# LargePrototype-V3.net
KiCad netlist of a schematic drawn in EAGLE
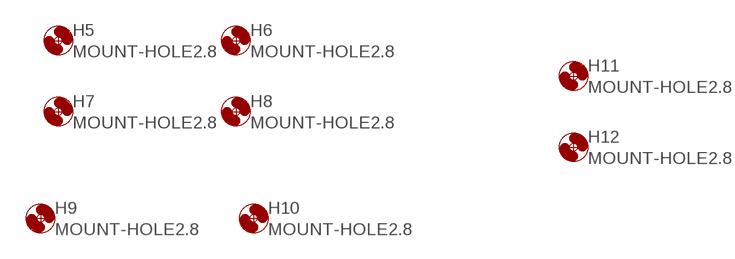
[diagram p0: schematic, sheet 1, part 1 of 3]
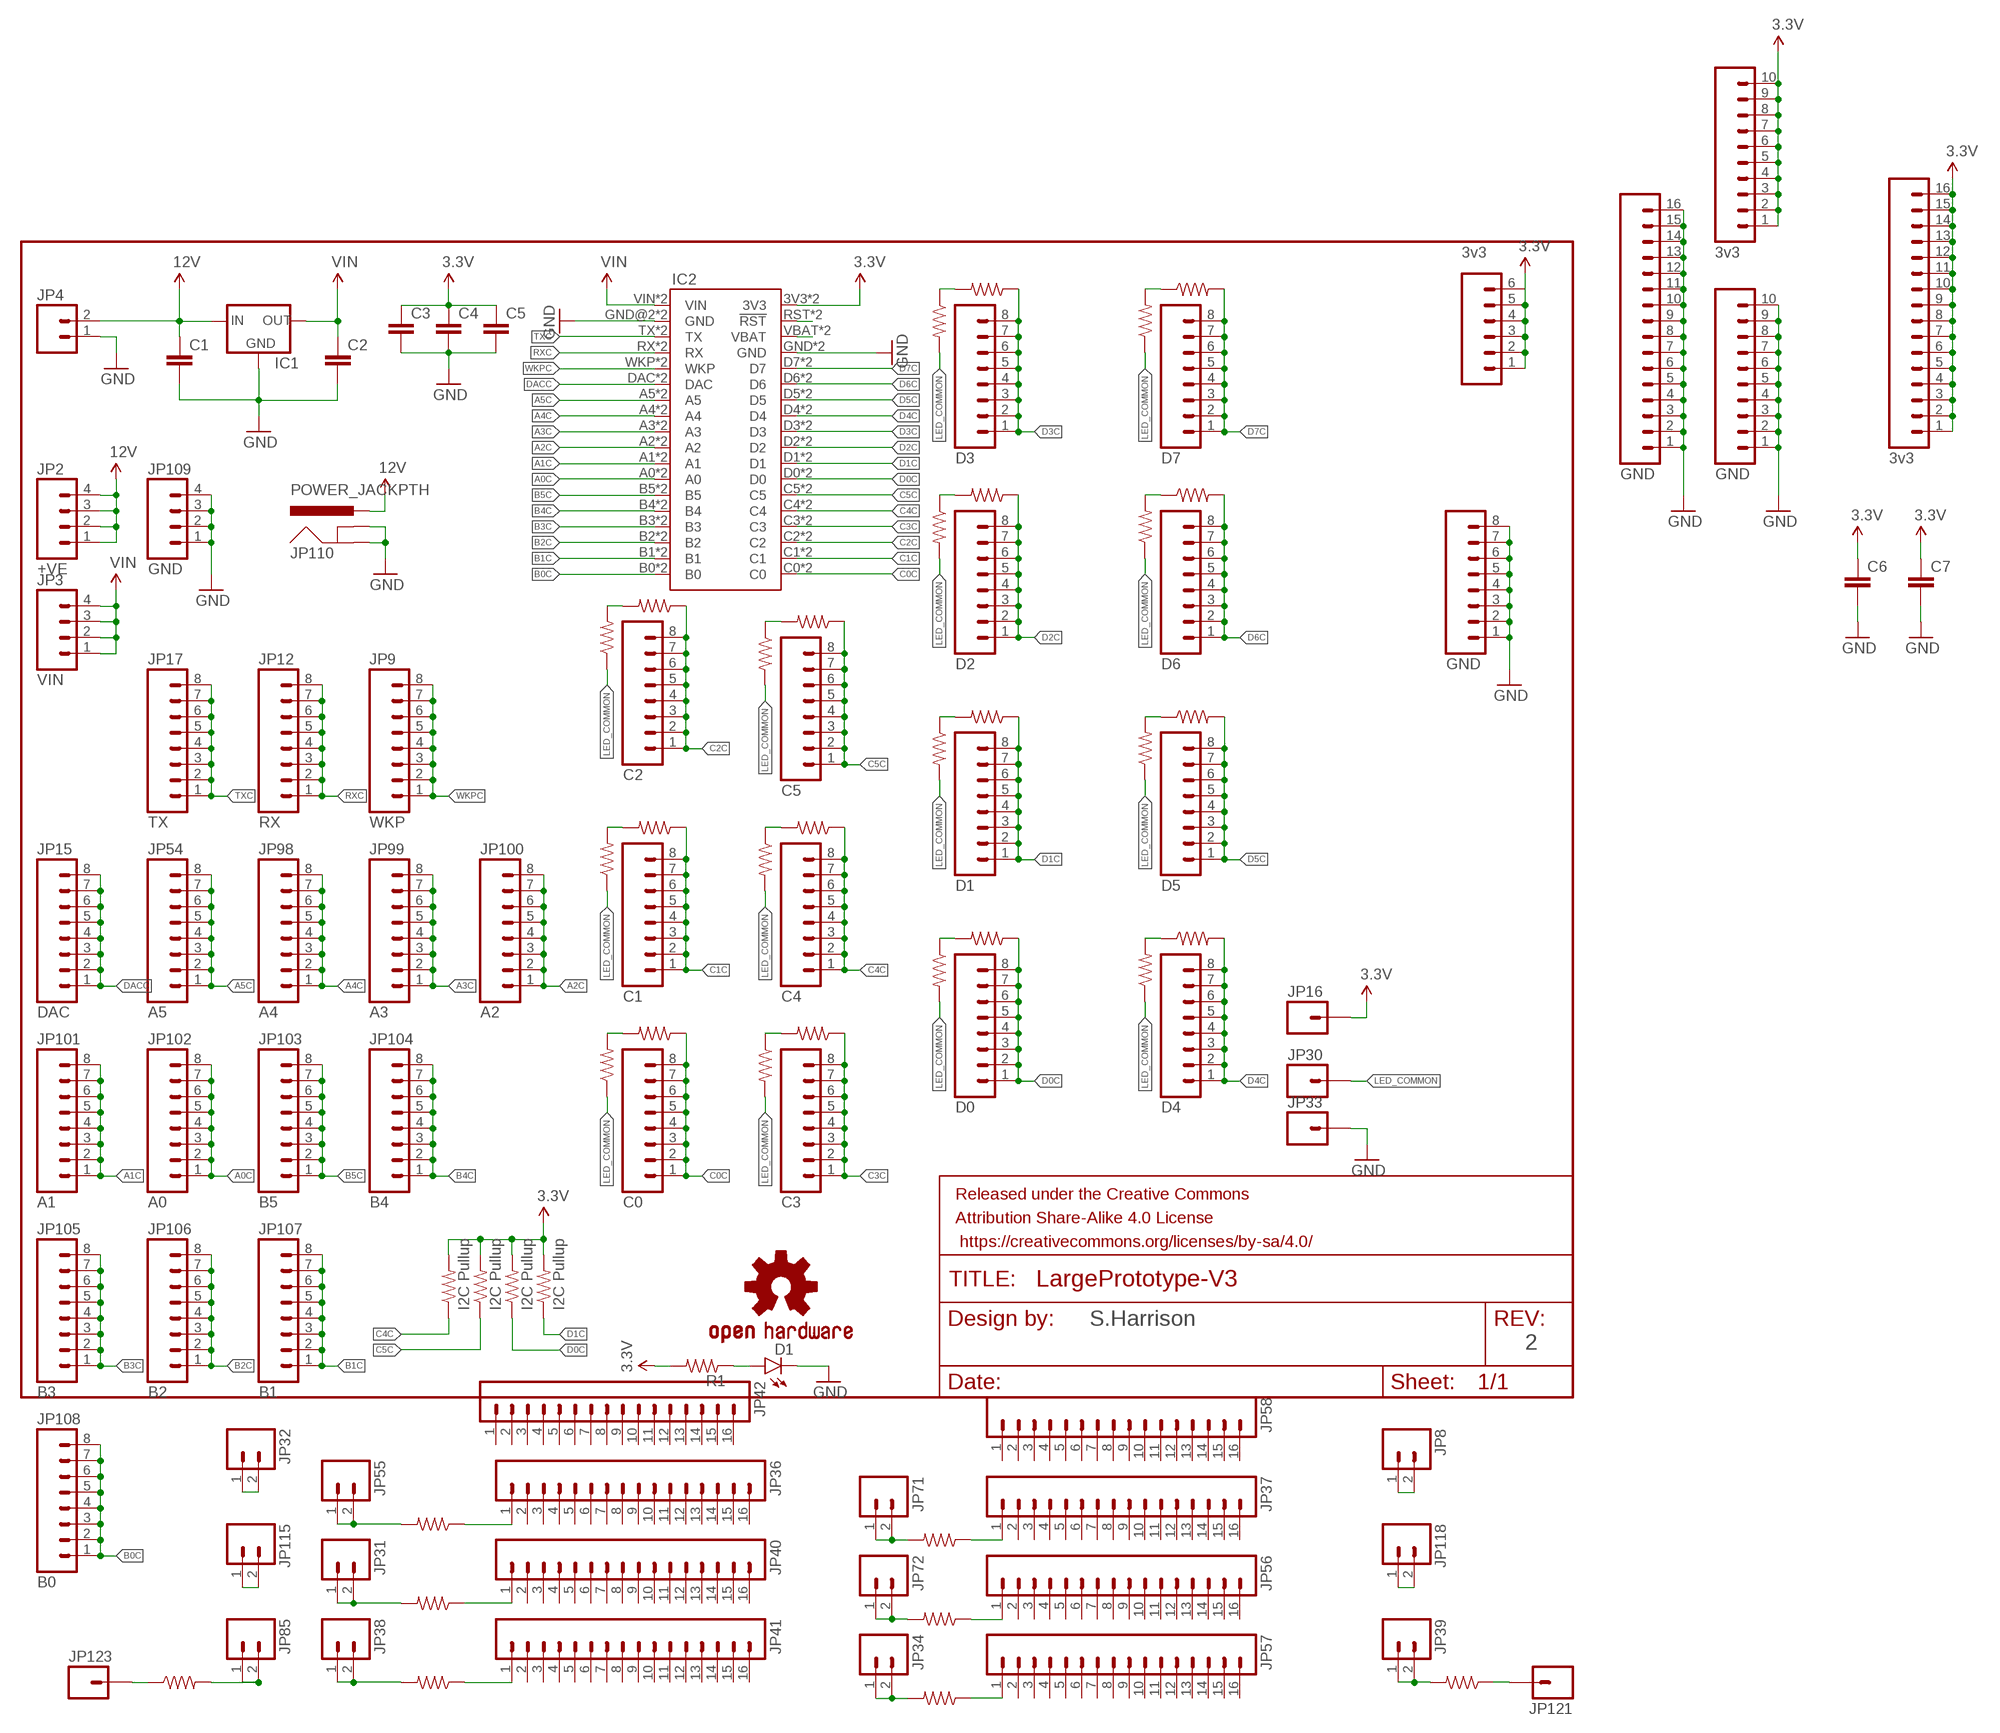
[diagram p1: schematic, sheet 1, part 2 of 3]
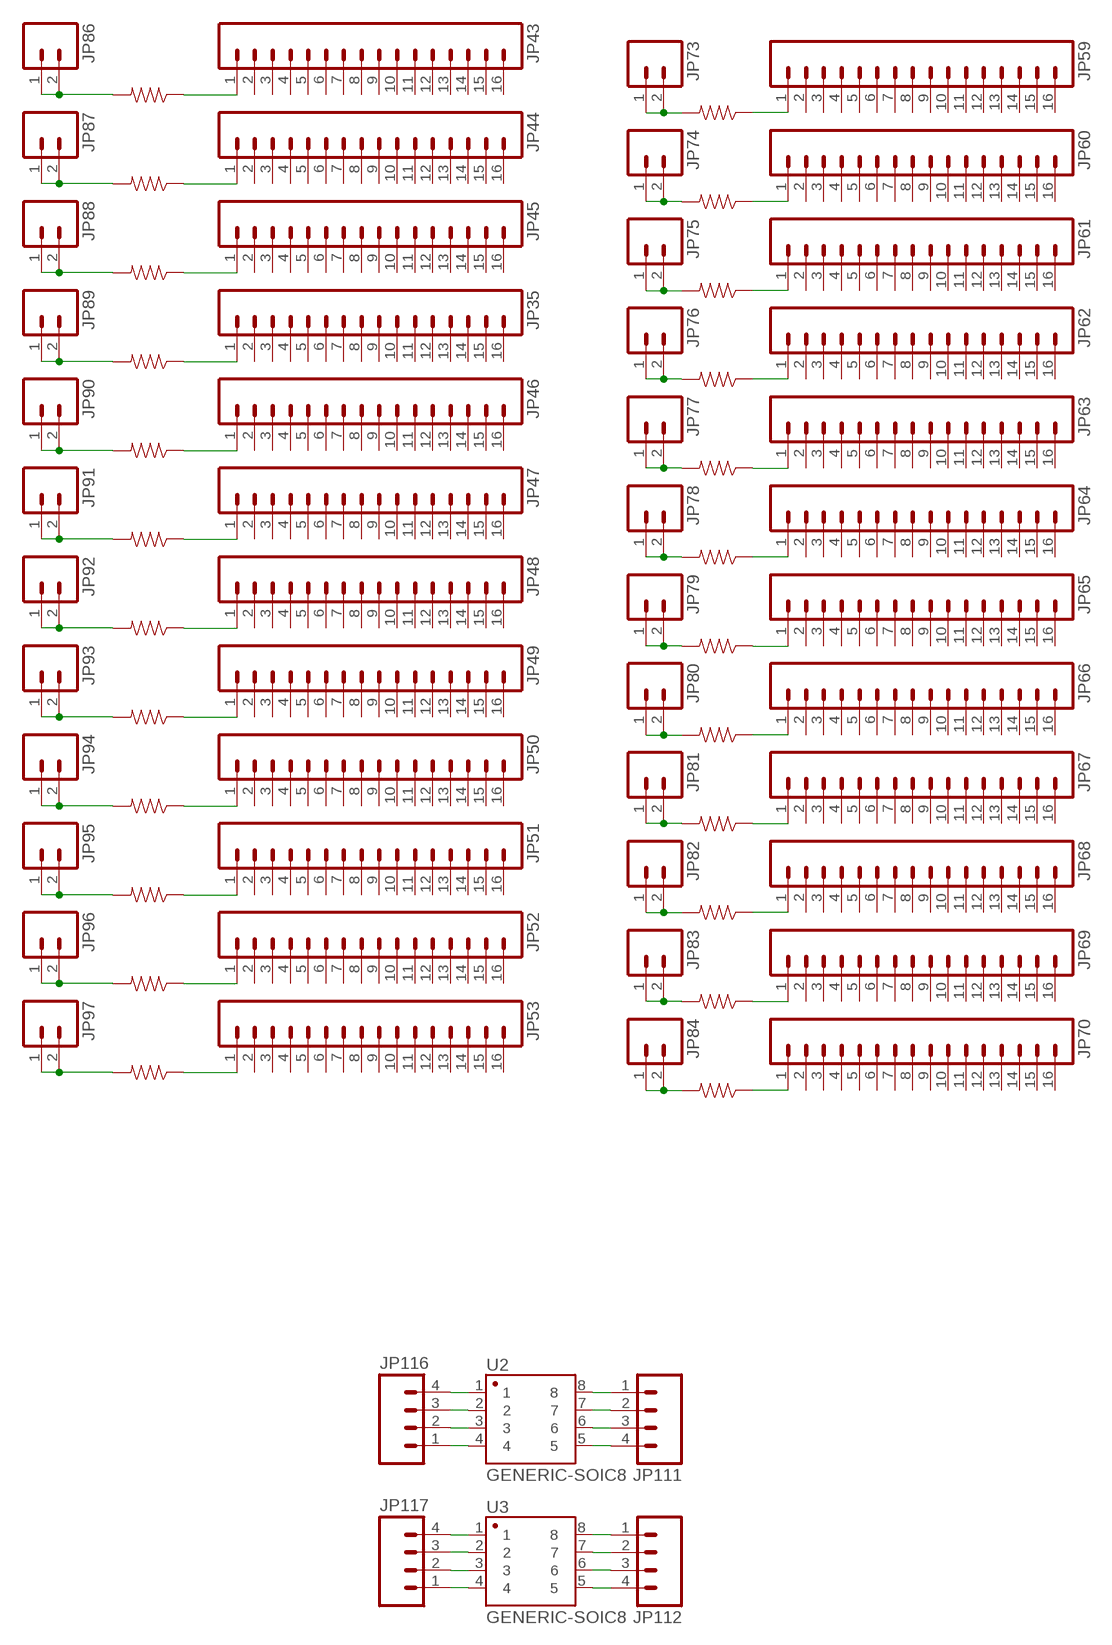
[diagram p2: schematic, sheet 1, part 3 of 3]

(export (version "E")
  (design (tool "Eeschema 10.0.6"))
  (components
    (comp (ref "C1")
      (value "1UF-25V-10%(0805)\"")
      (footprint "eagle-import:0805-CAP")
      (libsource (lib "eagle-import") (part "1UF-25V-10%(0805){dblquote}"))
    )
    (comp (ref "C2")
      (value "1UF-25V-10%(0805)\"")
      (footprint "eagle-import:0805-CAP")
      (libsource (lib "eagle-import") (part "1UF-25V-10%(0805){dblquote}"))
    )
    (comp (ref "C3")
      (value "1UF-25V-10%(0805)\"")
      (footprint "eagle-import:0805-CAP")
      (libsource (lib "eagle-import") (part "1UF-25V-10%(0805){dblquote}"))
    )
    (comp (ref "C4")
      (value "1UF-25V-10%(0805)\"")
      (footprint "eagle-import:0805-CAP")
      (libsource (lib "eagle-import") (part "1UF-25V-10%(0805){dblquote}"))
    )
    (comp (ref "C5")
      (value "1UF-25V-10%(0805)\"")
      (footprint "eagle-import:0805-CAP")
      (libsource (lib "eagle-import") (part "1UF-25V-10%(0805){dblquote}"))
    )
    (comp (ref "C6")
      (value "1UF-25V-10%(0805)\"")
      (footprint "eagle-import:0805-CAP")
      (libsource (lib "eagle-import") (part "1UF-25V-10%(0805){dblquote}"))
    )
    (comp (ref "C7")
      (value "1UF-25V-10%(0805)\"")
      (footprint "eagle-import:0805-CAP")
      (libsource (lib "eagle-import") (part "1UF-25V-10%(0805){dblquote}"))
    )
    (comp (ref "D1")
      (value "LED1206-BOTTOM")
      (footprint "eagle-import:LED-1206-BOTTOM")
      (libsource (lib "eagle-import") (part "LED1206-BOTTOM"))
    )
    (comp (ref "FRAME1")
      (value "FRAME-LETTER")
      (footprint "eagle-import:CREATIVE_COMMONS")
      (libsource (lib "eagle-import") (part "FRAME-LETTER"))
    )
    (comp (ref "H5")
      (value "MOUNT-HOLE2.8")
      (footprint "eagle-import:2,8")
      (libsource (lib "eagle-import") (part "MOUNT-HOLE2.8"))
    )
    (comp (ref "H6")
      (value "MOUNT-HOLE2.8")
      (footprint "eagle-import:2,8")
      (libsource (lib "eagle-import") (part "MOUNT-HOLE2.8"))
    )
    (comp (ref "H7")
      (value "MOUNT-HOLE2.8")
      (footprint "eagle-import:2,8")
      (libsource (lib "eagle-import") (part "MOUNT-HOLE2.8"))
    )
    (comp (ref "H8")
      (value "MOUNT-HOLE2.8")
      (footprint "eagle-import:2,8")
      (libsource (lib "eagle-import") (part "MOUNT-HOLE2.8"))
    )
    (comp (ref "H9")
      (value "MOUNT-HOLE2.8")
      (footprint "eagle-import:2,8")
      (libsource (lib "eagle-import") (part "MOUNT-HOLE2.8"))
    )
    (comp (ref "H10")
      (value "MOUNT-HOLE2.8")
      (footprint "eagle-import:2,8")
      (libsource (lib "eagle-import") (part "MOUNT-HOLE2.8"))
    )
    (comp (ref "H11")
      (value "MOUNT-HOLE2.8")
      (footprint "eagle-import:2,8")
      (libsource (lib "eagle-import") (part "MOUNT-HOLE2.8"))
    )
    (comp (ref "H12")
      (value "MOUNT-HOLE2.8")
      (footprint "eagle-import:2,8")
      (libsource (lib "eagle-import") (part "MOUNT-HOLE2.8"))
    )
    (comp (ref "IC1")
      (value "78XXS")
      (footprint "eagle-import:78XXS")
      (libsource (lib "eagle-import") (part "78XXS"))
    )
    (comp (ref "IC2")
      (value "ELECTRONDUALNAMED")
      (footprint "eagle-import:ELECTRON_SIMPLE_SILK_NAMES_DUAL")
      (libsource (lib "eagle-import") (part "ELECTRONDUALNAMED"))
    )
    (comp (ref "JP1")
      (value "D7")
      (footprint "eagle-import:1X08_ROUND")
      (libsource (lib "eagle-import") (part "M08"))
    )
    (comp (ref "JP2")
      (value "+VE")
      (footprint "eagle-import:1X04")
      (libsource (lib "eagle-import") (part "M04PTH"))
    )
    (comp (ref "JP3")
      (value "VIN")
      (footprint "eagle-import:1X04")
      (libsource (lib "eagle-import") (part "M04PTH"))
    )
    (comp (ref "JP4")
      (value "M025MM")
      (footprint "eagle-import:SCREWTERMINAL-5MM-2")
      (libsource (lib "eagle-import") (part "M025MM"))
    )
    (comp (ref "JP5")
      (value "3v3")
      (footprint "eagle-import:1X10")
      (libsource (lib "eagle-import") (part "M10SILK_FEMALE_PTH"))
    )
    (comp (ref "JP6")
      (value "3v3")
      (footprint "eagle-import:1X06")
      (libsource (lib "eagle-import") (part "M06SILK_FEMALE_PTH"))
    )
    (comp (ref "JP7")
      (value "D6")
      (footprint "eagle-import:1X08_ROUND")
      (libsource (lib "eagle-import") (part "M08"))
    )
    (comp (ref "JP8")
      (value "M02PTH")
      (footprint "eagle-import:1X02")
      (libsource (lib "eagle-import") (part "M02PTH"))
    )
    (comp (ref "JP9")
      (value "WKP")
      (footprint "eagle-import:1X08_ROUND")
      (libsource (lib "eagle-import") (part "M08"))
    )
    (comp (ref "JP10")
      (value "D5")
      (footprint "eagle-import:1X08_ROUND")
      (libsource (lib "eagle-import") (part "M08"))
    )
    (comp (ref "JP11")
      (value "GND")
      (footprint "eagle-import:1X10")
      (libsource (lib "eagle-import") (part "M10SILK_FEMALE_PTH"))
    )
    (comp (ref "JP12")
      (value "RX")
      (footprint "eagle-import:1X08_ROUND")
      (libsource (lib "eagle-import") (part "M08"))
    )
    (comp (ref "JP13")
      (value "3v3")
      (footprint "eagle-import:1X16")
      (libsource (lib "eagle-import") (part "M16PTH"))
    )
    (comp (ref "JP14")
      (value "GND")
      (footprint "eagle-import:1X16")
      (libsource (lib "eagle-import") (part "M16PTH"))
    )
    (comp (ref "JP15")
      (value "DAC")
      (footprint "eagle-import:1X08_ROUND")
      (libsource (lib "eagle-import") (part "M08"))
    )
    (comp (ref "JP16")
      (value "M01PTH")
      (footprint "eagle-import:1X01")
      (libsource (lib "eagle-import") (part "M01PTH"))
    )
    (comp (ref "JP17")
      (value "TX")
      (footprint "eagle-import:1X08_ROUND")
      (libsource (lib "eagle-import") (part "M08"))
    )
    (comp (ref "JP18")
      (value "D4")
      (footprint "eagle-import:1X08_ROUND")
      (libsource (lib "eagle-import") (part "M08"))
    )
    (comp (ref "JP19")
      (value "D3")
      (footprint "eagle-import:1X08_ROUND")
      (libsource (lib "eagle-import") (part "M08"))
    )
    (comp (ref "JP20")
      (value "D2")
      (footprint "eagle-import:1X08_ROUND")
      (libsource (lib "eagle-import") (part "M08"))
    )
    (comp (ref "JP21")
      (value "D1")
      (footprint "eagle-import:1X08_ROUND")
      (libsource (lib "eagle-import") (part "M08"))
    )
    (comp (ref "JP22")
      (value "D0")
      (footprint "eagle-import:1X08_ROUND")
      (libsource (lib "eagle-import") (part "M08"))
    )
    (comp (ref "JP23")
      (value "GND")
      (footprint "eagle-import:1X08_ROUND")
      (libsource (lib "eagle-import") (part "M08"))
    )
    (comp (ref "JP24")
      (value "C5")
      (footprint "eagle-import:1X08_ROUND")
      (libsource (lib "eagle-import") (part "M08"))
    )
    (comp (ref "JP25")
      (value "C4")
      (footprint "eagle-import:1X08_ROUND")
      (libsource (lib "eagle-import") (part "M08"))
    )
    (comp (ref "JP26")
      (value "C3")
      (footprint "eagle-import:1X08_ROUND")
      (libsource (lib "eagle-import") (part "M08"))
    )
    (comp (ref "JP27")
      (value "C2")
      (footprint "eagle-import:1X08_ROUND")
      (libsource (lib "eagle-import") (part "M08"))
    )
    (comp (ref "JP28")
      (value "C1")
      (footprint "eagle-import:1X08_ROUND")
      (libsource (lib "eagle-import") (part "M08"))
    )
    (comp (ref "JP29")
      (value "C0")
      (footprint "eagle-import:1X08_ROUND")
      (libsource (lib "eagle-import") (part "M08"))
    )
    (comp (ref "JP30")
      (value "M01PTH")
      (footprint "eagle-import:1X01")
      (libsource (lib "eagle-import") (part "M01PTH"))
    )
    (comp (ref "JP31")
      (value "M02PTH")
      (footprint "eagle-import:1X02")
      (libsource (lib "eagle-import") (part "M02PTH"))
    )
    (comp (ref "JP32")
      (value "M02PTH")
      (footprint "eagle-import:1X02")
      (libsource (lib "eagle-import") (part "M02PTH"))
    )
    (comp (ref "JP33")
      (value "M01PTH")
      (footprint "eagle-import:1X01")
      (libsource (lib "eagle-import") (part "M01PTH"))
    )
    (comp (ref "JP34")
      (value "M02PTH")
      (footprint "eagle-import:1X02")
      (libsource (lib "eagle-import") (part "M02PTH"))
    )
    (comp (ref "JP35")
      (value "M161X16_NO_SILK")
      (footprint "eagle-import:1X16_NO_SILK")
      (libsource (lib "eagle-import") (part "M161X16_NO_SILK"))
    )
    (comp (ref "JP36")
      (value "M161X16_NO_SILK")
      (footprint "eagle-import:1X16_NO_SILK")
      (libsource (lib "eagle-import") (part "M161X16_NO_SILK"))
    )
    (comp (ref "JP37")
      (value "M161X16_NO_SILK")
      (footprint "eagle-import:1X16_NO_SILK")
      (libsource (lib "eagle-import") (part "M161X16_NO_SILK"))
    )
    (comp (ref "JP38")
      (value "M02PTH")
      (footprint "eagle-import:1X02")
      (libsource (lib "eagle-import") (part "M02PTH"))
    )
    (comp (ref "JP39")
      (value "M02PTH")
      (footprint "eagle-import:1X02")
      (libsource (lib "eagle-import") (part "M02PTH"))
    )
    (comp (ref "JP40")
      (value "M161X16_NO_SILK")
      (footprint "eagle-import:1X16_NO_SILK")
      (libsource (lib "eagle-import") (part "M161X16_NO_SILK"))
    )
    (comp (ref "JP41")
      (value "M161X16_NO_SILK")
      (footprint "eagle-import:1X16_NO_SILK")
      (libsource (lib "eagle-import") (part "M161X16_NO_SILK"))
    )
    (comp (ref "JP42")
      (value "M161X16_NO_SILK")
      (footprint "eagle-import:1X16_NO_SILK")
      (libsource (lib "eagle-import") (part "M161X16_NO_SILK"))
    )
    (comp (ref "JP43")
      (value "M161X16_NO_SILK")
      (footprint "eagle-import:1X16_NO_SILK")
      (libsource (lib "eagle-import") (part "M161X16_NO_SILK"))
    )
    (comp (ref "JP44")
      (value "M161X16_NO_SILK")
      (footprint "eagle-import:1X16_NO_SILK")
      (libsource (lib "eagle-import") (part "M161X16_NO_SILK"))
    )
    (comp (ref "JP45")
      (value "M161X16_NO_SILK")
      (footprint "eagle-import:1X16_NO_SILK")
      (libsource (lib "eagle-import") (part "M161X16_NO_SILK"))
    )
    (comp (ref "JP46")
      (value "M161X16_NO_SILK")
      (footprint "eagle-import:1X16_NO_SILK")
      (libsource (lib "eagle-import") (part "M161X16_NO_SILK"))
    )
    (comp (ref "JP47")
      (value "M161X16_NO_SILK")
      (footprint "eagle-import:1X16_NO_SILK")
      (libsource (lib "eagle-import") (part "M161X16_NO_SILK"))
    )
    (comp (ref "JP48")
      (value "M161X16_NO_SILK")
      (footprint "eagle-import:1X16_NO_SILK")
      (libsource (lib "eagle-import") (part "M161X16_NO_SILK"))
    )
    (comp (ref "JP49")
      (value "M161X16_NO_SILK")
      (footprint "eagle-import:1X16_NO_SILK")
      (libsource (lib "eagle-import") (part "M161X16_NO_SILK"))
    )
    (comp (ref "JP50")
      (value "M161X16_NO_SILK")
      (footprint "eagle-import:1X16_NO_SILK")
      (libsource (lib "eagle-import") (part "M161X16_NO_SILK"))
    )
    (comp (ref "JP51")
      (value "M161X16_NO_SILK")
      (footprint "eagle-import:1X16_NO_SILK")
      (libsource (lib "eagle-import") (part "M161X16_NO_SILK"))
    )
    (comp (ref "JP52")
      (value "M161X16_NO_SILK")
      (footprint "eagle-import:1X16_NO_SILK")
      (libsource (lib "eagle-import") (part "M161X16_NO_SILK"))
    )
    (comp (ref "JP53")
      (value "M161X16_NO_SILK")
      (footprint "eagle-import:1X16_NO_SILK")
      (libsource (lib "eagle-import") (part "M161X16_NO_SILK"))
    )
    (comp (ref "JP54")
      (value "A5")
      (footprint "eagle-import:1X08_ROUND")
      (libsource (lib "eagle-import") (part "M08"))
    )
    (comp (ref "JP55")
      (value "M02PTH")
      (footprint "eagle-import:1X02")
      (libsource (lib "eagle-import") (part "M02PTH"))
    )
    (comp (ref "JP56")
      (value "M161X16_NO_SILK")
      (footprint "eagle-import:1X16_NO_SILK")
      (libsource (lib "eagle-import") (part "M161X16_NO_SILK"))
    )
    (comp (ref "JP57")
      (value "M161X16_NO_SILK")
      (footprint "eagle-import:1X16_NO_SILK")
      (libsource (lib "eagle-import") (part "M161X16_NO_SILK"))
    )
    (comp (ref "JP58")
      (value "M161X16_NO_SILK")
      (footprint "eagle-import:1X16_NO_SILK")
      (libsource (lib "eagle-import") (part "M161X16_NO_SILK"))
    )
    (comp (ref "JP59")
      (value "M161X16_NO_SILK")
      (footprint "eagle-import:1X16_NO_SILK")
      (libsource (lib "eagle-import") (part "M161X16_NO_SILK"))
    )
    (comp (ref "JP60")
      (value "M161X16_NO_SILK")
      (footprint "eagle-import:1X16_NO_SILK")
      (libsource (lib "eagle-import") (part "M161X16_NO_SILK"))
    )
    (comp (ref "JP61")
      (value "M161X16_NO_SILK")
      (footprint "eagle-import:1X16_NO_SILK")
      (libsource (lib "eagle-import") (part "M161X16_NO_SILK"))
    )
    (comp (ref "JP62")
      (value "M161X16_NO_SILK")
      (footprint "eagle-import:1X16_NO_SILK")
      (libsource (lib "eagle-import") (part "M161X16_NO_SILK"))
    )
    (comp (ref "JP63")
      (value "M161X16_NO_SILK")
      (footprint "eagle-import:1X16_NO_SILK")
      (libsource (lib "eagle-import") (part "M161X16_NO_SILK"))
    )
    (comp (ref "JP64")
      (value "M161X16_NO_SILK")
      (footprint "eagle-import:1X16_NO_SILK")
      (libsource (lib "eagle-import") (part "M161X16_NO_SILK"))
    )
    (comp (ref "JP65")
      (value "M161X16_NO_SILK")
      (footprint "eagle-import:1X16_NO_SILK")
      (libsource (lib "eagle-import") (part "M161X16_NO_SILK"))
    )
    (comp (ref "JP66")
      (value "M161X16_NO_SILK")
      (footprint "eagle-import:1X16_NO_SILK")
      (libsource (lib "eagle-import") (part "M161X16_NO_SILK"))
    )
    (comp (ref "JP67")
      (value "M161X16_NO_SILK")
      (footprint "eagle-import:1X16_NO_SILK")
      (libsource (lib "eagle-import") (part "M161X16_NO_SILK"))
    )
    (comp (ref "JP68")
      (value "M161X16_NO_SILK")
      (footprint "eagle-import:1X16_NO_SILK")
      (libsource (lib "eagle-import") (part "M161X16_NO_SILK"))
    )
    (comp (ref "JP69")
      (value "M161X16_NO_SILK")
      (footprint "eagle-import:1X16_NO_SILK")
      (libsource (lib "eagle-import") (part "M161X16_NO_SILK"))
    )
    (comp (ref "JP70")
      (value "M161X16_NO_SILK")
      (footprint "eagle-import:1X16_NO_SILK")
      (libsource (lib "eagle-import") (part "M161X16_NO_SILK"))
    )
    (comp (ref "JP71")
      (value "M02PTH")
      (footprint "eagle-import:1X02")
      (libsource (lib "eagle-import") (part "M02PTH"))
    )
    (comp (ref "JP72")
      (value "M02PTH")
      (footprint "eagle-import:1X02")
      (libsource (lib "eagle-import") (part "M02PTH"))
    )
    (comp (ref "JP73")
      (value "M02PTH")
      (footprint "eagle-import:1X02")
      (libsource (lib "eagle-import") (part "M02PTH"))
    )
    (comp (ref "JP74")
      (value "M02PTH")
      (footprint "eagle-import:1X02")
      (libsource (lib "eagle-import") (part "M02PTH"))
    )
    (comp (ref "JP75")
      (value "M02PTH")
      (footprint "eagle-import:1X02")
      (libsource (lib "eagle-import") (part "M02PTH"))
    )
    (comp (ref "JP76")
      (value "M02PTH")
      (footprint "eagle-import:1X02")
      (libsource (lib "eagle-import") (part "M02PTH"))
    )
    (comp (ref "JP77")
      (value "M02PTH")
      (footprint "eagle-import:1X02")
      (libsource (lib "eagle-import") (part "M02PTH"))
    )
    (comp (ref "JP78")
      (value "M02PTH")
      (footprint "eagle-import:1X02")
      (libsource (lib "eagle-import") (part "M02PTH"))
    )
    (comp (ref "JP79")
      (value "M02PTH")
      (footprint "eagle-import:1X02")
      (libsource (lib "eagle-import") (part "M02PTH"))
    )
    (comp (ref "JP80")
      (value "M02PTH")
      (footprint "eagle-import:1X02")
      (libsource (lib "eagle-import") (part "M02PTH"))
    )
    (comp (ref "JP81")
      (value "M02PTH")
      (footprint "eagle-import:1X02")
      (libsource (lib "eagle-import") (part "M02PTH"))
    )
    (comp (ref "JP82")
      (value "M02PTH")
      (footprint "eagle-import:1X02")
      (libsource (lib "eagle-import") (part "M02PTH"))
    )
    (comp (ref "JP83")
      (value "M02PTH")
      (footprint "eagle-import:1X02")
      (libsource (lib "eagle-import") (part "M02PTH"))
    )
    (comp (ref "JP84")
      (value "M02PTH")
      (footprint "eagle-import:1X02")
      (libsource (lib "eagle-import") (part "M02PTH"))
    )
    (comp (ref "JP85")
      (value "M02PTH")
      (footprint "eagle-import:1X02")
      (libsource (lib "eagle-import") (part "M02PTH"))
    )
    (comp (ref "JP86")
      (value "M02PTH")
      (footprint "eagle-import:1X02")
      (libsource (lib "eagle-import") (part "M02PTH"))
    )
    (comp (ref "JP87")
      (value "M02PTH")
      (footprint "eagle-import:1X02")
      (libsource (lib "eagle-import") (part "M02PTH"))
    )
    (comp (ref "JP88")
      (value "M02PTH")
      (footprint "eagle-import:1X02")
      (libsource (lib "eagle-import") (part "M02PTH"))
    )
    (comp (ref "JP89")
      (value "M02PTH")
      (footprint "eagle-import:1X02")
      (libsource (lib "eagle-import") (part "M02PTH"))
    )
    (comp (ref "JP90")
      (value "M02PTH")
      (footprint "eagle-import:1X02")
      (libsource (lib "eagle-import") (part "M02PTH"))
    )
    (comp (ref "JP91")
      (value "M02PTH")
      (footprint "eagle-import:1X02")
      (libsource (lib "eagle-import") (part "M02PTH"))
    )
    (comp (ref "JP92")
      (value "M02PTH")
      (footprint "eagle-import:1X02")
      (libsource (lib "eagle-import") (part "M02PTH"))
    )
    (comp (ref "JP93")
      (value "M02PTH")
      (footprint "eagle-import:1X02")
      (libsource (lib "eagle-import") (part "M02PTH"))
    )
    (comp (ref "JP94")
      (value "M02PTH")
      (footprint "eagle-import:1X02")
      (libsource (lib "eagle-import") (part "M02PTH"))
    )
    (comp (ref "JP95")
      (value "M02PTH")
      (footprint "eagle-import:1X02")
      (libsource (lib "eagle-import") (part "M02PTH"))
    )
    (comp (ref "JP96")
      (value "M02PTH")
      (footprint "eagle-import:1X02")
      (libsource (lib "eagle-import") (part "M02PTH"))
    )
    (comp (ref "JP97")
      (value "M02PTH")
      (footprint "eagle-import:1X02")
      (libsource (lib "eagle-import") (part "M02PTH"))
    )
    (comp (ref "JP98")
      (value "A4")
      (footprint "eagle-import:1X08_ROUND")
      (libsource (lib "eagle-import") (part "M08"))
    )
    (comp (ref "JP99")
      (value "A3")
      (footprint "eagle-import:1X08_ROUND")
      (libsource (lib "eagle-import") (part "M08"))
    )
    (comp (ref "JP100")
      (value "A2")
      (footprint "eagle-import:1X08_ROUND")
      (libsource (lib "eagle-import") (part "M08"))
    )
    (comp (ref "JP101")
      (value "A1")
      (footprint "eagle-import:1X08_ROUND")
      (libsource (lib "eagle-import") (part "M08"))
    )
    (comp (ref "JP102")
      (value "A0")
      (footprint "eagle-import:1X08_ROUND")
      (libsource (lib "eagle-import") (part "M08"))
    )
    (comp (ref "JP103")
      (value "B5")
      (footprint "eagle-import:1X08_ROUND")
      (libsource (lib "eagle-import") (part "M08"))
    )
    (comp (ref "JP104")
      (value "B4")
      (footprint "eagle-import:1X08_ROUND")
      (libsource (lib "eagle-import") (part "M08"))
    )
    (comp (ref "JP105")
      (value "B3")
      (footprint "eagle-import:1X08_ROUND")
      (libsource (lib "eagle-import") (part "M08"))
    )
    (comp (ref "JP106")
      (value "B2")
      (footprint "eagle-import:1X08_ROUND")
      (libsource (lib "eagle-import") (part "M08"))
    )
    (comp (ref "JP107")
      (value "B1")
      (footprint "eagle-import:1X08_ROUND")
      (libsource (lib "eagle-import") (part "M08"))
    )
    (comp (ref "JP108")
      (value "B0")
      (footprint "eagle-import:1X08_ROUND")
      (libsource (lib "eagle-import") (part "M08"))
    )
    (comp (ref "JP109")
      (value "GND")
      (footprint "eagle-import:1X04")
      (libsource (lib "eagle-import") (part "M04PTH"))
    )
    (comp (ref "JP110")
      (value "POWER_JACKPTH")
      (footprint "eagle-import:POWER_JACK_PTH")
      (libsource (lib "eagle-import") (part "POWER_JACKPTH"))
    )
    (comp (ref "JP111")
      (value "M04NO_SILK_ALL_ROUND")
      (footprint "eagle-import:1X04_NO_SILK_ALL_ROUND")
      (libsource (lib "eagle-import") (part "M04NO_SILK_ALL_ROUND"))
    )
    (comp (ref "JP112")
      (value "M04NO_SILK_ALL_ROUND")
      (footprint "eagle-import:1X04_NO_SILK_ALL_ROUND")
      (libsource (lib "eagle-import") (part "M04NO_SILK_ALL_ROUND"))
    )
    (comp (ref "JP115")
      (value "M02PTH")
      (footprint "eagle-import:1X02")
      (libsource (lib "eagle-import") (part "M02PTH"))
    )
    (comp (ref "JP116")
      (value "M04NO_SILK_ALL_ROUND")
      (footprint "eagle-import:1X04_NO_SILK_ALL_ROUND")
      (libsource (lib "eagle-import") (part "M04NO_SILK_ALL_ROUND"))
    )
    (comp (ref "JP117")
      (value "M04NO_SILK_ALL_ROUND")
      (footprint "eagle-import:1X04_NO_SILK_ALL_ROUND")
      (libsource (lib "eagle-import") (part "M04NO_SILK_ALL_ROUND"))
    )
    (comp (ref "JP118")
      (value "M02PTH")
      (footprint "eagle-import:1X02")
      (libsource (lib "eagle-import") (part "M02PTH"))
    )
    (comp (ref "JP121")
      (value "M01NOSILK-KIT")
      (footprint "eagle-import:1X01NS-KIT")
      (libsource (lib "eagle-import") (part "M01NOSILK-KIT"))
    )
    (comp (ref "JP123")
      (value "M01NOSILK-KIT")
      (footprint "eagle-import:1X01NS-KIT")
      (libsource (lib "eagle-import") (part "M01NOSILK-KIT"))
    )
    (comp (ref "LOGO3")
      (value "OSHW-LOGOM")
      (footprint "eagle-import:OSHW-LOGO-M")
      (libsource (lib "eagle-import") (part "OSHW-LOGOM"))
    )
    (comp (ref "R1")
      (value "RESISTOR1206")
      (footprint "eagle-import:1206")
      (libsource (lib "eagle-import") (part "RESISTOR1206"))
    )
    (comp (ref "R2")
      (value "RESISTOR1206")
      (footprint "eagle-import:1206")
      (libsource (lib "eagle-import") (part "RESISTOR1206"))
    )
    (comp (ref "R3")
      (value "RESISTOR1206")
      (footprint "eagle-import:1206")
      (libsource (lib "eagle-import") (part "RESISTOR1206"))
    )
    (comp (ref "R4")
      (value "RESISTOR1206")
      (footprint "eagle-import:1206")
      (libsource (lib "eagle-import") (part "RESISTOR1206"))
    )
    (comp (ref "R5")
      (value "RESISTOR1206")
      (footprint "eagle-import:1206")
      (libsource (lib "eagle-import") (part "RESISTOR1206"))
    )
    (comp (ref "R6")
      (value "RESISTOR1206")
      (footprint "eagle-import:1206")
      (libsource (lib "eagle-import") (part "RESISTOR1206"))
    )
    (comp (ref "R7")
      (value "RESISTOR1206")
      (footprint "eagle-import:1206")
      (libsource (lib "eagle-import") (part "RESISTOR1206"))
    )
    (comp (ref "R8")
      (value "RESISTOR1206")
      (footprint "eagle-import:1206")
      (libsource (lib "eagle-import") (part "RESISTOR1206"))
    )
    (comp (ref "R9")
      (value "RESISTOR1206")
      (footprint "eagle-import:1206")
      (libsource (lib "eagle-import") (part "RESISTOR1206"))
    )
    (comp (ref "R10")
      (value "RESISTOR1206")
      (footprint "eagle-import:1206")
      (libsource (lib "eagle-import") (part "RESISTOR1206"))
    )
    (comp (ref "R11")
      (value "RESISTOR1206")
      (footprint "eagle-import:1206")
      (libsource (lib "eagle-import") (part "RESISTOR1206"))
    )
    (comp (ref "R12")
      (value "RESISTOR1206")
      (footprint "eagle-import:1206")
      (libsource (lib "eagle-import") (part "RESISTOR1206"))
    )
    (comp (ref "R13")
      (value "RESISTOR1206")
      (footprint "eagle-import:1206")
      (libsource (lib "eagle-import") (part "RESISTOR1206"))
    )
    (comp (ref "R14")
      (value "RESISTOR1206")
      (footprint "eagle-import:1206")
      (libsource (lib "eagle-import") (part "RESISTOR1206"))
    )
    (comp (ref "R15")
      (value "RESISTOR1206")
      (footprint "eagle-import:1206")
      (libsource (lib "eagle-import") (part "RESISTOR1206"))
    )
    (comp (ref "R16")
      (value "RESISTOR1206")
      (footprint "eagle-import:1206")
      (libsource (lib "eagle-import") (part "RESISTOR1206"))
    )
    (comp (ref "R17")
      (value "RESISTOR1206")
      (footprint "eagle-import:1206")
      (libsource (lib "eagle-import") (part "RESISTOR1206"))
    )
    (comp (ref "R18")
      (value "RESISTOR1206")
      (footprint "eagle-import:1206")
      (libsource (lib "eagle-import") (part "RESISTOR1206"))
    )
    (comp (ref "R19")
      (value "RESISTOR1206")
      (footprint "eagle-import:1206")
      (libsource (lib "eagle-import") (part "RESISTOR1206"))
    )
    (comp (ref "R20")
      (value "RESISTOR1206")
      (footprint "eagle-import:1206")
      (libsource (lib "eagle-import") (part "RESISTOR1206"))
    )
    (comp (ref "R21")
      (value "RESISTOR1206")
      (footprint "eagle-import:1206")
      (libsource (lib "eagle-import") (part "RESISTOR1206"))
    )
    (comp (ref "R22")
      (value "RESISTOR1206")
      (footprint "eagle-import:1206")
      (libsource (lib "eagle-import") (part "RESISTOR1206"))
    )
    (comp (ref "R23")
      (value "RESISTOR1206")
      (footprint "eagle-import:1206")
      (libsource (lib "eagle-import") (part "RESISTOR1206"))
    )
    (comp (ref "R24")
      (value "RESISTOR1206")
      (footprint "eagle-import:1206")
      (libsource (lib "eagle-import") (part "RESISTOR1206"))
    )
    (comp (ref "R25")
      (value "RESISTOR1206")
      (footprint "eagle-import:1206")
      (libsource (lib "eagle-import") (part "RESISTOR1206"))
    )
    (comp (ref "R26")
      (value "RESISTOR1206")
      (footprint "eagle-import:1206")
      (libsource (lib "eagle-import") (part "RESISTOR1206"))
    )
    (comp (ref "R27")
      (value "RESISTOR1206")
      (footprint "eagle-import:1206")
      (libsource (lib "eagle-import") (part "RESISTOR1206"))
    )
    (comp (ref "R28")
      (value "RESISTOR1206")
      (footprint "eagle-import:1206")
      (libsource (lib "eagle-import") (part "RESISTOR1206"))
    )
    (comp (ref "R29")
      (value "RESISTOR1206")
      (footprint "eagle-import:1206")
      (libsource (lib "eagle-import") (part "RESISTOR1206"))
    )
    (comp (ref "R30")
      (value "RESISTOR1206")
      (footprint "eagle-import:1206")
      (libsource (lib "eagle-import") (part "RESISTOR1206"))
    )
    (comp (ref "R31")
      (value "RESISTOR1206")
      (footprint "eagle-import:1206")
      (libsource (lib "eagle-import") (part "RESISTOR1206"))
    )
    (comp (ref "R32")
      (value "RESISTOR1206")
      (footprint "eagle-import:1206")
      (libsource (lib "eagle-import") (part "RESISTOR1206"))
    )
    (comp (ref "R33")
      (value "RESISTOR1206")
      (footprint "eagle-import:1206")
      (libsource (lib "eagle-import") (part "RESISTOR1206"))
    )
    (comp (ref "R34")
      (value "RESISTOR1206")
      (footprint "eagle-import:1206")
      (libsource (lib "eagle-import") (part "RESISTOR1206"))
    )
    (comp (ref "R35")
      (value "RESISTOR1206")
      (footprint "eagle-import:1206")
      (libsource (lib "eagle-import") (part "RESISTOR1206"))
    )
    (comp (ref "R36")
      (value "RESISTOR1206")
      (footprint "eagle-import:1206")
      (libsource (lib "eagle-import") (part "RESISTOR1206"))
    )
    (comp (ref "R37")
      (value "RESISTOR1206")
      (footprint "eagle-import:1206")
      (libsource (lib "eagle-import") (part "RESISTOR1206"))
    )
    (comp (ref "R38")
      (value "RESISTOR1206")
      (footprint "eagle-import:1206")
      (libsource (lib "eagle-import") (part "RESISTOR1206"))
    )
    (comp (ref "R39")
      (value "RESISTOR1206")
      (footprint "eagle-import:1206")
      (libsource (lib "eagle-import") (part "RESISTOR1206"))
    )
    (comp (ref "R40")
      (value "RESISTOR1206")
      (footprint "eagle-import:1206")
      (libsource (lib "eagle-import") (part "RESISTOR1206"))
    )
    (comp (ref "R41")
      (value "RESISTOR1206")
      (footprint "eagle-import:1206")
      (libsource (lib "eagle-import") (part "RESISTOR1206"))
    )
    (comp (ref "R42")
      (value "RESISTOR1206")
      (footprint "eagle-import:1206")
      (libsource (lib "eagle-import") (part "RESISTOR1206"))
    )
    (comp (ref "R43")
      (value "RESISTOR1206")
      (footprint "eagle-import:1206")
      (libsource (lib "eagle-import") (part "RESISTOR1206"))
    )
    (comp (ref "R44")
      (value "RESISTOR1206")
      (footprint "eagle-import:1206")
      (libsource (lib "eagle-import") (part "RESISTOR1206"))
    )
    (comp (ref "R45")
      (value "RESISTOR1206")
      (footprint "eagle-import:1206")
      (libsource (lib "eagle-import") (part "RESISTOR1206"))
    )
    (comp (ref "R46")
      (value "RESISTOR1206")
      (footprint "eagle-import:1206")
      (libsource (lib "eagle-import") (part "RESISTOR1206"))
    )
    (comp (ref "R47")
      (value "RESISTOR1206")
      (footprint "eagle-import:1206")
      (libsource (lib "eagle-import") (part "RESISTOR1206"))
    )
    (comp (ref "R48")
      (value "RESISTOR1206")
      (footprint "eagle-import:1206")
      (libsource (lib "eagle-import") (part "RESISTOR1206"))
    )
    (comp (ref "R49")
      (value "RESISTOR1206")
      (footprint "eagle-import:1206")
      (libsource (lib "eagle-import") (part "RESISTOR1206"))
    )
    (comp (ref "R50")
      (value "RESISTOR1206")
      (footprint "eagle-import:1206")
      (libsource (lib "eagle-import") (part "RESISTOR1206"))
    )
    (comp (ref "R51")
      (value "RESISTOR1206")
      (footprint "eagle-import:1206")
      (libsource (lib "eagle-import") (part "RESISTOR1206"))
    )
    (comp (ref "R52")
      (value "RESISTOR1206")
      (footprint "eagle-import:1206")
      (libsource (lib "eagle-import") (part "RESISTOR1206"))
    )
    (comp (ref "R53")
      (value "RESISTOR1206")
      (footprint "eagle-import:1206")
      (libsource (lib "eagle-import") (part "RESISTOR1206"))
    )
    (comp (ref "R54")
      (value "RESISTOR1206")
      (footprint "eagle-import:1206")
      (libsource (lib "eagle-import") (part "RESISTOR1206"))
    )
    (comp (ref "R55")
      (value "RESISTOR1206")
      (footprint "eagle-import:1206")
      (libsource (lib "eagle-import") (part "RESISTOR1206"))
    )
    (comp (ref "R56")
      (value "RESISTOR1206")
      (footprint "eagle-import:1206")
      (libsource (lib "eagle-import") (part "RESISTOR1206"))
    )
    (comp (ref "R57")
      (value "RESISTOR1206")
      (footprint "eagle-import:1206")
      (libsource (lib "eagle-import") (part "RESISTOR1206"))
    )
    (comp (ref "R58")
      (value "RESISTOR1206")
      (footprint "eagle-import:1206")
      (libsource (lib "eagle-import") (part "RESISTOR1206"))
    )
    (comp (ref "R59")
      (value "RESISTOR1206")
      (footprint "eagle-import:1206")
      (libsource (lib "eagle-import") (part "RESISTOR1206"))
    )
    (comp (ref "R60")
      (value "RESISTOR1206")
      (footprint "eagle-import:1206")
      (libsource (lib "eagle-import") (part "RESISTOR1206"))
    )
    (comp (ref "R61")
      (value "RESISTOR1206")
      (footprint "eagle-import:1206")
      (libsource (lib "eagle-import") (part "RESISTOR1206"))
    )
    (comp (ref "R62")
      (value "I2C Pullup")
      (footprint "eagle-import:1206")
      (libsource (lib "eagle-import") (part "RESISTOR1206"))
    )
    (comp (ref "R63")
      (value "I2C Pullup")
      (footprint "eagle-import:1206")
      (libsource (lib "eagle-import") (part "RESISTOR1206"))
    )
    (comp (ref "R64")
      (value "I2C Pullup")
      (footprint "eagle-import:1206")
      (libsource (lib "eagle-import") (part "RESISTOR1206"))
    )
    (comp (ref "R65")
      (value "I2C Pullup")
      (footprint "eagle-import:1206")
      (libsource (lib "eagle-import") (part "RESISTOR1206"))
    )
    (comp (ref "U2")
      (value "GENERIC-SOIC8")
      (footprint "eagle-import:SO08-UNIVERSAL")
      (libsource (lib "eagle-import") (part "GENERIC-SOIC8"))
    )
    (comp (ref "U3")
      (value "GENERIC-SOIC8")
      (footprint "eagle-import:SO08-UNIVERSAL")
      (libsource (lib "eagle-import") (part "GENERIC-SOIC8"))
    )
  )
  (nets
    (net (code "1") (name "3.3V") (class "Default")
      (node (ref "C3") (pin "1") (pinfunction "1_1") (pintype "passive"))
      (node (ref "C4") (pin "1") (pinfunction "1_1") (pintype "passive"))
      (node (ref "C5") (pin "1") (pinfunction "1_1") (pintype "passive"))
      (node (ref "C6") (pin "1") (pinfunction "1_1") (pintype "passive"))
      (node (ref "C7") (pin "1") (pinfunction "1_1") (pintype "passive"))
      (node (ref "IC2") (pin "3V3") (pinfunction "3V3_3V3") (pintype "power_in"))
      (node (ref "IC2") (pin "3V3_1") (pinfunction "3V3_3V3_1") (pintype "power_in"))
      (node (ref "JP13") (pin "1") (pinfunction "1_1") (pintype "passive"))
      (node (ref "JP13") (pin "10") (pinfunction "10_10") (pintype "passive"))
      (node (ref "JP13") (pin "11") (pinfunction "11_11") (pintype "passive"))
      (node (ref "JP13") (pin "12") (pinfunction "12_12") (pintype "passive"))
      (node (ref "JP13") (pin "13") (pinfunction "13_13") (pintype "passive"))
      (node (ref "JP13") (pin "14") (pinfunction "14_14") (pintype "passive"))
      (node (ref "JP13") (pin "15") (pinfunction "15_15") (pintype "passive"))
      (node (ref "JP13") (pin "16") (pinfunction "16_16") (pintype "passive"))
      (node (ref "JP13") (pin "2") (pinfunction "2_2") (pintype "passive"))
      (node (ref "JP13") (pin "3") (pinfunction "3_3") (pintype "passive"))
      (node (ref "JP13") (pin "4") (pinfunction "4_4") (pintype "passive"))
      (node (ref "JP13") (pin "5") (pinfunction "5_5") (pintype "passive"))
      (node (ref "JP13") (pin "6") (pinfunction "6_6") (pintype "passive"))
      (node (ref "JP13") (pin "7") (pinfunction "7_7") (pintype "passive"))
      (node (ref "JP13") (pin "8") (pinfunction "8_8") (pintype "passive"))
      (node (ref "JP13") (pin "9") (pinfunction "9_9") (pintype "passive"))
      (node (ref "JP16") (pin "1") (pinfunction "1_1") (pintype "passive"))
      (node (ref "JP5") (pin "1") (pinfunction "1_1") (pintype "passive"))
      (node (ref "JP5") (pin "10") (pinfunction "10_10") (pintype "passive"))
      (node (ref "JP5") (pin "2") (pinfunction "2_2") (pintype "passive"))
      (node (ref "JP5") (pin "3") (pinfunction "3_3") (pintype "passive"))
      (node (ref "JP5") (pin "4") (pinfunction "4_4") (pintype "passive"))
      (node (ref "JP5") (pin "5") (pinfunction "5_5") (pintype "passive"))
      (node (ref "JP5") (pin "6") (pinfunction "6_6") (pintype "passive"))
      (node (ref "JP5") (pin "7") (pinfunction "7_7") (pintype "passive"))
      (node (ref "JP5") (pin "8") (pinfunction "8_8") (pintype "passive"))
      (node (ref "JP5") (pin "9") (pinfunction "9_9") (pintype "passive"))
      (node (ref "JP6") (pin "1") (pinfunction "1_1") (pintype "passive"))
      (node (ref "JP6") (pin "2") (pinfunction "2_2") (pintype "passive"))
      (node (ref "JP6") (pin "3") (pinfunction "3_3") (pintype "passive"))
      (node (ref "JP6") (pin "4") (pinfunction "4_4") (pintype "passive"))
      (node (ref "JP6") (pin "5") (pinfunction "5_5") (pintype "passive"))
      (node (ref "JP6") (pin "6") (pinfunction "6_6") (pintype "passive"))
      (node (ref "R1") (pin "2") (pinfunction "2_2") (pintype "passive"))
      (node (ref "R62") (pin "2") (pinfunction "2_2") (pintype "passive"))
      (node (ref "R63") (pin "2") (pinfunction "2_2") (pintype "passive"))
      (node (ref "R64") (pin "2") (pinfunction "2_2") (pintype "passive"))
      (node (ref "R65") (pin "2") (pinfunction "2_2") (pintype "passive"))
    )
    (net (code "2") (name "12V") (class "Default")
      (node (ref "C1") (pin "1") (pinfunction "1_1") (pintype "passive"))
      (node (ref "IC1") (pin "IN") (pinfunction "IN_IN") (pintype "input"))
      (node (ref "JP110") (pin "PWR") (pinfunction "PWR_PWR") (pintype "bidirectional"))
      (node (ref "JP2") (pin "1") (pinfunction "1_1") (pintype "passive"))
      (node (ref "JP2") (pin "2") (pinfunction "2_2") (pintype "passive"))
      (node (ref "JP2") (pin "3") (pinfunction "3_3") (pintype "passive"))
      (node (ref "JP2") (pin "4") (pinfunction "4_4") (pintype "passive"))
      (node (ref "JP4") (pin "2") (pinfunction "2_2") (pintype "passive"))
    )
    (net (code "3") (name "A0C") (class "Default")
      (node (ref "IC2") (pin "A0") (pinfunction "A0_A0") (pintype "bidirectional"))
      (node (ref "IC2") (pin "A0_1") (pinfunction "A0_A0_1") (pintype "bidirectional"))
      (node (ref "JP102") (pin "1") (pinfunction "1_1") (pintype "passive"))
      (node (ref "JP102") (pin "2") (pinfunction "2_2") (pintype "passive"))
      (node (ref "JP102") (pin "3") (pinfunction "3_3") (pintype "passive"))
      (node (ref "JP102") (pin "4") (pinfunction "4_4") (pintype "passive"))
      (node (ref "JP102") (pin "5") (pinfunction "5_5") (pintype "passive"))
      (node (ref "JP102") (pin "6") (pinfunction "6_6") (pintype "passive"))
      (node (ref "JP102") (pin "7") (pinfunction "7_7") (pintype "passive"))
      (node (ref "JP102") (pin "8") (pinfunction "8_8") (pintype "passive"))
    )
    (net (code "4") (name "A1C") (class "Default")
      (node (ref "IC2") (pin "A1") (pinfunction "A1_A1") (pintype "bidirectional"))
      (node (ref "IC2") (pin "A1_1") (pinfunction "A1_A1_1") (pintype "bidirectional"))
      (node (ref "JP101") (pin "1") (pinfunction "1_1") (pintype "passive"))
      (node (ref "JP101") (pin "2") (pinfunction "2_2") (pintype "passive"))
      (node (ref "JP101") (pin "3") (pinfunction "3_3") (pintype "passive"))
      (node (ref "JP101") (pin "4") (pinfunction "4_4") (pintype "passive"))
      (node (ref "JP101") (pin "5") (pinfunction "5_5") (pintype "passive"))
      (node (ref "JP101") (pin "6") (pinfunction "6_6") (pintype "passive"))
      (node (ref "JP101") (pin "7") (pinfunction "7_7") (pintype "passive"))
      (node (ref "JP101") (pin "8") (pinfunction "8_8") (pintype "passive"))
    )
    (net (code "5") (name "A2C") (class "Default")
      (node (ref "IC2") (pin "A2") (pinfunction "A2_A2") (pintype "bidirectional"))
      (node (ref "IC2") (pin "A2_1") (pinfunction "A2_A2_1") (pintype "bidirectional"))
      (node (ref "JP100") (pin "1") (pinfunction "1_1") (pintype "passive"))
      (node (ref "JP100") (pin "2") (pinfunction "2_2") (pintype "passive"))
      (node (ref "JP100") (pin "3") (pinfunction "3_3") (pintype "passive"))
      (node (ref "JP100") (pin "4") (pinfunction "4_4") (pintype "passive"))
      (node (ref "JP100") (pin "5") (pinfunction "5_5") (pintype "passive"))
      (node (ref "JP100") (pin "6") (pinfunction "6_6") (pintype "passive"))
      (node (ref "JP100") (pin "7") (pinfunction "7_7") (pintype "passive"))
      (node (ref "JP100") (pin "8") (pinfunction "8_8") (pintype "passive"))
    )
    (net (code "6") (name "A3C") (class "Default")
      (node (ref "IC2") (pin "A3") (pinfunction "A3_A3") (pintype "bidirectional"))
      (node (ref "IC2") (pin "A3_1") (pinfunction "A3_A3_1") (pintype "bidirectional"))
      (node (ref "JP99") (pin "1") (pinfunction "1_1") (pintype "passive"))
      (node (ref "JP99") (pin "2") (pinfunction "2_2") (pintype "passive"))
      (node (ref "JP99") (pin "3") (pinfunction "3_3") (pintype "passive"))
      (node (ref "JP99") (pin "4") (pinfunction "4_4") (pintype "passive"))
      (node (ref "JP99") (pin "5") (pinfunction "5_5") (pintype "passive"))
      (node (ref "JP99") (pin "6") (pinfunction "6_6") (pintype "passive"))
      (node (ref "JP99") (pin "7") (pinfunction "7_7") (pintype "passive"))
      (node (ref "JP99") (pin "8") (pinfunction "8_8") (pintype "passive"))
    )
    (net (code "7") (name "A4C") (class "Default")
      (node (ref "IC2") (pin "A4") (pinfunction "A4_A4") (pintype "bidirectional"))
      (node (ref "IC2") (pin "A4_1") (pinfunction "A4_A4_1") (pintype "bidirectional"))
      (node (ref "JP98") (pin "1") (pinfunction "1_1") (pintype "passive"))
      (node (ref "JP98") (pin "2") (pinfunction "2_2") (pintype "passive"))
      (node (ref "JP98") (pin "3") (pinfunction "3_3") (pintype "passive"))
      (node (ref "JP98") (pin "4") (pinfunction "4_4") (pintype "passive"))
      (node (ref "JP98") (pin "5") (pinfunction "5_5") (pintype "passive"))
      (node (ref "JP98") (pin "6") (pinfunction "6_6") (pintype "passive"))
      (node (ref "JP98") (pin "7") (pinfunction "7_7") (pintype "passive"))
      (node (ref "JP98") (pin "8") (pinfunction "8_8") (pintype "passive"))
    )
    (net (code "8") (name "A5C") (class "Default")
      (node (ref "IC2") (pin "A5") (pinfunction "A5_A5") (pintype "bidirectional"))
      (node (ref "IC2") (pin "A5_1") (pinfunction "A5_A5_1") (pintype "bidirectional"))
      (node (ref "JP54") (pin "1") (pinfunction "1_1") (pintype "passive"))
      (node (ref "JP54") (pin "2") (pinfunction "2_2") (pintype "passive"))
      (node (ref "JP54") (pin "3") (pinfunction "3_3") (pintype "passive"))
      (node (ref "JP54") (pin "4") (pinfunction "4_4") (pintype "passive"))
      (node (ref "JP54") (pin "5") (pinfunction "5_5") (pintype "passive"))
      (node (ref "JP54") (pin "6") (pinfunction "6_6") (pintype "passive"))
      (node (ref "JP54") (pin "7") (pinfunction "7_7") (pintype "passive"))
      (node (ref "JP54") (pin "8") (pinfunction "8_8") (pintype "passive"))
    )
    (net (code "9") (name "B0C") (class "Default")
      (node (ref "IC2") (pin "B0") (pinfunction "B0_B0") (pintype "bidirectional"))
      (node (ref "IC2") (pin "B0_1") (pinfunction "B0_B0_1") (pintype "bidirectional"))
      (node (ref "JP108") (pin "1") (pinfunction "1_1") (pintype "passive"))
      (node (ref "JP108") (pin "2") (pinfunction "2_2") (pintype "passive"))
      (node (ref "JP108") (pin "3") (pinfunction "3_3") (pintype "passive"))
      (node (ref "JP108") (pin "4") (pinfunction "4_4") (pintype "passive"))
      (node (ref "JP108") (pin "5") (pinfunction "5_5") (pintype "passive"))
      (node (ref "JP108") (pin "6") (pinfunction "6_6") (pintype "passive"))
      (node (ref "JP108") (pin "7") (pinfunction "7_7") (pintype "passive"))
      (node (ref "JP108") (pin "8") (pinfunction "8_8") (pintype "passive"))
    )
    (net (code "10") (name "B1C") (class "Default")
      (node (ref "IC2") (pin "B1") (pinfunction "B1_B1") (pintype "bidirectional"))
      (node (ref "IC2") (pin "B1_1") (pinfunction "B1_B1_1") (pintype "bidirectional"))
      (node (ref "JP107") (pin "1") (pinfunction "1_1") (pintype "passive"))
      (node (ref "JP107") (pin "2") (pinfunction "2_2") (pintype "passive"))
      (node (ref "JP107") (pin "3") (pinfunction "3_3") (pintype "passive"))
      (node (ref "JP107") (pin "4") (pinfunction "4_4") (pintype "passive"))
      (node (ref "JP107") (pin "5") (pinfunction "5_5") (pintype "passive"))
      (node (ref "JP107") (pin "6") (pinfunction "6_6") (pintype "passive"))
      (node (ref "JP107") (pin "7") (pinfunction "7_7") (pintype "passive"))
      (node (ref "JP107") (pin "8") (pinfunction "8_8") (pintype "passive"))
    )
    (net (code "11") (name "B2C") (class "Default")
      (node (ref "IC2") (pin "B2") (pinfunction "B2_B2") (pintype "bidirectional"))
      (node (ref "IC2") (pin "B2_1") (pinfunction "B2_B2_1") (pintype "bidirectional"))
      (node (ref "JP106") (pin "1") (pinfunction "1_1") (pintype "passive"))
      (node (ref "JP106") (pin "2") (pinfunction "2_2") (pintype "passive"))
      (node (ref "JP106") (pin "3") (pinfunction "3_3") (pintype "passive"))
      (node (ref "JP106") (pin "4") (pinfunction "4_4") (pintype "passive"))
      (node (ref "JP106") (pin "5") (pinfunction "5_5") (pintype "passive"))
      (node (ref "JP106") (pin "6") (pinfunction "6_6") (pintype "passive"))
      (node (ref "JP106") (pin "7") (pinfunction "7_7") (pintype "passive"))
      (node (ref "JP106") (pin "8") (pinfunction "8_8") (pintype "passive"))
    )
    (net (code "12") (name "B3C") (class "Default")
      (node (ref "IC2") (pin "B3") (pinfunction "B3_B3") (pintype "bidirectional"))
      (node (ref "IC2") (pin "B3_1") (pinfunction "B3_B3_1") (pintype "bidirectional"))
      (node (ref "JP105") (pin "1") (pinfunction "1_1") (pintype "passive"))
      (node (ref "JP105") (pin "2") (pinfunction "2_2") (pintype "passive"))
      (node (ref "JP105") (pin "3") (pinfunction "3_3") (pintype "passive"))
      (node (ref "JP105") (pin "4") (pinfunction "4_4") (pintype "passive"))
      (node (ref "JP105") (pin "5") (pinfunction "5_5") (pintype "passive"))
      (node (ref "JP105") (pin "6") (pinfunction "6_6") (pintype "passive"))
      (node (ref "JP105") (pin "7") (pinfunction "7_7") (pintype "passive"))
      (node (ref "JP105") (pin "8") (pinfunction "8_8") (pintype "passive"))
    )
    (net (code "13") (name "B4C") (class "Default")
      (node (ref "IC2") (pin "B4") (pinfunction "B4_B4") (pintype "bidirectional"))
      (node (ref "IC2") (pin "B4_1") (pinfunction "B4_B4_1") (pintype "bidirectional"))
      (node (ref "JP104") (pin "1") (pinfunction "1_1") (pintype "passive"))
      (node (ref "JP104") (pin "2") (pinfunction "2_2") (pintype "passive"))
      (node (ref "JP104") (pin "3") (pinfunction "3_3") (pintype "passive"))
      (node (ref "JP104") (pin "4") (pinfunction "4_4") (pintype "passive"))
      (node (ref "JP104") (pin "5") (pinfunction "5_5") (pintype "passive"))
      (node (ref "JP104") (pin "6") (pinfunction "6_6") (pintype "passive"))
      (node (ref "JP104") (pin "7") (pinfunction "7_7") (pintype "passive"))
      (node (ref "JP104") (pin "8") (pinfunction "8_8") (pintype "passive"))
    )
    (net (code "14") (name "B5C") (class "Default")
      (node (ref "IC2") (pin "B5") (pinfunction "B5_B5") (pintype "bidirectional"))
      (node (ref "IC2") (pin "B5_1") (pinfunction "B5_B5_1") (pintype "bidirectional"))
      (node (ref "JP103") (pin "1") (pinfunction "1_1") (pintype "passive"))
      (node (ref "JP103") (pin "2") (pinfunction "2_2") (pintype "passive"))
      (node (ref "JP103") (pin "3") (pinfunction "3_3") (pintype "passive"))
      (node (ref "JP103") (pin "4") (pinfunction "4_4") (pintype "passive"))
      (node (ref "JP103") (pin "5") (pinfunction "5_5") (pintype "passive"))
      (node (ref "JP103") (pin "6") (pinfunction "6_6") (pintype "passive"))
      (node (ref "JP103") (pin "7") (pinfunction "7_7") (pintype "passive"))
      (node (ref "JP103") (pin "8") (pinfunction "8_8") (pintype "passive"))
    )
    (net (code "15") (name "C0C") (class "Default")
      (node (ref "IC2") (pin "C0") (pinfunction "C0_C0") (pintype "bidirectional"))
      (node (ref "IC2") (pin "C0_1") (pinfunction "C0_C0_1") (pintype "bidirectional"))
      (node (ref "JP29") (pin "1") (pinfunction "1_1") (pintype "passive"))
      (node (ref "JP29") (pin "2") (pinfunction "2_2") (pintype "passive"))
      (node (ref "JP29") (pin "3") (pinfunction "3_3") (pintype "passive"))
      (node (ref "JP29") (pin "4") (pinfunction "4_4") (pintype "passive"))
      (node (ref "JP29") (pin "5") (pinfunction "5_5") (pintype "passive"))
      (node (ref "JP29") (pin "6") (pinfunction "6_6") (pintype "passive"))
      (node (ref "JP29") (pin "7") (pinfunction "7_7") (pintype "passive"))
      (node (ref "JP29") (pin "8") (pinfunction "8_8") (pintype "passive"))
      (node (ref "R28") (pin "1") (pinfunction "1_1") (pintype "passive"))
    )
    (net (code "16") (name "C1C") (class "Default")
      (node (ref "IC2") (pin "C1") (pinfunction "C1_C1") (pintype "bidirectional"))
      (node (ref "IC2") (pin "C1_1") (pinfunction "C1_C1_1") (pintype "bidirectional"))
      (node (ref "JP28") (pin "1") (pinfunction "1_1") (pintype "passive"))
      (node (ref "JP28") (pin "2") (pinfunction "2_2") (pintype "passive"))
      (node (ref "JP28") (pin "3") (pinfunction "3_3") (pintype "passive"))
      (node (ref "JP28") (pin "4") (pinfunction "4_4") (pintype "passive"))
      (node (ref "JP28") (pin "5") (pinfunction "5_5") (pintype "passive"))
      (node (ref "JP28") (pin "6") (pinfunction "6_6") (pintype "passive"))
      (node (ref "JP28") (pin "7") (pinfunction "7_7") (pintype "passive"))
      (node (ref "JP28") (pin "8") (pinfunction "8_8") (pintype "passive"))
      (node (ref "R26") (pin "1") (pinfunction "1_1") (pintype "passive"))
    )
    (net (code "17") (name "C2C") (class "Default")
      (node (ref "IC2") (pin "C2") (pinfunction "C2_C2") (pintype "bidirectional"))
      (node (ref "IC2") (pin "C2_1") (pinfunction "C2_C2_1") (pintype "bidirectional"))
      (node (ref "JP27") (pin "1") (pinfunction "1_1") (pintype "passive"))
      (node (ref "JP27") (pin "2") (pinfunction "2_2") (pintype "passive"))
      (node (ref "JP27") (pin "3") (pinfunction "3_3") (pintype "passive"))
      (node (ref "JP27") (pin "4") (pinfunction "4_4") (pintype "passive"))
      (node (ref "JP27") (pin "5") (pinfunction "5_5") (pintype "passive"))
      (node (ref "JP27") (pin "6") (pinfunction "6_6") (pintype "passive"))
      (node (ref "JP27") (pin "7") (pinfunction "7_7") (pintype "passive"))
      (node (ref "JP27") (pin "8") (pinfunction "8_8") (pintype "passive"))
      (node (ref "R24") (pin "1") (pinfunction "1_1") (pintype "passive"))
    )
    (net (code "18") (name "C3C") (class "Default")
      (node (ref "IC2") (pin "C3") (pinfunction "C3_C3") (pintype "bidirectional"))
      (node (ref "IC2") (pin "C3_1") (pinfunction "C3_C3_1") (pintype "bidirectional"))
      (node (ref "JP26") (pin "1") (pinfunction "1_1") (pintype "passive"))
      (node (ref "JP26") (pin "2") (pinfunction "2_2") (pintype "passive"))
      (node (ref "JP26") (pin "3") (pinfunction "3_3") (pintype "passive"))
      (node (ref "JP26") (pin "4") (pinfunction "4_4") (pintype "passive"))
      (node (ref "JP26") (pin "5") (pinfunction "5_5") (pintype "passive"))
      (node (ref "JP26") (pin "6") (pinfunction "6_6") (pintype "passive"))
      (node (ref "JP26") (pin "7") (pinfunction "7_7") (pintype "passive"))
      (node (ref "JP26") (pin "8") (pinfunction "8_8") (pintype "passive"))
      (node (ref "R22") (pin "1") (pinfunction "1_1") (pintype "passive"))
    )
    (net (code "19") (name "C4C") (class "Default")
      (node (ref "IC2") (pin "C4") (pinfunction "C4_C4") (pintype "bidirectional"))
      (node (ref "IC2") (pin "C4_1") (pinfunction "C4_C4_1") (pintype "bidirectional"))
      (node (ref "JP25") (pin "1") (pinfunction "1_1") (pintype "passive"))
      (node (ref "JP25") (pin "2") (pinfunction "2_2") (pintype "passive"))
      (node (ref "JP25") (pin "3") (pinfunction "3_3") (pintype "passive"))
      (node (ref "JP25") (pin "4") (pinfunction "4_4") (pintype "passive"))
      (node (ref "JP25") (pin "5") (pinfunction "5_5") (pintype "passive"))
      (node (ref "JP25") (pin "6") (pinfunction "6_6") (pintype "passive"))
      (node (ref "JP25") (pin "7") (pinfunction "7_7") (pintype "passive"))
      (node (ref "JP25") (pin "8") (pinfunction "8_8") (pintype "passive"))
      (node (ref "R20") (pin "1") (pinfunction "1_1") (pintype "passive"))
      (node (ref "R65") (pin "1") (pinfunction "1_1") (pintype "passive"))
    )
    (net (code "20") (name "C5C") (class "Default")
      (node (ref "IC2") (pin "C5") (pinfunction "C5_C5") (pintype "bidirectional"))
      (node (ref "IC2") (pin "C5_1") (pinfunction "C5_C5_1") (pintype "bidirectional"))
      (node (ref "JP24") (pin "1") (pinfunction "1_1") (pintype "passive"))
      (node (ref "JP24") (pin "2") (pinfunction "2_2") (pintype "passive"))
      (node (ref "JP24") (pin "3") (pinfunction "3_3") (pintype "passive"))
      (node (ref "JP24") (pin "4") (pinfunction "4_4") (pintype "passive"))
      (node (ref "JP24") (pin "5") (pinfunction "5_5") (pintype "passive"))
      (node (ref "JP24") (pin "6") (pinfunction "6_6") (pintype "passive"))
      (node (ref "JP24") (pin "7") (pinfunction "7_7") (pintype "passive"))
      (node (ref "JP24") (pin "8") (pinfunction "8_8") (pintype "passive"))
      (node (ref "R18") (pin "1") (pinfunction "1_1") (pintype "passive"))
      (node (ref "R64") (pin "1") (pinfunction "1_1") (pintype "passive"))
    )
    (net (code "21") (name "D0C") (class "Default")
      (node (ref "IC2") (pin "D0") (pinfunction "D0_D0") (pintype "bidirectional"))
      (node (ref "IC2") (pin "D0_1") (pinfunction "D0_D0_1") (pintype "bidirectional"))
      (node (ref "JP22") (pin "1") (pinfunction "1_1") (pintype "passive"))
      (node (ref "JP22") (pin "2") (pinfunction "2_2") (pintype "passive"))
      (node (ref "JP22") (pin "3") (pinfunction "3_3") (pintype "passive"))
      (node (ref "JP22") (pin "4") (pinfunction "4_4") (pintype "passive"))
      (node (ref "JP22") (pin "5") (pinfunction "5_5") (pintype "passive"))
      (node (ref "JP22") (pin "6") (pinfunction "6_6") (pintype "passive"))
      (node (ref "JP22") (pin "7") (pinfunction "7_7") (pintype "passive"))
      (node (ref "JP22") (pin "8") (pinfunction "8_8") (pintype "passive"))
      (node (ref "R16") (pin "1") (pinfunction "1_1") (pintype "passive"))
      (node (ref "R62") (pin "1") (pinfunction "1_1") (pintype "passive"))
    )
    (net (code "22") (name "D1C") (class "Default")
      (node (ref "IC2") (pin "D1") (pinfunction "D1_D1") (pintype "bidirectional"))
      (node (ref "IC2") (pin "D1_1") (pinfunction "D1_D1_1") (pintype "bidirectional"))
      (node (ref "JP21") (pin "1") (pinfunction "1_1") (pintype "passive"))
      (node (ref "JP21") (pin "2") (pinfunction "2_2") (pintype "passive"))
      (node (ref "JP21") (pin "3") (pinfunction "3_3") (pintype "passive"))
      (node (ref "JP21") (pin "4") (pinfunction "4_4") (pintype "passive"))
      (node (ref "JP21") (pin "5") (pinfunction "5_5") (pintype "passive"))
      (node (ref "JP21") (pin "6") (pinfunction "6_6") (pintype "passive"))
      (node (ref "JP21") (pin "7") (pinfunction "7_7") (pintype "passive"))
      (node (ref "JP21") (pin "8") (pinfunction "8_8") (pintype "passive"))
      (node (ref "R14") (pin "1") (pinfunction "1_1") (pintype "passive"))
      (node (ref "R63") (pin "1") (pinfunction "1_1") (pintype "passive"))
    )
    (net (code "23") (name "D2C") (class "Default")
      (node (ref "IC2") (pin "D2") (pinfunction "D2_D2") (pintype "bidirectional"))
      (node (ref "IC2") (pin "D2_1") (pinfunction "D2_D2_1") (pintype "bidirectional"))
      (node (ref "JP20") (pin "1") (pinfunction "1_1") (pintype "passive"))
      (node (ref "JP20") (pin "2") (pinfunction "2_2") (pintype "passive"))
      (node (ref "JP20") (pin "3") (pinfunction "3_3") (pintype "passive"))
      (node (ref "JP20") (pin "4") (pinfunction "4_4") (pintype "passive"))
      (node (ref "JP20") (pin "5") (pinfunction "5_5") (pintype "passive"))
      (node (ref "JP20") (pin "6") (pinfunction "6_6") (pintype "passive"))
      (node (ref "JP20") (pin "7") (pinfunction "7_7") (pintype "passive"))
      (node (ref "JP20") (pin "8") (pinfunction "8_8") (pintype "passive"))
      (node (ref "R12") (pin "1") (pinfunction "1_1") (pintype "passive"))
    )
    (net (code "24") (name "D3C") (class "Default")
      (node (ref "IC2") (pin "D3") (pinfunction "D3_D3") (pintype "bidirectional"))
      (node (ref "IC2") (pin "D3_1") (pinfunction "D3_D3_1") (pintype "bidirectional"))
      (node (ref "JP19") (pin "1") (pinfunction "1_1") (pintype "passive"))
      (node (ref "JP19") (pin "2") (pinfunction "2_2") (pintype "passive"))
      (node (ref "JP19") (pin "3") (pinfunction "3_3") (pintype "passive"))
      (node (ref "JP19") (pin "4") (pinfunction "4_4") (pintype "passive"))
      (node (ref "JP19") (pin "5") (pinfunction "5_5") (pintype "passive"))
      (node (ref "JP19") (pin "6") (pinfunction "6_6") (pintype "passive"))
      (node (ref "JP19") (pin "7") (pinfunction "7_7") (pintype "passive"))
      (node (ref "JP19") (pin "8") (pinfunction "8_8") (pintype "passive"))
      (node (ref "R10") (pin "1") (pinfunction "1_1") (pintype "passive"))
    )
    (net (code "25") (name "D4C") (class "Default")
      (node (ref "IC2") (pin "D4") (pinfunction "D4_D4") (pintype "bidirectional"))
      (node (ref "IC2") (pin "D4_1") (pinfunction "D4_D4_1") (pintype "bidirectional"))
      (node (ref "JP18") (pin "1") (pinfunction "1_1") (pintype "passive"))
      (node (ref "JP18") (pin "2") (pinfunction "2_2") (pintype "passive"))
      (node (ref "JP18") (pin "3") (pinfunction "3_3") (pintype "passive"))
      (node (ref "JP18") (pin "4") (pinfunction "4_4") (pintype "passive"))
      (node (ref "JP18") (pin "5") (pinfunction "5_5") (pintype "passive"))
      (node (ref "JP18") (pin "6") (pinfunction "6_6") (pintype "passive"))
      (node (ref "JP18") (pin "7") (pinfunction "7_7") (pintype "passive"))
      (node (ref "JP18") (pin "8") (pinfunction "8_8") (pintype "passive"))
      (node (ref "R8") (pin "2") (pinfunction "2_2") (pintype "passive"))
    )
    (net (code "26") (name "D5C") (class "Default")
      (node (ref "IC2") (pin "D5") (pinfunction "D5_D5") (pintype "bidirectional"))
      (node (ref "IC2") (pin "D5_1") (pinfunction "D5_D5_1") (pintype "bidirectional"))
      (node (ref "JP10") (pin "1") (pinfunction "1_1") (pintype "passive"))
      (node (ref "JP10") (pin "2") (pinfunction "2_2") (pintype "passive"))
      (node (ref "JP10") (pin "3") (pinfunction "3_3") (pintype "passive"))
      (node (ref "JP10") (pin "4") (pinfunction "4_4") (pintype "passive"))
      (node (ref "JP10") (pin "5") (pinfunction "5_5") (pintype "passive"))
      (node (ref "JP10") (pin "6") (pinfunction "6_6") (pintype "passive"))
      (node (ref "JP10") (pin "7") (pinfunction "7_7") (pintype "passive"))
      (node (ref "JP10") (pin "8") (pinfunction "8_8") (pintype "passive"))
      (node (ref "R6") (pin "2") (pinfunction "2_2") (pintype "passive"))
    )
    (net (code "27") (name "D6C") (class "Default")
      (node (ref "IC2") (pin "D6") (pinfunction "D6_D6") (pintype "bidirectional"))
      (node (ref "IC2") (pin "D6_1") (pinfunction "D6_D6_1") (pintype "bidirectional"))
      (node (ref "JP7") (pin "1") (pinfunction "1_1") (pintype "passive"))
      (node (ref "JP7") (pin "2") (pinfunction "2_2") (pintype "passive"))
      (node (ref "JP7") (pin "3") (pinfunction "3_3") (pintype "passive"))
      (node (ref "JP7") (pin "4") (pinfunction "4_4") (pintype "passive"))
      (node (ref "JP7") (pin "5") (pinfunction "5_5") (pintype "passive"))
      (node (ref "JP7") (pin "6") (pinfunction "6_6") (pintype "passive"))
      (node (ref "JP7") (pin "7") (pinfunction "7_7") (pintype "passive"))
      (node (ref "JP7") (pin "8") (pinfunction "8_8") (pintype "passive"))
      (node (ref "R4") (pin "2") (pinfunction "2_2") (pintype "passive"))
    )
    (net (code "28") (name "D7C") (class "Default")
      (node (ref "IC2") (pin "D7") (pinfunction "D7_D7") (pintype "bidirectional"))
      (node (ref "IC2") (pin "D7_1") (pinfunction "D7_D7_1") (pintype "bidirectional"))
      (node (ref "JP1") (pin "1") (pinfunction "1_1") (pintype "passive"))
      (node (ref "JP1") (pin "2") (pinfunction "2_2") (pintype "passive"))
      (node (ref "JP1") (pin "3") (pinfunction "3_3") (pintype "passive"))
      (node (ref "JP1") (pin "4") (pinfunction "4_4") (pintype "passive"))
      (node (ref "JP1") (pin "5") (pinfunction "5_5") (pintype "passive"))
      (node (ref "JP1") (pin "6") (pinfunction "6_6") (pintype "passive"))
      (node (ref "JP1") (pin "7") (pinfunction "7_7") (pintype "passive"))
      (node (ref "JP1") (pin "8") (pinfunction "8_8") (pintype "passive"))
      (node (ref "R3") (pin "2") (pinfunction "2_2") (pintype "passive"))
    )
    (net (code "29") (name "DACC") (class "Default")
      (node (ref "IC2") (pin "DAC") (pinfunction "DAC_DAC") (pintype "bidirectional"))
      (node (ref "IC2") (pin "DAC_1") (pinfunction "DAC_DAC_1") (pintype "bidirectional"))
      (node (ref "JP15") (pin "1") (pinfunction "1_1") (pintype "passive"))
      (node (ref "JP15") (pin "2") (pinfunction "2_2") (pintype "passive"))
      (node (ref "JP15") (pin "3") (pinfunction "3_3") (pintype "passive"))
      (node (ref "JP15") (pin "4") (pinfunction "4_4") (pintype "passive"))
      (node (ref "JP15") (pin "5") (pinfunction "5_5") (pintype "passive"))
      (node (ref "JP15") (pin "6") (pinfunction "6_6") (pintype "passive"))
      (node (ref "JP15") (pin "7") (pinfunction "7_7") (pintype "passive"))
      (node (ref "JP15") (pin "8") (pinfunction "8_8") (pintype "passive"))
    )
    (net (code "30") (name "GND") (class "Default")
      (node (ref "C1") (pin "2") (pinfunction "2_2") (pintype "passive"))
      (node (ref "C2") (pin "2") (pinfunction "2_2") (pintype "passive"))
      (node (ref "C3") (pin "2") (pinfunction "2_2") (pintype "passive"))
      (node (ref "C4") (pin "2") (pinfunction "2_2") (pintype "passive"))
      (node (ref "C5") (pin "2") (pinfunction "2_2") (pintype "passive"))
      (node (ref "C6") (pin "2") (pinfunction "2_2") (pintype "passive"))
      (node (ref "C7") (pin "2") (pinfunction "2_2") (pintype "passive"))
      (node (ref "D1") (pin "C") (pinfunction "C_C") (pintype "passive"))
      (node (ref "IC1") (pin "GND") (pinfunction "GND_GND") (pintype "input"))
      (node (ref "IC2") (pin "GND") (pinfunction "GND_GND") (pintype "power_in"))
      (node (ref "IC2") (pin "GND@2") (pinfunction "GND_GND@2") (pintype "power_in"))
      (node (ref "IC2") (pin "GND_1") (pinfunction "GND_GND_1") (pintype "power_in"))
      (node (ref "IC2") (pin "GND_1B") (pinfunction "GND_GND_1B") (pintype "power_in"))
      (node (ref "JP109") (pin "1") (pinfunction "1_1") (pintype "passive"))
      (node (ref "JP109") (pin "2") (pinfunction "2_2") (pintype "passive"))
      (node (ref "JP109") (pin "3") (pinfunction "3_3") (pintype "passive"))
      (node (ref "JP109") (pin "4") (pinfunction "4_4") (pintype "passive"))
      (node (ref "JP11") (pin "1") (pinfunction "1_1") (pintype "passive"))
      (node (ref "JP11") (pin "10") (pinfunction "10_10") (pintype "passive"))
      (node (ref "JP11") (pin "2") (pinfunction "2_2") (pintype "passive"))
      (node (ref "JP11") (pin "3") (pinfunction "3_3") (pintype "passive"))
      (node (ref "JP11") (pin "4") (pinfunction "4_4") (pintype "passive"))
      (node (ref "JP11") (pin "5") (pinfunction "5_5") (pintype "passive"))
      (node (ref "JP11") (pin "6") (pinfunction "6_6") (pintype "passive"))
      (node (ref "JP11") (pin "7") (pinfunction "7_7") (pintype "passive"))
      (node (ref "JP11") (pin "8") (pinfunction "8_8") (pintype "passive"))
      (node (ref "JP11") (pin "9") (pinfunction "9_9") (pintype "passive"))
      (node (ref "JP110") (pin "GND") (pinfunction "GND_GND") (pintype "bidirectional"))
      (node (ref "JP110") (pin "GNDBREAK") (pinfunction "GNDBREAK_GNDBREAK") (pintype "bidirectional"))
      (node (ref "JP14") (pin "1") (pinfunction "1_1") (pintype "passive"))
      (node (ref "JP14") (pin "10") (pinfunction "10_10") (pintype "passive"))
      (node (ref "JP14") (pin "11") (pinfunction "11_11") (pintype "passive"))
      (node (ref "JP14") (pin "12") (pinfunction "12_12") (pintype "passive"))
      (node (ref "JP14") (pin "13") (pinfunction "13_13") (pintype "passive"))
      (node (ref "JP14") (pin "14") (pinfunction "14_14") (pintype "passive"))
      (node (ref "JP14") (pin "15") (pinfunction "15_15") (pintype "passive"))
      (node (ref "JP14") (pin "16") (pinfunction "16_16") (pintype "passive"))
      (node (ref "JP14") (pin "2") (pinfunction "2_2") (pintype "passive"))
      (node (ref "JP14") (pin "3") (pinfunction "3_3") (pintype "passive"))
      (node (ref "JP14") (pin "4") (pinfunction "4_4") (pintype "passive"))
      (node (ref "JP14") (pin "5") (pinfunction "5_5") (pintype "passive"))
      (node (ref "JP14") (pin "6") (pinfunction "6_6") (pintype "passive"))
      (node (ref "JP14") (pin "7") (pinfunction "7_7") (pintype "passive"))
      (node (ref "JP14") (pin "8") (pinfunction "8_8") (pintype "passive"))
      (node (ref "JP14") (pin "9") (pinfunction "9_9") (pintype "passive"))
      (node (ref "JP23") (pin "1") (pinfunction "1_1") (pintype "passive"))
      (node (ref "JP23") (pin "2") (pinfunction "2_2") (pintype "passive"))
      (node (ref "JP23") (pin "3") (pinfunction "3_3") (pintype "passive"))
      (node (ref "JP23") (pin "4") (pinfunction "4_4") (pintype "passive"))
      (node (ref "JP23") (pin "5") (pinfunction "5_5") (pintype "passive"))
      (node (ref "JP23") (pin "6") (pinfunction "6_6") (pintype "passive"))
      (node (ref "JP23") (pin "7") (pinfunction "7_7") (pintype "passive"))
      (node (ref "JP23") (pin "8") (pinfunction "8_8") (pintype "passive"))
      (node (ref "JP33") (pin "1") (pinfunction "1_1") (pintype "passive"))
      (node (ref "JP4") (pin "1") (pinfunction "1_1") (pintype "passive"))
    )
    (net (code "31") (name "LED_COMMON") (class "Default")
      (node (ref "JP30") (pin "1") (pinfunction "1_1") (pintype "passive"))
      (node (ref "R11") (pin "2") (pinfunction "2_2") (pintype "passive"))
      (node (ref "R13") (pin "2") (pinfunction "2_2") (pintype "passive"))
      (node (ref "R15") (pin "2") (pinfunction "2_2") (pintype "passive"))
      (node (ref "R17") (pin "2") (pinfunction "2_2") (pintype "passive"))
      (node (ref "R19") (pin "2") (pinfunction "2_2") (pintype "passive"))
      (node (ref "R2") (pin "1") (pinfunction "1_1") (pintype "passive"))
      (node (ref "R21") (pin "2") (pinfunction "2_2") (pintype "passive"))
      (node (ref "R23") (pin "2") (pinfunction "2_2") (pintype "passive"))
      (node (ref "R25") (pin "1") (pinfunction "1_1") (pintype "passive"))
      (node (ref "R27") (pin "1") (pinfunction "1_1") (pintype "passive"))
      (node (ref "R29") (pin "1") (pinfunction "1_1") (pintype "passive"))
      (node (ref "R5") (pin "1") (pinfunction "1_1") (pintype "passive"))
      (node (ref "R7") (pin "1") (pinfunction "1_1") (pintype "passive"))
      (node (ref "R9") (pin "1") (pinfunction "1_1") (pintype "passive"))
    )
    (net (code "32") (name "Net-(D1-PadA)") (class "Default")
      (node (ref "D1") (pin "A") (pinfunction "A_A") (pintype "passive"))
      (node (ref "R1") (pin "1") (pinfunction "1_1") (pintype "passive"))
    )
    (net (code "33") (name "Net-(IC2-PadVBAT)") (class "Default")
      (node (ref "IC2") (pin "VBAT") (pinfunction "VBAT_VBAT") (pintype "passive"))
      (node (ref "IC2") (pin "VBATT_1") (pinfunction "VBAT_VBATT_1") (pintype "passive"))
    )
    (net (code "34") (name "Net-(IC2-~{RST}-PadRST)") (class "Default")
      (node (ref "IC2") (pin "RST") (pinfunction "~{RST}_RST") (pintype "bidirectional"))
      (node (ref "IC2") (pin "RST_1") (pinfunction "~{RST}_RST_1") (pintype "bidirectional"))
    )
    (net (code "35") (name "Net-(JP8-Pad1)") (class "Default")
      (node (ref "JP8") (pin "1") (pinfunction "1_1") (pintype "passive"))
      (node (ref "JP8") (pin "2") (pinfunction "2_2") (pintype "passive"))
    )
    (net (code "36") (name "Net-(JP31-Pad1)") (class "Default")
      (node (ref "JP31") (pin "1") (pinfunction "1_1") (pintype "passive"))
      (node (ref "JP31") (pin "2") (pinfunction "2_2") (pintype "passive"))
      (node (ref "R31") (pin "2") (pinfunction "2_2") (pintype "passive"))
    )
    (net (code "37") (name "Net-(JP32-Pad1)") (class "Default")
      (node (ref "JP32") (pin "1") (pinfunction "1_1") (pintype "passive"))
      (node (ref "JP32") (pin "2") (pinfunction "2_2") (pintype "passive"))
    )
    (net (code "38") (name "Net-(JP34-Pad1)") (class "Default")
      (node (ref "JP34") (pin "1") (pinfunction "1_1") (pintype "passive"))
      (node (ref "JP34") (pin "2") (pinfunction "2_2") (pintype "passive"))
      (node (ref "R48") (pin "2") (pinfunction "2_2") (pintype "passive"))
    )
    (net (code "39") (name "Net-(JP35-Pad1)") (class "Default")
      (node (ref "JP35") (pin "1") (pinfunction "1_1") (pintype "passive"))
      (node (ref "R37") (pin "1") (pinfunction "1_1") (pintype "passive"))
    )
    (net (code "40") (name "Net-(JP36-Pad1)") (class "Default")
      (node (ref "JP36") (pin "1") (pinfunction "1_1") (pintype "passive"))
      (node (ref "R30") (pin "1") (pinfunction "1_1") (pintype "passive"))
    )
    (net (code "41") (name "Net-(JP37-Pad1)") (class "Default")
      (node (ref "JP37") (pin "1") (pinfunction "1_1") (pintype "passive"))
      (node (ref "R46") (pin "1") (pinfunction "1_1") (pintype "passive"))
    )
    (net (code "42") (name "Net-(JP38-Pad1)") (class "Default")
      (node (ref "JP38") (pin "1") (pinfunction "1_1") (pintype "passive"))
      (node (ref "JP38") (pin "2") (pinfunction "2_2") (pintype "passive"))
      (node (ref "R32") (pin "2") (pinfunction "2_2") (pintype "passive"))
    )
    (net (code "43") (name "Net-(JP39-Pad1)") (class "Default")
      (node (ref "JP39") (pin "1") (pinfunction "1_1") (pintype "passive"))
      (node (ref "JP39") (pin "2") (pinfunction "2_2") (pintype "passive"))
      (node (ref "R49") (pin "2") (pinfunction "2_2") (pintype "passive"))
    )
    (net (code "44") (name "Net-(JP40-Pad1)") (class "Default")
      (node (ref "JP40") (pin "1") (pinfunction "1_1") (pintype "passive"))
      (node (ref "R31") (pin "1") (pinfunction "1_1") (pintype "passive"))
    )
    (net (code "45") (name "Net-(JP41-Pad1)") (class "Default")
      (node (ref "JP41") (pin "1") (pinfunction "1_1") (pintype "passive"))
      (node (ref "R32") (pin "1") (pinfunction "1_1") (pintype "passive"))
    )
    (net (code "46") (name "Net-(JP43-Pad1)") (class "Default")
      (node (ref "JP43") (pin "1") (pinfunction "1_1") (pintype "passive"))
      (node (ref "R34") (pin "1") (pinfunction "1_1") (pintype "passive"))
    )
    (net (code "47") (name "Net-(JP44-Pad1)") (class "Default")
      (node (ref "JP44") (pin "1") (pinfunction "1_1") (pintype "passive"))
      (node (ref "R35") (pin "1") (pinfunction "1_1") (pintype "passive"))
    )
    (net (code "48") (name "Net-(JP45-Pad1)") (class "Default")
      (node (ref "JP45") (pin "1") (pinfunction "1_1") (pintype "passive"))
      (node (ref "R36") (pin "1") (pinfunction "1_1") (pintype "passive"))
    )
    (net (code "49") (name "Net-(JP46-Pad1)") (class "Default")
      (node (ref "JP46") (pin "1") (pinfunction "1_1") (pintype "passive"))
      (node (ref "R38") (pin "1") (pinfunction "1_1") (pintype "passive"))
    )
    (net (code "50") (name "Net-(JP47-Pad1)") (class "Default")
      (node (ref "JP47") (pin "1") (pinfunction "1_1") (pintype "passive"))
      (node (ref "R39") (pin "1") (pinfunction "1_1") (pintype "passive"))
    )
    (net (code "51") (name "Net-(JP48-Pad1)") (class "Default")
      (node (ref "JP48") (pin "1") (pinfunction "1_1") (pintype "passive"))
      (node (ref "R40") (pin "1") (pinfunction "1_1") (pintype "passive"))
    )
    (net (code "52") (name "Net-(JP49-Pad1)") (class "Default")
      (node (ref "JP49") (pin "1") (pinfunction "1_1") (pintype "passive"))
      (node (ref "R41") (pin "1") (pinfunction "1_1") (pintype "passive"))
    )
    (net (code "53") (name "Net-(JP50-Pad1)") (class "Default")
      (node (ref "JP50") (pin "1") (pinfunction "1_1") (pintype "passive"))
      (node (ref "R42") (pin "1") (pinfunction "1_1") (pintype "passive"))
    )
    (net (code "54") (name "Net-(JP51-Pad1)") (class "Default")
      (node (ref "JP51") (pin "1") (pinfunction "1_1") (pintype "passive"))
      (node (ref "R43") (pin "1") (pinfunction "1_1") (pintype "passive"))
    )
    (net (code "55") (name "Net-(JP52-Pad1)") (class "Default")
      (node (ref "JP52") (pin "1") (pinfunction "1_1") (pintype "passive"))
      (node (ref "R44") (pin "1") (pinfunction "1_1") (pintype "passive"))
    )
    (net (code "56") (name "Net-(JP53-Pad1)") (class "Default")
      (node (ref "JP53") (pin "1") (pinfunction "1_1") (pintype "passive"))
      (node (ref "R45") (pin "1") (pinfunction "1_1") (pintype "passive"))
    )
    (net (code "57") (name "Net-(JP55-Pad1)") (class "Default")
      (node (ref "JP55") (pin "1") (pinfunction "1_1") (pintype "passive"))
      (node (ref "JP55") (pin "2") (pinfunction "2_2") (pintype "passive"))
      (node (ref "R30") (pin "2") (pinfunction "2_2") (pintype "passive"))
    )
    (net (code "58") (name "Net-(JP56-Pad1)") (class "Default")
      (node (ref "JP56") (pin "1") (pinfunction "1_1") (pintype "passive"))
      (node (ref "R47") (pin "1") (pinfunction "1_1") (pintype "passive"))
    )
    (net (code "59") (name "Net-(JP57-Pad1)") (class "Default")
      (node (ref "JP57") (pin "1") (pinfunction "1_1") (pintype "passive"))
      (node (ref "R48") (pin "1") (pinfunction "1_1") (pintype "passive"))
    )
    (net (code "60") (name "Net-(JP59-Pad1)") (class "Default")
      (node (ref "JP59") (pin "1") (pinfunction "1_1") (pintype "passive"))
      (node (ref "R50") (pin "1") (pinfunction "1_1") (pintype "passive"))
    )
    (net (code "61") (name "Net-(JP60-Pad1)") (class "Default")
      (node (ref "JP60") (pin "1") (pinfunction "1_1") (pintype "passive"))
      (node (ref "R51") (pin "1") (pinfunction "1_1") (pintype "passive"))
    )
    (net (code "62") (name "Net-(JP61-Pad1)") (class "Default")
      (node (ref "JP61") (pin "1") (pinfunction "1_1") (pintype "passive"))
      (node (ref "R52") (pin "1") (pinfunction "1_1") (pintype "passive"))
    )
    (net (code "63") (name "Net-(JP62-Pad1)") (class "Default")
      (node (ref "JP62") (pin "1") (pinfunction "1_1") (pintype "passive"))
      (node (ref "R53") (pin "1") (pinfunction "1_1") (pintype "passive"))
    )
    (net (code "64") (name "Net-(JP63-Pad1)") (class "Default")
      (node (ref "JP63") (pin "1") (pinfunction "1_1") (pintype "passive"))
      (node (ref "R54") (pin "1") (pinfunction "1_1") (pintype "passive"))
    )
    (net (code "65") (name "Net-(JP64-Pad1)") (class "Default")
      (node (ref "JP64") (pin "1") (pinfunction "1_1") (pintype "passive"))
      (node (ref "R55") (pin "1") (pinfunction "1_1") (pintype "passive"))
    )
    (net (code "66") (name "Net-(JP65-Pad1)") (class "Default")
      (node (ref "JP65") (pin "1") (pinfunction "1_1") (pintype "passive"))
      (node (ref "R56") (pin "1") (pinfunction "1_1") (pintype "passive"))
    )
    (net (code "67") (name "Net-(JP66-Pad1)") (class "Default")
      (node (ref "JP66") (pin "1") (pinfunction "1_1") (pintype "passive"))
      (node (ref "R57") (pin "1") (pinfunction "1_1") (pintype "passive"))
    )
    (net (code "68") (name "Net-(JP67-Pad1)") (class "Default")
      (node (ref "JP67") (pin "1") (pinfunction "1_1") (pintype "passive"))
      (node (ref "R58") (pin "1") (pinfunction "1_1") (pintype "passive"))
    )
    (net (code "69") (name "Net-(JP68-Pad1)") (class "Default")
      (node (ref "JP68") (pin "1") (pinfunction "1_1") (pintype "passive"))
      (node (ref "R59") (pin "1") (pinfunction "1_1") (pintype "passive"))
    )
    (net (code "70") (name "Net-(JP69-Pad1)") (class "Default")
      (node (ref "JP69") (pin "1") (pinfunction "1_1") (pintype "passive"))
      (node (ref "R60") (pin "1") (pinfunction "1_1") (pintype "passive"))
    )
    (net (code "71") (name "Net-(JP70-Pad1)") (class "Default")
      (node (ref "JP70") (pin "1") (pinfunction "1_1") (pintype "passive"))
      (node (ref "R61") (pin "1") (pinfunction "1_1") (pintype "passive"))
    )
    (net (code "72") (name "Net-(JP71-Pad1)") (class "Default")
      (node (ref "JP71") (pin "1") (pinfunction "1_1") (pintype "passive"))
      (node (ref "JP71") (pin "2") (pinfunction "2_2") (pintype "passive"))
      (node (ref "R46") (pin "2") (pinfunction "2_2") (pintype "passive"))
    )
    (net (code "73") (name "Net-(JP72-Pad1)") (class "Default")
      (node (ref "JP72") (pin "1") (pinfunction "1_1") (pintype "passive"))
      (node (ref "JP72") (pin "2") (pinfunction "2_2") (pintype "passive"))
      (node (ref "R47") (pin "2") (pinfunction "2_2") (pintype "passive"))
    )
    (net (code "74") (name "Net-(JP73-Pad1)") (class "Default")
      (node (ref "JP73") (pin "1") (pinfunction "1_1") (pintype "passive"))
      (node (ref "JP73") (pin "2") (pinfunction "2_2") (pintype "passive"))
      (node (ref "R50") (pin "2") (pinfunction "2_2") (pintype "passive"))
    )
    (net (code "75") (name "Net-(JP74-Pad1)") (class "Default")
      (node (ref "JP74") (pin "1") (pinfunction "1_1") (pintype "passive"))
      (node (ref "JP74") (pin "2") (pinfunction "2_2") (pintype "passive"))
      (node (ref "R51") (pin "2") (pinfunction "2_2") (pintype "passive"))
    )
    (net (code "76") (name "Net-(JP75-Pad1)") (class "Default")
      (node (ref "JP75") (pin "1") (pinfunction "1_1") (pintype "passive"))
      (node (ref "JP75") (pin "2") (pinfunction "2_2") (pintype "passive"))
      (node (ref "R52") (pin "2") (pinfunction "2_2") (pintype "passive"))
    )
    (net (code "77") (name "Net-(JP76-Pad1)") (class "Default")
      (node (ref "JP76") (pin "1") (pinfunction "1_1") (pintype "passive"))
      (node (ref "JP76") (pin "2") (pinfunction "2_2") (pintype "passive"))
      (node (ref "R53") (pin "2") (pinfunction "2_2") (pintype "passive"))
    )
    (net (code "78") (name "Net-(JP77-Pad1)") (class "Default")
      (node (ref "JP77") (pin "1") (pinfunction "1_1") (pintype "passive"))
      (node (ref "JP77") (pin "2") (pinfunction "2_2") (pintype "passive"))
      (node (ref "R54") (pin "2") (pinfunction "2_2") (pintype "passive"))
    )
    (net (code "79") (name "Net-(JP78-Pad1)") (class "Default")
      (node (ref "JP78") (pin "1") (pinfunction "1_1") (pintype "passive"))
      (node (ref "JP78") (pin "2") (pinfunction "2_2") (pintype "passive"))
      (node (ref "R55") (pin "2") (pinfunction "2_2") (pintype "passive"))
    )
    (net (code "80") (name "Net-(JP79-Pad1)") (class "Default")
      (node (ref "JP79") (pin "1") (pinfunction "1_1") (pintype "passive"))
      (node (ref "JP79") (pin "2") (pinfunction "2_2") (pintype "passive"))
      (node (ref "R56") (pin "2") (pinfunction "2_2") (pintype "passive"))
    )
    (net (code "81") (name "Net-(JP80-Pad1)") (class "Default")
      (node (ref "JP80") (pin "1") (pinfunction "1_1") (pintype "passive"))
      (node (ref "JP80") (pin "2") (pinfunction "2_2") (pintype "passive"))
      (node (ref "R57") (pin "2") (pinfunction "2_2") (pintype "passive"))
    )
    (net (code "82") (name "Net-(JP81-Pad1)") (class "Default")
      (node (ref "JP81") (pin "1") (pinfunction "1_1") (pintype "passive"))
      (node (ref "JP81") (pin "2") (pinfunction "2_2") (pintype "passive"))
      (node (ref "R58") (pin "2") (pinfunction "2_2") (pintype "passive"))
    )
    (net (code "83") (name "Net-(JP82-Pad1)") (class "Default")
      (node (ref "JP82") (pin "1") (pinfunction "1_1") (pintype "passive"))
      (node (ref "JP82") (pin "2") (pinfunction "2_2") (pintype "passive"))
      (node (ref "R59") (pin "2") (pinfunction "2_2") (pintype "passive"))
    )
    (net (code "84") (name "Net-(JP83-Pad1)") (class "Default")
      (node (ref "JP83") (pin "1") (pinfunction "1_1") (pintype "passive"))
      (node (ref "JP83") (pin "2") (pinfunction "2_2") (pintype "passive"))
      (node (ref "R60") (pin "2") (pinfunction "2_2") (pintype "passive"))
    )
    (net (code "85") (name "Net-(JP84-Pad1)") (class "Default")
      (node (ref "JP84") (pin "1") (pinfunction "1_1") (pintype "passive"))
      (node (ref "JP84") (pin "2") (pinfunction "2_2") (pintype "passive"))
      (node (ref "R61") (pin "2") (pinfunction "2_2") (pintype "passive"))
    )
    (net (code "86") (name "Net-(JP85-Pad1)") (class "Default")
      (node (ref "JP85") (pin "1") (pinfunction "1_1") (pintype "passive"))
      (node (ref "JP85") (pin "2") (pinfunction "2_2") (pintype "passive"))
      (node (ref "R33") (pin "2") (pinfunction "2_2") (pintype "passive"))
    )
    (net (code "87") (name "Net-(JP86-Pad1)") (class "Default")
      (node (ref "JP86") (pin "1") (pinfunction "1_1") (pintype "passive"))
      (node (ref "JP86") (pin "2") (pinfunction "2_2") (pintype "passive"))
      (node (ref "R34") (pin "2") (pinfunction "2_2") (pintype "passive"))
    )
    (net (code "88") (name "Net-(JP87-Pad1)") (class "Default")
      (node (ref "JP87") (pin "1") (pinfunction "1_1") (pintype "passive"))
      (node (ref "JP87") (pin "2") (pinfunction "2_2") (pintype "passive"))
      (node (ref "R35") (pin "2") (pinfunction "2_2") (pintype "passive"))
    )
    (net (code "89") (name "Net-(JP88-Pad1)") (class "Default")
      (node (ref "JP88") (pin "1") (pinfunction "1_1") (pintype "passive"))
      (node (ref "JP88") (pin "2") (pinfunction "2_2") (pintype "passive"))
      (node (ref "R36") (pin "2") (pinfunction "2_2") (pintype "passive"))
    )
    (net (code "90") (name "Net-(JP89-Pad1)") (class "Default")
      (node (ref "JP89") (pin "1") (pinfunction "1_1") (pintype "passive"))
      (node (ref "JP89") (pin "2") (pinfunction "2_2") (pintype "passive"))
      (node (ref "R37") (pin "2") (pinfunction "2_2") (pintype "passive"))
    )
    (net (code "91") (name "Net-(JP90-Pad1)") (class "Default")
      (node (ref "JP90") (pin "1") (pinfunction "1_1") (pintype "passive"))
      (node (ref "JP90") (pin "2") (pinfunction "2_2") (pintype "passive"))
      (node (ref "R38") (pin "2") (pinfunction "2_2") (pintype "passive"))
    )
    (net (code "92") (name "Net-(JP91-Pad1)") (class "Default")
      (node (ref "JP91") (pin "1") (pinfunction "1_1") (pintype "passive"))
      (node (ref "JP91") (pin "2") (pinfunction "2_2") (pintype "passive"))
      (node (ref "R39") (pin "2") (pinfunction "2_2") (pintype "passive"))
    )
    (net (code "93") (name "Net-(JP92-Pad1)") (class "Default")
      (node (ref "JP92") (pin "1") (pinfunction "1_1") (pintype "passive"))
      (node (ref "JP92") (pin "2") (pinfunction "2_2") (pintype "passive"))
      (node (ref "R40") (pin "2") (pinfunction "2_2") (pintype "passive"))
    )
    (net (code "94") (name "Net-(JP93-Pad1)") (class "Default")
      (node (ref "JP93") (pin "1") (pinfunction "1_1") (pintype "passive"))
      (node (ref "JP93") (pin "2") (pinfunction "2_2") (pintype "passive"))
      (node (ref "R41") (pin "2") (pinfunction "2_2") (pintype "passive"))
    )
    (net (code "95") (name "Net-(JP94-Pad1)") (class "Default")
      (node (ref "JP94") (pin "1") (pinfunction "1_1") (pintype "passive"))
      (node (ref "JP94") (pin "2") (pinfunction "2_2") (pintype "passive"))
      (node (ref "R42") (pin "2") (pinfunction "2_2") (pintype "passive"))
    )
    (net (code "96") (name "Net-(JP95-Pad1)") (class "Default")
      (node (ref "JP95") (pin "1") (pinfunction "1_1") (pintype "passive"))
      (node (ref "JP95") (pin "2") (pinfunction "2_2") (pintype "passive"))
      (node (ref "R43") (pin "2") (pinfunction "2_2") (pintype "passive"))
    )
    (net (code "97") (name "Net-(JP96-Pad1)") (class "Default")
      (node (ref "JP96") (pin "1") (pinfunction "1_1") (pintype "passive"))
      (node (ref "JP96") (pin "2") (pinfunction "2_2") (pintype "passive"))
      (node (ref "R44") (pin "2") (pinfunction "2_2") (pintype "passive"))
    )
    (net (code "98") (name "Net-(JP97-Pad1)") (class "Default")
      (node (ref "JP97") (pin "1") (pinfunction "1_1") (pintype "passive"))
      (node (ref "JP97") (pin "2") (pinfunction "2_2") (pintype "passive"))
      (node (ref "R45") (pin "2") (pinfunction "2_2") (pintype "passive"))
    )
    (net (code "99") (name "Net-(JP111-Pad1)") (class "Default")
      (node (ref "JP111") (pin "1") (pinfunction "1_1") (pintype "passive"))
      (node (ref "U2") (pin "8") (pinfunction "8_8") (pintype "bidirectional"))
    )
    (net (code "100") (name "Net-(JP111-Pad2)") (class "Default")
      (node (ref "JP111") (pin "2") (pinfunction "2_2") (pintype "passive"))
      (node (ref "U2") (pin "7") (pinfunction "7_7") (pintype "bidirectional"))
    )
    (net (code "101") (name "Net-(JP111-Pad3)") (class "Default")
      (node (ref "JP111") (pin "3") (pinfunction "3_3") (pintype "passive"))
      (node (ref "U2") (pin "6") (pinfunction "6_6") (pintype "bidirectional"))
    )
    (net (code "102") (name "Net-(JP111-Pad4)") (class "Default")
      (node (ref "JP111") (pin "4") (pinfunction "4_4") (pintype "passive"))
      (node (ref "U2") (pin "5") (pinfunction "5_5") (pintype "bidirectional"))
    )
    (net (code "103") (name "Net-(JP112-Pad1)") (class "Default")
      (node (ref "JP112") (pin "1") (pinfunction "1_1") (pintype "passive"))
      (node (ref "U3") (pin "8") (pinfunction "8_8") (pintype "bidirectional"))
    )
    (net (code "104") (name "Net-(JP112-Pad2)") (class "Default")
      (node (ref "JP112") (pin "2") (pinfunction "2_2") (pintype "passive"))
      (node (ref "U3") (pin "7") (pinfunction "7_7") (pintype "bidirectional"))
    )
    (net (code "105") (name "Net-(JP112-Pad3)") (class "Default")
      (node (ref "JP112") (pin "3") (pinfunction "3_3") (pintype "passive"))
      (node (ref "U3") (pin "6") (pinfunction "6_6") (pintype "bidirectional"))
    )
    (net (code "106") (name "Net-(JP112-Pad4)") (class "Default")
      (node (ref "JP112") (pin "4") (pinfunction "4_4") (pintype "passive"))
      (node (ref "U3") (pin "5") (pinfunction "5_5") (pintype "bidirectional"))
    )
    (net (code "107") (name "Net-(JP115-Pad1)") (class "Default")
      (node (ref "JP115") (pin "1") (pinfunction "1_1") (pintype "passive"))
      (node (ref "JP115") (pin "2") (pinfunction "2_2") (pintype "passive"))
    )
    (net (code "108") (name "Net-(JP116-Pad1)") (class "Default")
      (node (ref "JP116") (pin "1") (pinfunction "1_1") (pintype "passive"))
      (node (ref "U2") (pin "4") (pinfunction "4_4") (pintype "bidirectional"))
    )
    (net (code "109") (name "Net-(JP116-Pad2)") (class "Default")
      (node (ref "JP116") (pin "2") (pinfunction "2_2") (pintype "passive"))
      (node (ref "U2") (pin "3") (pinfunction "3_3") (pintype "bidirectional"))
    )
    (net (code "110") (name "Net-(JP116-Pad3)") (class "Default")
      (node (ref "JP116") (pin "3") (pinfunction "3_3") (pintype "passive"))
      (node (ref "U2") (pin "2") (pinfunction "2_2") (pintype "bidirectional"))
    )
    (net (code "111") (name "Net-(JP116-Pad4)") (class "Default")
      (node (ref "JP116") (pin "4") (pinfunction "4_4") (pintype "passive"))
      (node (ref "U2") (pin "1") (pinfunction "1_1") (pintype "bidirectional"))
    )
    (net (code "112") (name "Net-(JP117-Pad1)") (class "Default")
      (node (ref "JP117") (pin "1") (pinfunction "1_1") (pintype "passive"))
      (node (ref "U3") (pin "4") (pinfunction "4_4") (pintype "bidirectional"))
    )
    (net (code "113") (name "Net-(JP117-Pad2)") (class "Default")
      (node (ref "JP117") (pin "2") (pinfunction "2_2") (pintype "passive"))
      (node (ref "U3") (pin "3") (pinfunction "3_3") (pintype "bidirectional"))
    )
    (net (code "114") (name "Net-(JP117-Pad3)") (class "Default")
      (node (ref "JP117") (pin "3") (pinfunction "3_3") (pintype "passive"))
      (node (ref "U3") (pin "2") (pinfunction "2_2") (pintype "bidirectional"))
    )
    (net (code "115") (name "Net-(JP117-Pad4)") (class "Default")
      (node (ref "JP117") (pin "4") (pinfunction "4_4") (pintype "passive"))
      (node (ref "U3") (pin "1") (pinfunction "1_1") (pintype "bidirectional"))
    )
    (net (code "116") (name "Net-(JP118-Pad1)") (class "Default")
      (node (ref "JP118") (pin "1") (pinfunction "1_1") (pintype "passive"))
      (node (ref "JP118") (pin "2") (pinfunction "2_2") (pintype "passive"))
    )
    (net (code "117") (name "Net-(JP121-Pad1)") (class "Default")
      (node (ref "JP121") (pin "1") (pinfunction "1_1") (pintype "passive"))
      (node (ref "R49") (pin "1") (pinfunction "1_1") (pintype "passive"))
    )
    (net (code "118") (name "Net-(JP123-Pad1)") (class "Default")
      (node (ref "JP123") (pin "1") (pinfunction "1_1") (pintype "passive"))
      (node (ref "R33") (pin "1") (pinfunction "1_1") (pintype "passive"))
    )
    (net (code "119") (name "Net-(R2-Pad2)") (class "Default")
      (node (ref "R2") (pin "2") (pinfunction "2_2") (pintype "passive"))
      (node (ref "R3") (pin "1") (pinfunction "1_1") (pintype "passive"))
    )
    (net (code "120") (name "Net-(R4-Pad1)") (class "Default")
      (node (ref "R4") (pin "1") (pinfunction "1_1") (pintype "passive"))
      (node (ref "R5") (pin "2") (pinfunction "2_2") (pintype "passive"))
    )
    (net (code "121") (name "Net-(R6-Pad1)") (class "Default")
      (node (ref "R6") (pin "1") (pinfunction "1_1") (pintype "passive"))
      (node (ref "R7") (pin "2") (pinfunction "2_2") (pintype "passive"))
    )
    (net (code "122") (name "Net-(R8-Pad1)") (class "Default")
      (node (ref "R8") (pin "1") (pinfunction "1_1") (pintype "passive"))
      (node (ref "R9") (pin "2") (pinfunction "2_2") (pintype "passive"))
    )
    (net (code "123") (name "Net-(R10-Pad2)") (class "Default")
      (node (ref "R10") (pin "2") (pinfunction "2_2") (pintype "passive"))
      (node (ref "R11") (pin "1") (pinfunction "1_1") (pintype "passive"))
    )
    (net (code "124") (name "Net-(R12-Pad2)") (class "Default")
      (node (ref "R12") (pin "2") (pinfunction "2_2") (pintype "passive"))
      (node (ref "R13") (pin "1") (pinfunction "1_1") (pintype "passive"))
    )
    (net (code "125") (name "Net-(R14-Pad2)") (class "Default")
      (node (ref "R14") (pin "2") (pinfunction "2_2") (pintype "passive"))
      (node (ref "R15") (pin "1") (pinfunction "1_1") (pintype "passive"))
    )
    (net (code "126") (name "Net-(R16-Pad2)") (class "Default")
      (node (ref "R16") (pin "2") (pinfunction "2_2") (pintype "passive"))
      (node (ref "R17") (pin "1") (pinfunction "1_1") (pintype "passive"))
    )
    (net (code "127") (name "Net-(R18-Pad2)") (class "Default")
      (node (ref "R18") (pin "2") (pinfunction "2_2") (pintype "passive"))
      (node (ref "R19") (pin "1") (pinfunction "1_1") (pintype "passive"))
    )
    (net (code "128") (name "Net-(R20-Pad2)") (class "Default")
      (node (ref "R20") (pin "2") (pinfunction "2_2") (pintype "passive"))
      (node (ref "R21") (pin "1") (pinfunction "1_1") (pintype "passive"))
    )
    (net (code "129") (name "Net-(R22-Pad2)") (class "Default")
      (node (ref "R22") (pin "2") (pinfunction "2_2") (pintype "passive"))
      (node (ref "R23") (pin "1") (pinfunction "1_1") (pintype "passive"))
    )
    (net (code "130") (name "Net-(R24-Pad2)") (class "Default")
      (node (ref "R24") (pin "2") (pinfunction "2_2") (pintype "passive"))
      (node (ref "R25") (pin "2") (pinfunction "2_2") (pintype "passive"))
    )
    (net (code "131") (name "Net-(R26-Pad2)") (class "Default")
      (node (ref "R26") (pin "2") (pinfunction "2_2") (pintype "passive"))
      (node (ref "R27") (pin "2") (pinfunction "2_2") (pintype "passive"))
    )
    (net (code "132") (name "Net-(R28-Pad2)") (class "Default")
      (node (ref "R28") (pin "2") (pinfunction "2_2") (pintype "passive"))
      (node (ref "R29") (pin "2") (pinfunction "2_2") (pintype "passive"))
    )
    (net (code "133") (name "RXC") (class "Default")
      (node (ref "IC2") (pin "RX") (pinfunction "RX_RX") (pintype "bidirectional"))
      (node (ref "IC2") (pin "RX_1") (pinfunction "RX_RX_1") (pintype "bidirectional"))
      (node (ref "JP12") (pin "1") (pinfunction "1_1") (pintype "passive"))
      (node (ref "JP12") (pin "2") (pinfunction "2_2") (pintype "passive"))
      (node (ref "JP12") (pin "3") (pinfunction "3_3") (pintype "passive"))
      (node (ref "JP12") (pin "4") (pinfunction "4_4") (pintype "passive"))
      (node (ref "JP12") (pin "5") (pinfunction "5_5") (pintype "passive"))
      (node (ref "JP12") (pin "6") (pinfunction "6_6") (pintype "passive"))
      (node (ref "JP12") (pin "7") (pinfunction "7_7") (pintype "passive"))
      (node (ref "JP12") (pin "8") (pinfunction "8_8") (pintype "passive"))
    )
    (net (code "134") (name "TXC") (class "Default")
      (node (ref "IC2") (pin "TX") (pinfunction "TX_TX") (pintype "bidirectional"))
      (node (ref "IC2") (pin "TX_1") (pinfunction "TX_TX_1") (pintype "bidirectional"))
      (node (ref "JP17") (pin "1") (pinfunction "1_1") (pintype "passive"))
      (node (ref "JP17") (pin "2") (pinfunction "2_2") (pintype "passive"))
      (node (ref "JP17") (pin "3") (pinfunction "3_3") (pintype "passive"))
      (node (ref "JP17") (pin "4") (pinfunction "4_4") (pintype "passive"))
      (node (ref "JP17") (pin "5") (pinfunction "5_5") (pintype "passive"))
      (node (ref "JP17") (pin "6") (pinfunction "6_6") (pintype "passive"))
      (node (ref "JP17") (pin "7") (pinfunction "7_7") (pintype "passive"))
      (node (ref "JP17") (pin "8") (pinfunction "8_8") (pintype "passive"))
    )
    (net (code "135") (name "VIN") (class "Default")
      (node (ref "C2") (pin "1") (pinfunction "1_1") (pintype "passive"))
      (node (ref "IC1") (pin "OUT") (pinfunction "OUT_OUT") (pintype "passive"))
      (node (ref "IC2") (pin "VIN") (pinfunction "VIN_VIN") (pintype "power_in"))
      (node (ref "IC2") (pin "VIN_1B") (pinfunction "VIN_VIN_1B") (pintype "power_in"))
      (node (ref "JP3") (pin "1") (pinfunction "1_1") (pintype "passive"))
      (node (ref "JP3") (pin "2") (pinfunction "2_2") (pintype "passive"))
      (node (ref "JP3") (pin "3") (pinfunction "3_3") (pintype "passive"))
      (node (ref "JP3") (pin "4") (pinfunction "4_4") (pintype "passive"))
    )
    (net (code "136") (name "WKPC") (class "Default")
      (node (ref "IC2") (pin "WKP") (pinfunction "WKP_WKP") (pintype "bidirectional"))
      (node (ref "IC2") (pin "WKP_1") (pinfunction "WKP_WKP_1") (pintype "bidirectional"))
      (node (ref "JP9") (pin "1") (pinfunction "1_1") (pintype "passive"))
      (node (ref "JP9") (pin "2") (pinfunction "2_2") (pintype "passive"))
      (node (ref "JP9") (pin "3") (pinfunction "3_3") (pintype "passive"))
      (node (ref "JP9") (pin "4") (pinfunction "4_4") (pintype "passive"))
      (node (ref "JP9") (pin "5") (pinfunction "5_5") (pintype "passive"))
      (node (ref "JP9") (pin "6") (pinfunction "6_6") (pintype "passive"))
      (node (ref "JP9") (pin "7") (pinfunction "7_7") (pintype "passive"))
      (node (ref "JP9") (pin "8") (pinfunction "8_8") (pintype "passive"))
    )
    (net (code "137") (name "unconnected-(JP35-Pad2)") (class "Default")
      (node (ref "JP35") (pin "2") (pinfunction "2_2") (pintype "passive"))
    )
    (net (code "138") (name "unconnected-(JP35-Pad3)") (class "Default")
      (node (ref "JP35") (pin "3") (pinfunction "3_3") (pintype "passive"))
    )
    (net (code "139") (name "unconnected-(JP35-Pad4)") (class "Default")
      (node (ref "JP35") (pin "4") (pinfunction "4_4") (pintype "passive"))
    )
    (net (code "140") (name "unconnected-(JP35-Pad5)") (class "Default")
      (node (ref "JP35") (pin "5") (pinfunction "5_5") (pintype "passive"))
    )
    (net (code "141") (name "unconnected-(JP35-Pad6)") (class "Default")
      (node (ref "JP35") (pin "6") (pinfunction "6_6") (pintype "passive"))
    )
    (net (code "142") (name "unconnected-(JP35-Pad7)") (class "Default")
      (node (ref "JP35") (pin "7") (pinfunction "7_7") (pintype "passive"))
    )
    (net (code "143") (name "unconnected-(JP35-Pad8)") (class "Default")
      (node (ref "JP35") (pin "8") (pinfunction "8_8") (pintype "passive"))
    )
    (net (code "144") (name "unconnected-(JP35-Pad9)") (class "Default")
      (node (ref "JP35") (pin "9") (pinfunction "9_9") (pintype "passive"))
    )
    (net (code "145") (name "unconnected-(JP35-Pad10)") (class "Default")
      (node (ref "JP35") (pin "10") (pinfunction "10_10") (pintype "passive"))
    )
    (net (code "146") (name "unconnected-(JP35-Pad11)") (class "Default")
      (node (ref "JP35") (pin "11") (pinfunction "11_11") (pintype "passive"))
    )
    (net (code "147") (name "unconnected-(JP35-Pad12)") (class "Default")
      (node (ref "JP35") (pin "12") (pinfunction "12_12") (pintype "passive"))
    )
    (net (code "148") (name "unconnected-(JP35-Pad13)") (class "Default")
      (node (ref "JP35") (pin "13") (pinfunction "13_13") (pintype "passive"))
    )
    (net (code "149") (name "unconnected-(JP35-Pad14)") (class "Default")
      (node (ref "JP35") (pin "14") (pinfunction "14_14") (pintype "passive"))
    )
    (net (code "150") (name "unconnected-(JP35-Pad15)") (class "Default")
      (node (ref "JP35") (pin "15") (pinfunction "15_15") (pintype "passive"))
    )
    (net (code "151") (name "unconnected-(JP35-Pad16)") (class "Default")
      (node (ref "JP35") (pin "16") (pinfunction "16_16") (pintype "passive"))
    )
    (net (code "152") (name "unconnected-(JP36-Pad2)") (class "Default")
      (node (ref "JP36") (pin "2") (pinfunction "2_2") (pintype "passive"))
    )
    (net (code "153") (name "unconnected-(JP36-Pad3)") (class "Default")
      (node (ref "JP36") (pin "3") (pinfunction "3_3") (pintype "passive"))
    )
    (net (code "154") (name "unconnected-(JP36-Pad4)") (class "Default")
      (node (ref "JP36") (pin "4") (pinfunction "4_4") (pintype "passive"))
    )
    (net (code "155") (name "unconnected-(JP36-Pad5)") (class "Default")
      (node (ref "JP36") (pin "5") (pinfunction "5_5") (pintype "passive"))
    )
    (net (code "156") (name "unconnected-(JP36-Pad6)") (class "Default")
      (node (ref "JP36") (pin "6") (pinfunction "6_6") (pintype "passive"))
    )
    (net (code "157") (name "unconnected-(JP36-Pad7)") (class "Default")
      (node (ref "JP36") (pin "7") (pinfunction "7_7") (pintype "passive"))
    )
    (net (code "158") (name "unconnected-(JP36-Pad8)") (class "Default")
      (node (ref "JP36") (pin "8") (pinfunction "8_8") (pintype "passive"))
    )
    (net (code "159") (name "unconnected-(JP36-Pad9)") (class "Default")
      (node (ref "JP36") (pin "9") (pinfunction "9_9") (pintype "passive"))
    )
    (net (code "160") (name "unconnected-(JP36-Pad10)") (class "Default")
      (node (ref "JP36") (pin "10") (pinfunction "10_10") (pintype "passive"))
    )
    (net (code "161") (name "unconnected-(JP36-Pad11)") (class "Default")
      (node (ref "JP36") (pin "11") (pinfunction "11_11") (pintype "passive"))
    )
    (net (code "162") (name "unconnected-(JP36-Pad12)") (class "Default")
      (node (ref "JP36") (pin "12") (pinfunction "12_12") (pintype "passive"))
    )
    (net (code "163") (name "unconnected-(JP36-Pad13)") (class "Default")
      (node (ref "JP36") (pin "13") (pinfunction "13_13") (pintype "passive"))
    )
    (net (code "164") (name "unconnected-(JP36-Pad14)") (class "Default")
      (node (ref "JP36") (pin "14") (pinfunction "14_14") (pintype "passive"))
    )
    (net (code "165") (name "unconnected-(JP36-Pad15)") (class "Default")
      (node (ref "JP36") (pin "15") (pinfunction "15_15") (pintype "passive"))
    )
    (net (code "166") (name "unconnected-(JP36-Pad16)") (class "Default")
      (node (ref "JP36") (pin "16") (pinfunction "16_16") (pintype "passive"))
    )
    (net (code "167") (name "unconnected-(JP37-Pad2)") (class "Default")
      (node (ref "JP37") (pin "2") (pinfunction "2_2") (pintype "passive"))
    )
    (net (code "168") (name "unconnected-(JP37-Pad3)") (class "Default")
      (node (ref "JP37") (pin "3") (pinfunction "3_3") (pintype "passive"))
    )
    (net (code "169") (name "unconnected-(JP37-Pad4)") (class "Default")
      (node (ref "JP37") (pin "4") (pinfunction "4_4") (pintype "passive"))
    )
    (net (code "170") (name "unconnected-(JP37-Pad5)") (class "Default")
      (node (ref "JP37") (pin "5") (pinfunction "5_5") (pintype "passive"))
    )
    (net (code "171") (name "unconnected-(JP37-Pad6)") (class "Default")
      (node (ref "JP37") (pin "6") (pinfunction "6_6") (pintype "passive"))
    )
    (net (code "172") (name "unconnected-(JP37-Pad7)") (class "Default")
      (node (ref "JP37") (pin "7") (pinfunction "7_7") (pintype "passive"))
    )
    (net (code "173") (name "unconnected-(JP37-Pad8)") (class "Default")
      (node (ref "JP37") (pin "8") (pinfunction "8_8") (pintype "passive"))
    )
    (net (code "174") (name "unconnected-(JP37-Pad9)") (class "Default")
      (node (ref "JP37") (pin "9") (pinfunction "9_9") (pintype "passive"))
    )
    (net (code "175") (name "unconnected-(JP37-Pad10)") (class "Default")
      (node (ref "JP37") (pin "10") (pinfunction "10_10") (pintype "passive"))
    )
    (net (code "176") (name "unconnected-(JP37-Pad11)") (class "Default")
      (node (ref "JP37") (pin "11") (pinfunction "11_11") (pintype "passive"))
    )
    (net (code "177") (name "unconnected-(JP37-Pad12)") (class "Default")
      (node (ref "JP37") (pin "12") (pinfunction "12_12") (pintype "passive"))
    )
    (net (code "178") (name "unconnected-(JP37-Pad13)") (class "Default")
      (node (ref "JP37") (pin "13") (pinfunction "13_13") (pintype "passive"))
    )
    (net (code "179") (name "unconnected-(JP37-Pad14)") (class "Default")
      (node (ref "JP37") (pin "14") (pinfunction "14_14") (pintype "passive"))
    )
    (net (code "180") (name "unconnected-(JP37-Pad15)") (class "Default")
      (node (ref "JP37") (pin "15") (pinfunction "15_15") (pintype "passive"))
    )
    (net (code "181") (name "unconnected-(JP37-Pad16)") (class "Default")
      (node (ref "JP37") (pin "16") (pinfunction "16_16") (pintype "passive"))
    )
    (net (code "182") (name "unconnected-(JP40-Pad2)") (class "Default")
      (node (ref "JP40") (pin "2") (pinfunction "2_2") (pintype "passive"))
    )
    (net (code "183") (name "unconnected-(JP40-Pad3)") (class "Default")
      (node (ref "JP40") (pin "3") (pinfunction "3_3") (pintype "passive"))
    )
    (net (code "184") (name "unconnected-(JP40-Pad4)") (class "Default")
      (node (ref "JP40") (pin "4") (pinfunction "4_4") (pintype "passive"))
    )
    (net (code "185") (name "unconnected-(JP40-Pad5)") (class "Default")
      (node (ref "JP40") (pin "5") (pinfunction "5_5") (pintype "passive"))
    )
    (net (code "186") (name "unconnected-(JP40-Pad6)") (class "Default")
      (node (ref "JP40") (pin "6") (pinfunction "6_6") (pintype "passive"))
    )
    (net (code "187") (name "unconnected-(JP40-Pad7)") (class "Default")
      (node (ref "JP40") (pin "7") (pinfunction "7_7") (pintype "passive"))
    )
    (net (code "188") (name "unconnected-(JP40-Pad8)") (class "Default")
      (node (ref "JP40") (pin "8") (pinfunction "8_8") (pintype "passive"))
    )
    (net (code "189") (name "unconnected-(JP40-Pad9)") (class "Default")
      (node (ref "JP40") (pin "9") (pinfunction "9_9") (pintype "passive"))
    )
    (net (code "190") (name "unconnected-(JP40-Pad10)") (class "Default")
      (node (ref "JP40") (pin "10") (pinfunction "10_10") (pintype "passive"))
    )
    (net (code "191") (name "unconnected-(JP40-Pad11)") (class "Default")
      (node (ref "JP40") (pin "11") (pinfunction "11_11") (pintype "passive"))
    )
    (net (code "192") (name "unconnected-(JP40-Pad12)") (class "Default")
      (node (ref "JP40") (pin "12") (pinfunction "12_12") (pintype "passive"))
    )
    (net (code "193") (name "unconnected-(JP40-Pad13)") (class "Default")
      (node (ref "JP40") (pin "13") (pinfunction "13_13") (pintype "passive"))
    )
    (net (code "194") (name "unconnected-(JP40-Pad14)") (class "Default")
      (node (ref "JP40") (pin "14") (pinfunction "14_14") (pintype "passive"))
    )
    (net (code "195") (name "unconnected-(JP40-Pad15)") (class "Default")
      (node (ref "JP40") (pin "15") (pinfunction "15_15") (pintype "passive"))
    )
    (net (code "196") (name "unconnected-(JP40-Pad16)") (class "Default")
      (node (ref "JP40") (pin "16") (pinfunction "16_16") (pintype "passive"))
    )
    (net (code "197") (name "unconnected-(JP41-Pad2)") (class "Default")
      (node (ref "JP41") (pin "2") (pinfunction "2_2") (pintype "passive"))
    )
    (net (code "198") (name "unconnected-(JP41-Pad3)") (class "Default")
      (node (ref "JP41") (pin "3") (pinfunction "3_3") (pintype "passive"))
    )
    (net (code "199") (name "unconnected-(JP41-Pad4)") (class "Default")
      (node (ref "JP41") (pin "4") (pinfunction "4_4") (pintype "passive"))
    )
    (net (code "200") (name "unconnected-(JP41-Pad5)") (class "Default")
      (node (ref "JP41") (pin "5") (pinfunction "5_5") (pintype "passive"))
    )
    (net (code "201") (name "unconnected-(JP41-Pad6)") (class "Default")
      (node (ref "JP41") (pin "6") (pinfunction "6_6") (pintype "passive"))
    )
    (net (code "202") (name "unconnected-(JP41-Pad7)") (class "Default")
      (node (ref "JP41") (pin "7") (pinfunction "7_7") (pintype "passive"))
    )
    (net (code "203") (name "unconnected-(JP41-Pad8)") (class "Default")
      (node (ref "JP41") (pin "8") (pinfunction "8_8") (pintype "passive"))
    )
    (net (code "204") (name "unconnected-(JP41-Pad9)") (class "Default")
      (node (ref "JP41") (pin "9") (pinfunction "9_9") (pintype "passive"))
    )
    (net (code "205") (name "unconnected-(JP41-Pad10)") (class "Default")
      (node (ref "JP41") (pin "10") (pinfunction "10_10") (pintype "passive"))
    )
    (net (code "206") (name "unconnected-(JP41-Pad11)") (class "Default")
      (node (ref "JP41") (pin "11") (pinfunction "11_11") (pintype "passive"))
    )
    (net (code "207") (name "unconnected-(JP41-Pad12)") (class "Default")
      (node (ref "JP41") (pin "12") (pinfunction "12_12") (pintype "passive"))
    )
    (net (code "208") (name "unconnected-(JP41-Pad13)") (class "Default")
      (node (ref "JP41") (pin "13") (pinfunction "13_13") (pintype "passive"))
    )
    (net (code "209") (name "unconnected-(JP41-Pad14)") (class "Default")
      (node (ref "JP41") (pin "14") (pinfunction "14_14") (pintype "passive"))
    )
    (net (code "210") (name "unconnected-(JP41-Pad15)") (class "Default")
      (node (ref "JP41") (pin "15") (pinfunction "15_15") (pintype "passive"))
    )
    (net (code "211") (name "unconnected-(JP41-Pad16)") (class "Default")
      (node (ref "JP41") (pin "16") (pinfunction "16_16") (pintype "passive"))
    )
    (net (code "212") (name "unconnected-(JP42-Pad1)") (class "Default")
      (node (ref "JP42") (pin "1") (pinfunction "1_1") (pintype "passive"))
    )
    (net (code "213") (name "unconnected-(JP42-Pad2)") (class "Default")
      (node (ref "JP42") (pin "2") (pinfunction "2_2") (pintype "passive"))
    )
    (net (code "214") (name "unconnected-(JP42-Pad3)") (class "Default")
      (node (ref "JP42") (pin "3") (pinfunction "3_3") (pintype "passive"))
    )
    (net (code "215") (name "unconnected-(JP42-Pad4)") (class "Default")
      (node (ref "JP42") (pin "4") (pinfunction "4_4") (pintype "passive"))
    )
    (net (code "216") (name "unconnected-(JP42-Pad5)") (class "Default")
      (node (ref "JP42") (pin "5") (pinfunction "5_5") (pintype "passive"))
    )
    (net (code "217") (name "unconnected-(JP42-Pad6)") (class "Default")
      (node (ref "JP42") (pin "6") (pinfunction "6_6") (pintype "passive"))
    )
    (net (code "218") (name "unconnected-(JP42-Pad7)") (class "Default")
      (node (ref "JP42") (pin "7") (pinfunction "7_7") (pintype "passive"))
    )
    (net (code "219") (name "unconnected-(JP42-Pad8)") (class "Default")
      (node (ref "JP42") (pin "8") (pinfunction "8_8") (pintype "passive"))
    )
    (net (code "220") (name "unconnected-(JP42-Pad9)") (class "Default")
      (node (ref "JP42") (pin "9") (pinfunction "9_9") (pintype "passive"))
    )
    (net (code "221") (name "unconnected-(JP42-Pad10)") (class "Default")
      (node (ref "JP42") (pin "10") (pinfunction "10_10") (pintype "passive"))
    )
    (net (code "222") (name "unconnected-(JP42-Pad11)") (class "Default")
      (node (ref "JP42") (pin "11") (pinfunction "11_11") (pintype "passive"))
    )
    (net (code "223") (name "unconnected-(JP42-Pad12)") (class "Default")
      (node (ref "JP42") (pin "12") (pinfunction "12_12") (pintype "passive"))
    )
    (net (code "224") (name "unconnected-(JP42-Pad13)") (class "Default")
      (node (ref "JP42") (pin "13") (pinfunction "13_13") (pintype "passive"))
    )
    (net (code "225") (name "unconnected-(JP42-Pad14)") (class "Default")
      (node (ref "JP42") (pin "14") (pinfunction "14_14") (pintype "passive"))
    )
    (net (code "226") (name "unconnected-(JP42-Pad15)") (class "Default")
      (node (ref "JP42") (pin "15") (pinfunction "15_15") (pintype "passive"))
    )
    (net (code "227") (name "unconnected-(JP42-Pad16)") (class "Default")
      (node (ref "JP42") (pin "16") (pinfunction "16_16") (pintype "passive"))
    )
    (net (code "228") (name "unconnected-(JP43-Pad2)") (class "Default")
      (node (ref "JP43") (pin "2") (pinfunction "2_2") (pintype "passive"))
    )
    (net (code "229") (name "unconnected-(JP43-Pad3)") (class "Default")
      (node (ref "JP43") (pin "3") (pinfunction "3_3") (pintype "passive"))
    )
    (net (code "230") (name "unconnected-(JP43-Pad4)") (class "Default")
      (node (ref "JP43") (pin "4") (pinfunction "4_4") (pintype "passive"))
    )
    (net (code "231") (name "unconnected-(JP43-Pad5)") (class "Default")
      (node (ref "JP43") (pin "5") (pinfunction "5_5") (pintype "passive"))
    )
    (net (code "232") (name "unconnected-(JP43-Pad6)") (class "Default")
      (node (ref "JP43") (pin "6") (pinfunction "6_6") (pintype "passive"))
    )
    (net (code "233") (name "unconnected-(JP43-Pad7)") (class "Default")
      (node (ref "JP43") (pin "7") (pinfunction "7_7") (pintype "passive"))
    )
    (net (code "234") (name "unconnected-(JP43-Pad8)") (class "Default")
      (node (ref "JP43") (pin "8") (pinfunction "8_8") (pintype "passive"))
    )
    (net (code "235") (name "unconnected-(JP43-Pad9)") (class "Default")
      (node (ref "JP43") (pin "9") (pinfunction "9_9") (pintype "passive"))
    )
    (net (code "236") (name "unconnected-(JP43-Pad10)") (class "Default")
      (node (ref "JP43") (pin "10") (pinfunction "10_10") (pintype "passive"))
    )
    (net (code "237") (name "unconnected-(JP43-Pad11)") (class "Default")
      (node (ref "JP43") (pin "11") (pinfunction "11_11") (pintype "passive"))
    )
    (net (code "238") (name "unconnected-(JP43-Pad12)") (class "Default")
      (node (ref "JP43") (pin "12") (pinfunction "12_12") (pintype "passive"))
    )
    (net (code "239") (name "unconnected-(JP43-Pad13)") (class "Default")
      (node (ref "JP43") (pin "13") (pinfunction "13_13") (pintype "passive"))
    )
    (net (code "240") (name "unconnected-(JP43-Pad14)") (class "Default")
      (node (ref "JP43") (pin "14") (pinfunction "14_14") (pintype "passive"))
    )
    (net (code "241") (name "unconnected-(JP43-Pad15)") (class "Default")
      (node (ref "JP43") (pin "15") (pinfunction "15_15") (pintype "passive"))
    )
    (net (code "242") (name "unconnected-(JP43-Pad16)") (class "Default")
      (node (ref "JP43") (pin "16") (pinfunction "16_16") (pintype "passive"))
    )
    (net (code "243") (name "unconnected-(JP44-Pad2)") (class "Default")
      (node (ref "JP44") (pin "2") (pinfunction "2_2") (pintype "passive"))
    )
    (net (code "244") (name "unconnected-(JP44-Pad3)") (class "Default")
      (node (ref "JP44") (pin "3") (pinfunction "3_3") (pintype "passive"))
    )
    (net (code "245") (name "unconnected-(JP44-Pad4)") (class "Default")
      (node (ref "JP44") (pin "4") (pinfunction "4_4") (pintype "passive"))
    )
    (net (code "246") (name "unconnected-(JP44-Pad5)") (class "Default")
      (node (ref "JP44") (pin "5") (pinfunction "5_5") (pintype "passive"))
    )
    (net (code "247") (name "unconnected-(JP44-Pad6)") (class "Default")
      (node (ref "JP44") (pin "6") (pinfunction "6_6") (pintype "passive"))
    )
    (net (code "248") (name "unconnected-(JP44-Pad7)") (class "Default")
      (node (ref "JP44") (pin "7") (pinfunction "7_7") (pintype "passive"))
    )
    (net (code "249") (name "unconnected-(JP44-Pad8)") (class "Default")
      (node (ref "JP44") (pin "8") (pinfunction "8_8") (pintype "passive"))
    )
    (net (code "250") (name "unconnected-(JP44-Pad9)") (class "Default")
      (node (ref "JP44") (pin "9") (pinfunction "9_9") (pintype "passive"))
    )
    (net (code "251") (name "unconnected-(JP44-Pad10)") (class "Default")
      (node (ref "JP44") (pin "10") (pinfunction "10_10") (pintype "passive"))
    )
    (net (code "252") (name "unconnected-(JP44-Pad11)") (class "Default")
      (node (ref "JP44") (pin "11") (pinfunction "11_11") (pintype "passive"))
    )
    (net (code "253") (name "unconnected-(JP44-Pad12)") (class "Default")
      (node (ref "JP44") (pin "12") (pinfunction "12_12") (pintype "passive"))
    )
    (net (code "254") (name "unconnected-(JP44-Pad13)") (class "Default")
      (node (ref "JP44") (pin "13") (pinfunction "13_13") (pintype "passive"))
    )
    (net (code "255") (name "unconnected-(JP44-Pad14)") (class "Default")
      (node (ref "JP44") (pin "14") (pinfunction "14_14") (pintype "passive"))
    )
    (net (code "256") (name "unconnected-(JP44-Pad15)") (class "Default")
      (node (ref "JP44") (pin "15") (pinfunction "15_15") (pintype "passive"))
    )
    (net (code "257") (name "unconnected-(JP44-Pad16)") (class "Default")
      (node (ref "JP44") (pin "16") (pinfunction "16_16") (pintype "passive"))
    )
    (net (code "258") (name "unconnected-(JP45-Pad2)") (class "Default")
      (node (ref "JP45") (pin "2") (pinfunction "2_2") (pintype "passive"))
    )
    (net (code "259") (name "unconnected-(JP45-Pad3)") (class "Default")
      (node (ref "JP45") (pin "3") (pinfunction "3_3") (pintype "passive"))
    )
    (net (code "260") (name "unconnected-(JP45-Pad4)") (class "Default")
      (node (ref "JP45") (pin "4") (pinfunction "4_4") (pintype "passive"))
    )
    (net (code "261") (name "unconnected-(JP45-Pad5)") (class "Default")
      (node (ref "JP45") (pin "5") (pinfunction "5_5") (pintype "passive"))
    )
    (net (code "262") (name "unconnected-(JP45-Pad6)") (class "Default")
      (node (ref "JP45") (pin "6") (pinfunction "6_6") (pintype "passive"))
    )
    (net (code "263") (name "unconnected-(JP45-Pad7)") (class "Default")
      (node (ref "JP45") (pin "7") (pinfunction "7_7") (pintype "passive"))
    )
    (net (code "264") (name "unconnected-(JP45-Pad8)") (class "Default")
      (node (ref "JP45") (pin "8") (pinfunction "8_8") (pintype "passive"))
    )
    (net (code "265") (name "unconnected-(JP45-Pad9)") (class "Default")
      (node (ref "JP45") (pin "9") (pinfunction "9_9") (pintype "passive"))
    )
    (net (code "266") (name "unconnected-(JP45-Pad10)") (class "Default")
      (node (ref "JP45") (pin "10") (pinfunction "10_10") (pintype "passive"))
    )
    (net (code "267") (name "unconnected-(JP45-Pad11)") (class "Default")
      (node (ref "JP45") (pin "11") (pinfunction "11_11") (pintype "passive"))
    )
    (net (code "268") (name "unconnected-(JP45-Pad12)") (class "Default")
      (node (ref "JP45") (pin "12") (pinfunction "12_12") (pintype "passive"))
    )
    (net (code "269") (name "unconnected-(JP45-Pad13)") (class "Default")
      (node (ref "JP45") (pin "13") (pinfunction "13_13") (pintype "passive"))
    )
    (net (code "270") (name "unconnected-(JP45-Pad14)") (class "Default")
      (node (ref "JP45") (pin "14") (pinfunction "14_14") (pintype "passive"))
    )
    (net (code "271") (name "unconnected-(JP45-Pad15)") (class "Default")
      (node (ref "JP45") (pin "15") (pinfunction "15_15") (pintype "passive"))
    )
    (net (code "272") (name "unconnected-(JP45-Pad16)") (class "Default")
      (node (ref "JP45") (pin "16") (pinfunction "16_16") (pintype "passive"))
    )
    (net (code "273") (name "unconnected-(JP46-Pad2)") (class "Default")
      (node (ref "JP46") (pin "2") (pinfunction "2_2") (pintype "passive"))
    )
    (net (code "274") (name "unconnected-(JP46-Pad3)") (class "Default")
      (node (ref "JP46") (pin "3") (pinfunction "3_3") (pintype "passive"))
    )
    (net (code "275") (name "unconnected-(JP46-Pad4)") (class "Default")
      (node (ref "JP46") (pin "4") (pinfunction "4_4") (pintype "passive"))
    )
    (net (code "276") (name "unconnected-(JP46-Pad5)") (class "Default")
      (node (ref "JP46") (pin "5") (pinfunction "5_5") (pintype "passive"))
    )
    (net (code "277") (name "unconnected-(JP46-Pad6)") (class "Default")
      (node (ref "JP46") (pin "6") (pinfunction "6_6") (pintype "passive"))
    )
    (net (code "278") (name "unconnected-(JP46-Pad7)") (class "Default")
      (node (ref "JP46") (pin "7") (pinfunction "7_7") (pintype "passive"))
    )
    (net (code "279") (name "unconnected-(JP46-Pad8)") (class "Default")
      (node (ref "JP46") (pin "8") (pinfunction "8_8") (pintype "passive"))
    )
    (net (code "280") (name "unconnected-(JP46-Pad9)") (class "Default")
      (node (ref "JP46") (pin "9") (pinfunction "9_9") (pintype "passive"))
    )
    (net (code "281") (name "unconnected-(JP46-Pad10)") (class "Default")
      (node (ref "JP46") (pin "10") (pinfunction "10_10") (pintype "passive"))
    )
    (net (code "282") (name "unconnected-(JP46-Pad11)") (class "Default")
      (node (ref "JP46") (pin "11") (pinfunction "11_11") (pintype "passive"))
    )
    (net (code "283") (name "unconnected-(JP46-Pad12)") (class "Default")
      (node (ref "JP46") (pin "12") (pinfunction "12_12") (pintype "passive"))
    )
    (net (code "284") (name "unconnected-(JP46-Pad13)") (class "Default")
      (node (ref "JP46") (pin "13") (pinfunction "13_13") (pintype "passive"))
    )
    (net (code "285") (name "unconnected-(JP46-Pad14)") (class "Default")
      (node (ref "JP46") (pin "14") (pinfunction "14_14") (pintype "passive"))
    )
    (net (code "286") (name "unconnected-(JP46-Pad15)") (class "Default")
      (node (ref "JP46") (pin "15") (pinfunction "15_15") (pintype "passive"))
    )
    (net (code "287") (name "unconnected-(JP46-Pad16)") (class "Default")
      (node (ref "JP46") (pin "16") (pinfunction "16_16") (pintype "passive"))
    )
    (net (code "288") (name "unconnected-(JP47-Pad2)") (class "Default")
      (node (ref "JP47") (pin "2") (pinfunction "2_2") (pintype "passive"))
    )
    (net (code "289") (name "unconnected-(JP47-Pad3)") (class "Default")
      (node (ref "JP47") (pin "3") (pinfunction "3_3") (pintype "passive"))
    )
    (net (code "290") (name "unconnected-(JP47-Pad4)") (class "Default")
      (node (ref "JP47") (pin "4") (pinfunction "4_4") (pintype "passive"))
    )
    (net (code "291") (name "unconnected-(JP47-Pad5)") (class "Default")
      (node (ref "JP47") (pin "5") (pinfunction "5_5") (pintype "passive"))
    )
    (net (code "292") (name "unconnected-(JP47-Pad6)") (class "Default")
      (node (ref "JP47") (pin "6") (pinfunction "6_6") (pintype "passive"))
    )
    (net (code "293") (name "unconnected-(JP47-Pad7)") (class "Default")
      (node (ref "JP47") (pin "7") (pinfunction "7_7") (pintype "passive"))
    )
    (net (code "294") (name "unconnected-(JP47-Pad8)") (class "Default")
      (node (ref "JP47") (pin "8") (pinfunction "8_8") (pintype "passive"))
    )
    (net (code "295") (name "unconnected-(JP47-Pad9)") (class "Default")
      (node (ref "JP47") (pin "9") (pinfunction "9_9") (pintype "passive"))
    )
    (net (code "296") (name "unconnected-(JP47-Pad10)") (class "Default")
      (node (ref "JP47") (pin "10") (pinfunction "10_10") (pintype "passive"))
    )
    (net (code "297") (name "unconnected-(JP47-Pad11)") (class "Default")
      (node (ref "JP47") (pin "11") (pinfunction "11_11") (pintype "passive"))
    )
    (net (code "298") (name "unconnected-(JP47-Pad12)") (class "Default")
      (node (ref "JP47") (pin "12") (pinfunction "12_12") (pintype "passive"))
    )
    (net (code "299") (name "unconnected-(JP47-Pad13)") (class "Default")
      (node (ref "JP47") (pin "13") (pinfunction "13_13") (pintype "passive"))
    )
    (net (code "300") (name "unconnected-(JP47-Pad14)") (class "Default")
      (node (ref "JP47") (pin "14") (pinfunction "14_14") (pintype "passive"))
    )
    (net (code "301") (name "unconnected-(JP47-Pad15)") (class "Default")
      (node (ref "JP47") (pin "15") (pinfunction "15_15") (pintype "passive"))
    )
    (net (code "302") (name "unconnected-(JP47-Pad16)") (class "Default")
      (node (ref "JP47") (pin "16") (pinfunction "16_16") (pintype "passive"))
    )
    (net (code "303") (name "unconnected-(JP48-Pad2)") (class "Default")
      (node (ref "JP48") (pin "2") (pinfunction "2_2") (pintype "passive"))
    )
    (net (code "304") (name "unconnected-(JP48-Pad3)") (class "Default")
      (node (ref "JP48") (pin "3") (pinfunction "3_3") (pintype "passive"))
    )
    (net (code "305") (name "unconnected-(JP48-Pad4)") (class "Default")
      (node (ref "JP48") (pin "4") (pinfunction "4_4") (pintype "passive"))
    )
    (net (code "306") (name "unconnected-(JP48-Pad5)") (class "Default")
      (node (ref "JP48") (pin "5") (pinfunction "5_5") (pintype "passive"))
    )
    (net (code "307") (name "unconnected-(JP48-Pad6)") (class "Default")
      (node (ref "JP48") (pin "6") (pinfunction "6_6") (pintype "passive"))
    )
    (net (code "308") (name "unconnected-(JP48-Pad7)") (class "Default")
      (node (ref "JP48") (pin "7") (pinfunction "7_7") (pintype "passive"))
    )
    (net (code "309") (name "unconnected-(JP48-Pad8)") (class "Default")
      (node (ref "JP48") (pin "8") (pinfunction "8_8") (pintype "passive"))
    )
    (net (code "310") (name "unconnected-(JP48-Pad9)") (class "Default")
      (node (ref "JP48") (pin "9") (pinfunction "9_9") (pintype "passive"))
    )
    (net (code "311") (name "unconnected-(JP48-Pad10)") (class "Default")
      (node (ref "JP48") (pin "10") (pinfunction "10_10") (pintype "passive"))
    )
    (net (code "312") (name "unconnected-(JP48-Pad11)") (class "Default")
      (node (ref "JP48") (pin "11") (pinfunction "11_11") (pintype "passive"))
    )
    (net (code "313") (name "unconnected-(JP48-Pad12)") (class "Default")
      (node (ref "JP48") (pin "12") (pinfunction "12_12") (pintype "passive"))
    )
    (net (code "314") (name "unconnected-(JP48-Pad13)") (class "Default")
      (node (ref "JP48") (pin "13") (pinfunction "13_13") (pintype "passive"))
    )
    (net (code "315") (name "unconnected-(JP48-Pad14)") (class "Default")
      (node (ref "JP48") (pin "14") (pinfunction "14_14") (pintype "passive"))
    )
    (net (code "316") (name "unconnected-(JP48-Pad15)") (class "Default")
      (node (ref "JP48") (pin "15") (pinfunction "15_15") (pintype "passive"))
    )
    (net (code "317") (name "unconnected-(JP48-Pad16)") (class "Default")
      (node (ref "JP48") (pin "16") (pinfunction "16_16") (pintype "passive"))
    )
    (net (code "318") (name "unconnected-(JP49-Pad2)") (class "Default")
      (node (ref "JP49") (pin "2") (pinfunction "2_2") (pintype "passive"))
    )
    (net (code "319") (name "unconnected-(JP49-Pad3)") (class "Default")
      (node (ref "JP49") (pin "3") (pinfunction "3_3") (pintype "passive"))
    )
    (net (code "320") (name "unconnected-(JP49-Pad4)") (class "Default")
      (node (ref "JP49") (pin "4") (pinfunction "4_4") (pintype "passive"))
    )
    (net (code "321") (name "unconnected-(JP49-Pad5)") (class "Default")
      (node (ref "JP49") (pin "5") (pinfunction "5_5") (pintype "passive"))
    )
    (net (code "322") (name "unconnected-(JP49-Pad6)") (class "Default")
      (node (ref "JP49") (pin "6") (pinfunction "6_6") (pintype "passive"))
    )
    (net (code "323") (name "unconnected-(JP49-Pad7)") (class "Default")
      (node (ref "JP49") (pin "7") (pinfunction "7_7") (pintype "passive"))
    )
    (net (code "324") (name "unconnected-(JP49-Pad8)") (class "Default")
      (node (ref "JP49") (pin "8") (pinfunction "8_8") (pintype "passive"))
    )
    (net (code "325") (name "unconnected-(JP49-Pad9)") (class "Default")
      (node (ref "JP49") (pin "9") (pinfunction "9_9") (pintype "passive"))
    )
    (net (code "326") (name "unconnected-(JP49-Pad10)") (class "Default")
      (node (ref "JP49") (pin "10") (pinfunction "10_10") (pintype "passive"))
    )
    (net (code "327") (name "unconnected-(JP49-Pad11)") (class "Default")
      (node (ref "JP49") (pin "11") (pinfunction "11_11") (pintype "passive"))
    )
    (net (code "328") (name "unconnected-(JP49-Pad12)") (class "Default")
      (node (ref "JP49") (pin "12") (pinfunction "12_12") (pintype "passive"))
    )
    (net (code "329") (name "unconnected-(JP49-Pad13)") (class "Default")
      (node (ref "JP49") (pin "13") (pinfunction "13_13") (pintype "passive"))
    )
    (net (code "330") (name "unconnected-(JP49-Pad14)") (class "Default")
      (node (ref "JP49") (pin "14") (pinfunction "14_14") (pintype "passive"))
    )
    (net (code "331") (name "unconnected-(JP49-Pad15)") (class "Default")
      (node (ref "JP49") (pin "15") (pinfunction "15_15") (pintype "passive"))
    )
    (net (code "332") (name "unconnected-(JP49-Pad16)") (class "Default")
      (node (ref "JP49") (pin "16") (pinfunction "16_16") (pintype "passive"))
    )
    (net (code "333") (name "unconnected-(JP50-Pad2)") (class "Default")
      (node (ref "JP50") (pin "2") (pinfunction "2_2") (pintype "passive"))
    )
    (net (code "334") (name "unconnected-(JP50-Pad3)") (class "Default")
      (node (ref "JP50") (pin "3") (pinfunction "3_3") (pintype "passive"))
    )
    (net (code "335") (name "unconnected-(JP50-Pad4)") (class "Default")
      (node (ref "JP50") (pin "4") (pinfunction "4_4") (pintype "passive"))
    )
    (net (code "336") (name "unconnected-(JP50-Pad5)") (class "Default")
      (node (ref "JP50") (pin "5") (pinfunction "5_5") (pintype "passive"))
    )
    (net (code "337") (name "unconnected-(JP50-Pad6)") (class "Default")
      (node (ref "JP50") (pin "6") (pinfunction "6_6") (pintype "passive"))
    )
    (net (code "338") (name "unconnected-(JP50-Pad7)") (class "Default")
      (node (ref "JP50") (pin "7") (pinfunction "7_7") (pintype "passive"))
    )
    (net (code "339") (name "unconnected-(JP50-Pad8)") (class "Default")
      (node (ref "JP50") (pin "8") (pinfunction "8_8") (pintype "passive"))
    )
    (net (code "340") (name "unconnected-(JP50-Pad9)") (class "Default")
      (node (ref "JP50") (pin "9") (pinfunction "9_9") (pintype "passive"))
    )
    (net (code "341") (name "unconnected-(JP50-Pad10)") (class "Default")
      (node (ref "JP50") (pin "10") (pinfunction "10_10") (pintype "passive"))
    )
    (net (code "342") (name "unconnected-(JP50-Pad11)") (class "Default")
      (node (ref "JP50") (pin "11") (pinfunction "11_11") (pintype "passive"))
    )
    (net (code "343") (name "unconnected-(JP50-Pad12)") (class "Default")
      (node (ref "JP50") (pin "12") (pinfunction "12_12") (pintype "passive"))
    )
    (net (code "344") (name "unconnected-(JP50-Pad13)") (class "Default")
      (node (ref "JP50") (pin "13") (pinfunction "13_13") (pintype "passive"))
    )
    (net (code "345") (name "unconnected-(JP50-Pad14)") (class "Default")
      (node (ref "JP50") (pin "14") (pinfunction "14_14") (pintype "passive"))
    )
    (net (code "346") (name "unconnected-(JP50-Pad15)") (class "Default")
      (node (ref "JP50") (pin "15") (pinfunction "15_15") (pintype "passive"))
    )
    (net (code "347") (name "unconnected-(JP50-Pad16)") (class "Default")
      (node (ref "JP50") (pin "16") (pinfunction "16_16") (pintype "passive"))
    )
    (net (code "348") (name "unconnected-(JP51-Pad2)") (class "Default")
      (node (ref "JP51") (pin "2") (pinfunction "2_2") (pintype "passive"))
    )
    (net (code "349") (name "unconnected-(JP51-Pad3)") (class "Default")
      (node (ref "JP51") (pin "3") (pinfunction "3_3") (pintype "passive"))
    )
    (net (code "350") (name "unconnected-(JP51-Pad4)") (class "Default")
      (node (ref "JP51") (pin "4") (pinfunction "4_4") (pintype "passive"))
    )
    (net (code "351") (name "unconnected-(JP51-Pad5)") (class "Default")
      (node (ref "JP51") (pin "5") (pinfunction "5_5") (pintype "passive"))
    )
    (net (code "352") (name "unconnected-(JP51-Pad6)") (class "Default")
      (node (ref "JP51") (pin "6") (pinfunction "6_6") (pintype "passive"))
    )
    (net (code "353") (name "unconnected-(JP51-Pad7)") (class "Default")
      (node (ref "JP51") (pin "7") (pinfunction "7_7") (pintype "passive"))
    )
    (net (code "354") (name "unconnected-(JP51-Pad8)") (class "Default")
      (node (ref "JP51") (pin "8") (pinfunction "8_8") (pintype "passive"))
    )
    (net (code "355") (name "unconnected-(JP51-Pad9)") (class "Default")
      (node (ref "JP51") (pin "9") (pinfunction "9_9") (pintype "passive"))
    )
    (net (code "356") (name "unconnected-(JP51-Pad10)") (class "Default")
      (node (ref "JP51") (pin "10") (pinfunction "10_10") (pintype "passive"))
    )
    (net (code "357") (name "unconnected-(JP51-Pad11)") (class "Default")
      (node (ref "JP51") (pin "11") (pinfunction "11_11") (pintype "passive"))
    )
    (net (code "358") (name "unconnected-(JP51-Pad12)") (class "Default")
      (node (ref "JP51") (pin "12") (pinfunction "12_12") (pintype "passive"))
    )
    (net (code "359") (name "unconnected-(JP51-Pad13)") (class "Default")
      (node (ref "JP51") (pin "13") (pinfunction "13_13") (pintype "passive"))
    )
    (net (code "360") (name "unconnected-(JP51-Pad14)") (class "Default")
      (node (ref "JP51") (pin "14") (pinfunction "14_14") (pintype "passive"))
    )
    (net (code "361") (name "unconnected-(JP51-Pad15)") (class "Default")
      (node (ref "JP51") (pin "15") (pinfunction "15_15") (pintype "passive"))
    )
    (net (code "362") (name "unconnected-(JP51-Pad16)") (class "Default")
      (node (ref "JP51") (pin "16") (pinfunction "16_16") (pintype "passive"))
    )
    (net (code "363") (name "unconnected-(JP52-Pad2)") (class "Default")
      (node (ref "JP52") (pin "2") (pinfunction "2_2") (pintype "passive"))
    )
    (net (code "364") (name "unconnected-(JP52-Pad3)") (class "Default")
      (node (ref "JP52") (pin "3") (pinfunction "3_3") (pintype "passive"))
    )
    (net (code "365") (name "unconnected-(JP52-Pad4)") (class "Default")
      (node (ref "JP52") (pin "4") (pinfunction "4_4") (pintype "passive"))
    )
    (net (code "366") (name "unconnected-(JP52-Pad5)") (class "Default")
      (node (ref "JP52") (pin "5") (pinfunction "5_5") (pintype "passive"))
    )
    (net (code "367") (name "unconnected-(JP52-Pad6)") (class "Default")
      (node (ref "JP52") (pin "6") (pinfunction "6_6") (pintype "passive"))
    )
    (net (code "368") (name "unconnected-(JP52-Pad7)") (class "Default")
      (node (ref "JP52") (pin "7") (pinfunction "7_7") (pintype "passive"))
    )
    (net (code "369") (name "unconnected-(JP52-Pad8)") (class "Default")
      (node (ref "JP52") (pin "8") (pinfunction "8_8") (pintype "passive"))
    )
    (net (code "370") (name "unconnected-(JP52-Pad9)") (class "Default")
      (node (ref "JP52") (pin "9") (pinfunction "9_9") (pintype "passive"))
    )
    (net (code "371") (name "unconnected-(JP52-Pad10)") (class "Default")
      (node (ref "JP52") (pin "10") (pinfunction "10_10") (pintype "passive"))
    )
    (net (code "372") (name "unconnected-(JP52-Pad11)") (class "Default")
      (node (ref "JP52") (pin "11") (pinfunction "11_11") (pintype "passive"))
    )
    (net (code "373") (name "unconnected-(JP52-Pad12)") (class "Default")
      (node (ref "JP52") (pin "12") (pinfunction "12_12") (pintype "passive"))
    )
    (net (code "374") (name "unconnected-(JP52-Pad13)") (class "Default")
      (node (ref "JP52") (pin "13") (pinfunction "13_13") (pintype "passive"))
    )
    (net (code "375") (name "unconnected-(JP52-Pad14)") (class "Default")
      (node (ref "JP52") (pin "14") (pinfunction "14_14") (pintype "passive"))
    )
    (net (code "376") (name "unconnected-(JP52-Pad15)") (class "Default")
      (node (ref "JP52") (pin "15") (pinfunction "15_15") (pintype "passive"))
    )
    (net (code "377") (name "unconnected-(JP52-Pad16)") (class "Default")
      (node (ref "JP52") (pin "16") (pinfunction "16_16") (pintype "passive"))
    )
    (net (code "378") (name "unconnected-(JP53-Pad2)") (class "Default")
      (node (ref "JP53") (pin "2") (pinfunction "2_2") (pintype "passive"))
    )
    (net (code "379") (name "unconnected-(JP53-Pad3)") (class "Default")
      (node (ref "JP53") (pin "3") (pinfunction "3_3") (pintype "passive"))
    )
    (net (code "380") (name "unconnected-(JP53-Pad4)") (class "Default")
      (node (ref "JP53") (pin "4") (pinfunction "4_4") (pintype "passive"))
    )
    (net (code "381") (name "unconnected-(JP53-Pad5)") (class "Default")
      (node (ref "JP53") (pin "5") (pinfunction "5_5") (pintype "passive"))
    )
    (net (code "382") (name "unconnected-(JP53-Pad6)") (class "Default")
      (node (ref "JP53") (pin "6") (pinfunction "6_6") (pintype "passive"))
    )
    (net (code "383") (name "unconnected-(JP53-Pad7)") (class "Default")
      (node (ref "JP53") (pin "7") (pinfunction "7_7") (pintype "passive"))
    )
    (net (code "384") (name "unconnected-(JP53-Pad8)") (class "Default")
      (node (ref "JP53") (pin "8") (pinfunction "8_8") (pintype "passive"))
    )
    (net (code "385") (name "unconnected-(JP53-Pad9)") (class "Default")
      (node (ref "JP53") (pin "9") (pinfunction "9_9") (pintype "passive"))
    )
    (net (code "386") (name "unconnected-(JP53-Pad10)") (class "Default")
      (node (ref "JP53") (pin "10") (pinfunction "10_10") (pintype "passive"))
    )
    (net (code "387") (name "unconnected-(JP53-Pad11)") (class "Default")
      (node (ref "JP53") (pin "11") (pinfunction "11_11") (pintype "passive"))
    )
    (net (code "388") (name "unconnected-(JP53-Pad12)") (class "Default")
      (node (ref "JP53") (pin "12") (pinfunction "12_12") (pintype "passive"))
    )
    (net (code "389") (name "unconnected-(JP53-Pad13)") (class "Default")
      (node (ref "JP53") (pin "13") (pinfunction "13_13") (pintype "passive"))
    )
    (net (code "390") (name "unconnected-(JP53-Pad14)") (class "Default")
      (node (ref "JP53") (pin "14") (pinfunction "14_14") (pintype "passive"))
    )
    (net (code "391") (name "unconnected-(JP53-Pad15)") (class "Default")
      (node (ref "JP53") (pin "15") (pinfunction "15_15") (pintype "passive"))
    )
    (net (code "392") (name "unconnected-(JP53-Pad16)") (class "Default")
      (node (ref "JP53") (pin "16") (pinfunction "16_16") (pintype "passive"))
    )
    (net (code "393") (name "unconnected-(JP56-Pad2)") (class "Default")
      (node (ref "JP56") (pin "2") (pinfunction "2_2") (pintype "passive"))
    )
    (net (code "394") (name "unconnected-(JP56-Pad3)") (class "Default")
      (node (ref "JP56") (pin "3") (pinfunction "3_3") (pintype "passive"))
    )
    (net (code "395") (name "unconnected-(JP56-Pad4)") (class "Default")
      (node (ref "JP56") (pin "4") (pinfunction "4_4") (pintype "passive"))
    )
    (net (code "396") (name "unconnected-(JP56-Pad5)") (class "Default")
      (node (ref "JP56") (pin "5") (pinfunction "5_5") (pintype "passive"))
    )
    (net (code "397") (name "unconnected-(JP56-Pad6)") (class "Default")
      (node (ref "JP56") (pin "6") (pinfunction "6_6") (pintype "passive"))
    )
    (net (code "398") (name "unconnected-(JP56-Pad7)") (class "Default")
      (node (ref "JP56") (pin "7") (pinfunction "7_7") (pintype "passive"))
    )
    (net (code "399") (name "unconnected-(JP56-Pad8)") (class "Default")
      (node (ref "JP56") (pin "8") (pinfunction "8_8") (pintype "passive"))
    )
    (net (code "400") (name "unconnected-(JP56-Pad9)") (class "Default")
      (node (ref "JP56") (pin "9") (pinfunction "9_9") (pintype "passive"))
    )
    (net (code "401") (name "unconnected-(JP56-Pad10)") (class "Default")
      (node (ref "JP56") (pin "10") (pinfunction "10_10") (pintype "passive"))
    )
    (net (code "402") (name "unconnected-(JP56-Pad11)") (class "Default")
      (node (ref "JP56") (pin "11") (pinfunction "11_11") (pintype "passive"))
    )
    (net (code "403") (name "unconnected-(JP56-Pad12)") (class "Default")
      (node (ref "JP56") (pin "12") (pinfunction "12_12") (pintype "passive"))
    )
    (net (code "404") (name "unconnected-(JP56-Pad13)") (class "Default")
      (node (ref "JP56") (pin "13") (pinfunction "13_13") (pintype "passive"))
    )
    (net (code "405") (name "unconnected-(JP56-Pad14)") (class "Default")
      (node (ref "JP56") (pin "14") (pinfunction "14_14") (pintype "passive"))
    )
    (net (code "406") (name "unconnected-(JP56-Pad15)") (class "Default")
      (node (ref "JP56") (pin "15") (pinfunction "15_15") (pintype "passive"))
    )
    (net (code "407") (name "unconnected-(JP56-Pad16)") (class "Default")
      (node (ref "JP56") (pin "16") (pinfunction "16_16") (pintype "passive"))
    )
    (net (code "408") (name "unconnected-(JP57-Pad2)") (class "Default")
      (node (ref "JP57") (pin "2") (pinfunction "2_2") (pintype "passive"))
    )
    (net (code "409") (name "unconnected-(JP57-Pad3)") (class "Default")
      (node (ref "JP57") (pin "3") (pinfunction "3_3") (pintype "passive"))
    )
    (net (code "410") (name "unconnected-(JP57-Pad4)") (class "Default")
      (node (ref "JP57") (pin "4") (pinfunction "4_4") (pintype "passive"))
    )
    (net (code "411") (name "unconnected-(JP57-Pad5)") (class "Default")
      (node (ref "JP57") (pin "5") (pinfunction "5_5") (pintype "passive"))
    )
    (net (code "412") (name "unconnected-(JP57-Pad6)") (class "Default")
      (node (ref "JP57") (pin "6") (pinfunction "6_6") (pintype "passive"))
    )
    (net (code "413") (name "unconnected-(JP57-Pad7)") (class "Default")
      (node (ref "JP57") (pin "7") (pinfunction "7_7") (pintype "passive"))
    )
    (net (code "414") (name "unconnected-(JP57-Pad8)") (class "Default")
      (node (ref "JP57") (pin "8") (pinfunction "8_8") (pintype "passive"))
    )
    (net (code "415") (name "unconnected-(JP57-Pad9)") (class "Default")
      (node (ref "JP57") (pin "9") (pinfunction "9_9") (pintype "passive"))
    )
    (net (code "416") (name "unconnected-(JP57-Pad10)") (class "Default")
      (node (ref "JP57") (pin "10") (pinfunction "10_10") (pintype "passive"))
    )
    (net (code "417") (name "unconnected-(JP57-Pad11)") (class "Default")
      (node (ref "JP57") (pin "11") (pinfunction "11_11") (pintype "passive"))
    )
    (net (code "418") (name "unconnected-(JP57-Pad12)") (class "Default")
      (node (ref "JP57") (pin "12") (pinfunction "12_12") (pintype "passive"))
    )
    (net (code "419") (name "unconnected-(JP57-Pad13)") (class "Default")
      (node (ref "JP57") (pin "13") (pinfunction "13_13") (pintype "passive"))
    )
    (net (code "420") (name "unconnected-(JP57-Pad14)") (class "Default")
      (node (ref "JP57") (pin "14") (pinfunction "14_14") (pintype "passive"))
    )
    (net (code "421") (name "unconnected-(JP57-Pad15)") (class "Default")
      (node (ref "JP57") (pin "15") (pinfunction "15_15") (pintype "passive"))
    )
    (net (code "422") (name "unconnected-(JP57-Pad16)") (class "Default")
      (node (ref "JP57") (pin "16") (pinfunction "16_16") (pintype "passive"))
    )
    (net (code "423") (name "unconnected-(JP58-Pad1)") (class "Default")
      (node (ref "JP58") (pin "1") (pinfunction "1_1") (pintype "passive"))
    )
    (net (code "424") (name "unconnected-(JP58-Pad2)") (class "Default")
      (node (ref "JP58") (pin "2") (pinfunction "2_2") (pintype "passive"))
    )
    (net (code "425") (name "unconnected-(JP58-Pad3)") (class "Default")
      (node (ref "JP58") (pin "3") (pinfunction "3_3") (pintype "passive"))
    )
    (net (code "426") (name "unconnected-(JP58-Pad4)") (class "Default")
      (node (ref "JP58") (pin "4") (pinfunction "4_4") (pintype "passive"))
    )
    (net (code "427") (name "unconnected-(JP58-Pad5)") (class "Default")
      (node (ref "JP58") (pin "5") (pinfunction "5_5") (pintype "passive"))
    )
    (net (code "428") (name "unconnected-(JP58-Pad6)") (class "Default")
      (node (ref "JP58") (pin "6") (pinfunction "6_6") (pintype "passive"))
    )
    (net (code "429") (name "unconnected-(JP58-Pad7)") (class "Default")
      (node (ref "JP58") (pin "7") (pinfunction "7_7") (pintype "passive"))
    )
    (net (code "430") (name "unconnected-(JP58-Pad8)") (class "Default")
      (node (ref "JP58") (pin "8") (pinfunction "8_8") (pintype "passive"))
    )
    (net (code "431") (name "unconnected-(JP58-Pad9)") (class "Default")
      (node (ref "JP58") (pin "9") (pinfunction "9_9") (pintype "passive"))
    )
    (net (code "432") (name "unconnected-(JP58-Pad10)") (class "Default")
      (node (ref "JP58") (pin "10") (pinfunction "10_10") (pintype "passive"))
    )
    (net (code "433") (name "unconnected-(JP58-Pad11)") (class "Default")
      (node (ref "JP58") (pin "11") (pinfunction "11_11") (pintype "passive"))
    )
    (net (code "434") (name "unconnected-(JP58-Pad12)") (class "Default")
      (node (ref "JP58") (pin "12") (pinfunction "12_12") (pintype "passive"))
    )
    (net (code "435") (name "unconnected-(JP58-Pad13)") (class "Default")
      (node (ref "JP58") (pin "13") (pinfunction "13_13") (pintype "passive"))
    )
    (net (code "436") (name "unconnected-(JP58-Pad14)") (class "Default")
      (node (ref "JP58") (pin "14") (pinfunction "14_14") (pintype "passive"))
    )
    (net (code "437") (name "unconnected-(JP58-Pad15)") (class "Default")
      (node (ref "JP58") (pin "15") (pinfunction "15_15") (pintype "passive"))
    )
    (net (code "438") (name "unconnected-(JP58-Pad16)") (class "Default")
      (node (ref "JP58") (pin "16") (pinfunction "16_16") (pintype "passive"))
    )
    (net (code "439") (name "unconnected-(JP59-Pad2)") (class "Default")
      (node (ref "JP59") (pin "2") (pinfunction "2_2") (pintype "passive"))
    )
    (net (code "440") (name "unconnected-(JP59-Pad3)") (class "Default")
      (node (ref "JP59") (pin "3") (pinfunction "3_3") (pintype "passive"))
    )
    (net (code "441") (name "unconnected-(JP59-Pad4)") (class "Default")
      (node (ref "JP59") (pin "4") (pinfunction "4_4") (pintype "passive"))
    )
    (net (code "442") (name "unconnected-(JP59-Pad5)") (class "Default")
      (node (ref "JP59") (pin "5") (pinfunction "5_5") (pintype "passive"))
    )
    (net (code "443") (name "unconnected-(JP59-Pad6)") (class "Default")
      (node (ref "JP59") (pin "6") (pinfunction "6_6") (pintype "passive"))
    )
    (net (code "444") (name "unconnected-(JP59-Pad7)") (class "Default")
      (node (ref "JP59") (pin "7") (pinfunction "7_7") (pintype "passive"))
    )
    (net (code "445") (name "unconnected-(JP59-Pad8)") (class "Default")
      (node (ref "JP59") (pin "8") (pinfunction "8_8") (pintype "passive"))
    )
    (net (code "446") (name "unconnected-(JP59-Pad9)") (class "Default")
      (node (ref "JP59") (pin "9") (pinfunction "9_9") (pintype "passive"))
    )
    (net (code "447") (name "unconnected-(JP59-Pad10)") (class "Default")
      (node (ref "JP59") (pin "10") (pinfunction "10_10") (pintype "passive"))
    )
    (net (code "448") (name "unconnected-(JP59-Pad11)") (class "Default")
      (node (ref "JP59") (pin "11") (pinfunction "11_11") (pintype "passive"))
    )
    (net (code "449") (name "unconnected-(JP59-Pad12)") (class "Default")
      (node (ref "JP59") (pin "12") (pinfunction "12_12") (pintype "passive"))
    )
    (net (code "450") (name "unconnected-(JP59-Pad13)") (class "Default")
      (node (ref "JP59") (pin "13") (pinfunction "13_13") (pintype "passive"))
    )
    (net (code "451") (name "unconnected-(JP59-Pad14)") (class "Default")
      (node (ref "JP59") (pin "14") (pinfunction "14_14") (pintype "passive"))
    )
    (net (code "452") (name "unconnected-(JP59-Pad15)") (class "Default")
      (node (ref "JP59") (pin "15") (pinfunction "15_15") (pintype "passive"))
    )
    (net (code "453") (name "unconnected-(JP59-Pad16)") (class "Default")
      (node (ref "JP59") (pin "16") (pinfunction "16_16") (pintype "passive"))
    )
    (net (code "454") (name "unconnected-(JP60-Pad2)") (class "Default")
      (node (ref "JP60") (pin "2") (pinfunction "2_2") (pintype "passive"))
    )
    (net (code "455") (name "unconnected-(JP60-Pad3)") (class "Default")
      (node (ref "JP60") (pin "3") (pinfunction "3_3") (pintype "passive"))
    )
    (net (code "456") (name "unconnected-(JP60-Pad4)") (class "Default")
      (node (ref "JP60") (pin "4") (pinfunction "4_4") (pintype "passive"))
    )
    (net (code "457") (name "unconnected-(JP60-Pad5)") (class "Default")
      (node (ref "JP60") (pin "5") (pinfunction "5_5") (pintype "passive"))
    )
    (net (code "458") (name "unconnected-(JP60-Pad6)") (class "Default")
      (node (ref "JP60") (pin "6") (pinfunction "6_6") (pintype "passive"))
    )
    (net (code "459") (name "unconnected-(JP60-Pad7)") (class "Default")
      (node (ref "JP60") (pin "7") (pinfunction "7_7") (pintype "passive"))
    )
    (net (code "460") (name "unconnected-(JP60-Pad8)") (class "Default")
      (node (ref "JP60") (pin "8") (pinfunction "8_8") (pintype "passive"))
    )
    (net (code "461") (name "unconnected-(JP60-Pad9)") (class "Default")
      (node (ref "JP60") (pin "9") (pinfunction "9_9") (pintype "passive"))
    )
    (net (code "462") (name "unconnected-(JP60-Pad10)") (class "Default")
      (node (ref "JP60") (pin "10") (pinfunction "10_10") (pintype "passive"))
    )
    (net (code "463") (name "unconnected-(JP60-Pad11)") (class "Default")
      (node (ref "JP60") (pin "11") (pinfunction "11_11") (pintype "passive"))
    )
    (net (code "464") (name "unconnected-(JP60-Pad12)") (class "Default")
      (node (ref "JP60") (pin "12") (pinfunction "12_12") (pintype "passive"))
    )
    (net (code "465") (name "unconnected-(JP60-Pad13)") (class "Default")
      (node (ref "JP60") (pin "13") (pinfunction "13_13") (pintype "passive"))
    )
    (net (code "466") (name "unconnected-(JP60-Pad14)") (class "Default")
      (node (ref "JP60") (pin "14") (pinfunction "14_14") (pintype "passive"))
    )
    (net (code "467") (name "unconnected-(JP60-Pad15)") (class "Default")
      (node (ref "JP60") (pin "15") (pinfunction "15_15") (pintype "passive"))
    )
    (net (code "468") (name "unconnected-(JP60-Pad16)") (class "Default")
      (node (ref "JP60") (pin "16") (pinfunction "16_16") (pintype "passive"))
    )
    (net (code "469") (name "unconnected-(JP61-Pad2)") (class "Default")
      (node (ref "JP61") (pin "2") (pinfunction "2_2") (pintype "passive"))
    )
    (net (code "470") (name "unconnected-(JP61-Pad3)") (class "Default")
      (node (ref "JP61") (pin "3") (pinfunction "3_3") (pintype "passive"))
    )
    (net (code "471") (name "unconnected-(JP61-Pad4)") (class "Default")
      (node (ref "JP61") (pin "4") (pinfunction "4_4") (pintype "passive"))
    )
    (net (code "472") (name "unconnected-(JP61-Pad5)") (class "Default")
      (node (ref "JP61") (pin "5") (pinfunction "5_5") (pintype "passive"))
    )
    (net (code "473") (name "unconnected-(JP61-Pad6)") (class "Default")
      (node (ref "JP61") (pin "6") (pinfunction "6_6") (pintype "passive"))
    )
    (net (code "474") (name "unconnected-(JP61-Pad7)") (class "Default")
      (node (ref "JP61") (pin "7") (pinfunction "7_7") (pintype "passive"))
    )
    (net (code "475") (name "unconnected-(JP61-Pad8)") (class "Default")
      (node (ref "JP61") (pin "8") (pinfunction "8_8") (pintype "passive"))
    )
    (net (code "476") (name "unconnected-(JP61-Pad9)") (class "Default")
      (node (ref "JP61") (pin "9") (pinfunction "9_9") (pintype "passive"))
    )
    (net (code "477") (name "unconnected-(JP61-Pad10)") (class "Default")
      (node (ref "JP61") (pin "10") (pinfunction "10_10") (pintype "passive"))
    )
    (net (code "478") (name "unconnected-(JP61-Pad11)") (class "Default")
      (node (ref "JP61") (pin "11") (pinfunction "11_11") (pintype "passive"))
    )
    (net (code "479") (name "unconnected-(JP61-Pad12)") (class "Default")
      (node (ref "JP61") (pin "12") (pinfunction "12_12") (pintype "passive"))
    )
    (net (code "480") (name "unconnected-(JP61-Pad13)") (class "Default")
      (node (ref "JP61") (pin "13") (pinfunction "13_13") (pintype "passive"))
    )
    (net (code "481") (name "unconnected-(JP61-Pad14)") (class "Default")
      (node (ref "JP61") (pin "14") (pinfunction "14_14") (pintype "passive"))
    )
    (net (code "482") (name "unconnected-(JP61-Pad15)") (class "Default")
      (node (ref "JP61") (pin "15") (pinfunction "15_15") (pintype "passive"))
    )
    (net (code "483") (name "unconnected-(JP61-Pad16)") (class "Default")
      (node (ref "JP61") (pin "16") (pinfunction "16_16") (pintype "passive"))
    )
    (net (code "484") (name "unconnected-(JP62-Pad2)") (class "Default")
      (node (ref "JP62") (pin "2") (pinfunction "2_2") (pintype "passive"))
    )
    (net (code "485") (name "unconnected-(JP62-Pad3)") (class "Default")
      (node (ref "JP62") (pin "3") (pinfunction "3_3") (pintype "passive"))
    )
    (net (code "486") (name "unconnected-(JP62-Pad4)") (class "Default")
      (node (ref "JP62") (pin "4") (pinfunction "4_4") (pintype "passive"))
    )
    (net (code "487") (name "unconnected-(JP62-Pad5)") (class "Default")
      (node (ref "JP62") (pin "5") (pinfunction "5_5") (pintype "passive"))
    )
    (net (code "488") (name "unconnected-(JP62-Pad6)") (class "Default")
      (node (ref "JP62") (pin "6") (pinfunction "6_6") (pintype "passive"))
    )
    (net (code "489") (name "unconnected-(JP62-Pad7)") (class "Default")
      (node (ref "JP62") (pin "7") (pinfunction "7_7") (pintype "passive"))
    )
    (net (code "490") (name "unconnected-(JP62-Pad8)") (class "Default")
      (node (ref "JP62") (pin "8") (pinfunction "8_8") (pintype "passive"))
    )
    (net (code "491") (name "unconnected-(JP62-Pad9)") (class "Default")
      (node (ref "JP62") (pin "9") (pinfunction "9_9") (pintype "passive"))
    )
    (net (code "492") (name "unconnected-(JP62-Pad10)") (class "Default")
      (node (ref "JP62") (pin "10") (pinfunction "10_10") (pintype "passive"))
    )
    (net (code "493") (name "unconnected-(JP62-Pad11)") (class "Default")
      (node (ref "JP62") (pin "11") (pinfunction "11_11") (pintype "passive"))
    )
    (net (code "494") (name "unconnected-(JP62-Pad12)") (class "Default")
      (node (ref "JP62") (pin "12") (pinfunction "12_12") (pintype "passive"))
    )
    (net (code "495") (name "unconnected-(JP62-Pad13)") (class "Default")
      (node (ref "JP62") (pin "13") (pinfunction "13_13") (pintype "passive"))
    )
    (net (code "496") (name "unconnected-(JP62-Pad14)") (class "Default")
      (node (ref "JP62") (pin "14") (pinfunction "14_14") (pintype "passive"))
    )
    (net (code "497") (name "unconnected-(JP62-Pad15)") (class "Default")
      (node (ref "JP62") (pin "15") (pinfunction "15_15") (pintype "passive"))
    )
    (net (code "498") (name "unconnected-(JP62-Pad16)") (class "Default")
      (node (ref "JP62") (pin "16") (pinfunction "16_16") (pintype "passive"))
    )
    (net (code "499") (name "unconnected-(JP63-Pad2)") (class "Default")
      (node (ref "JP63") (pin "2") (pinfunction "2_2") (pintype "passive"))
    )
    (net (code "500") (name "unconnected-(JP63-Pad3)") (class "Default")
      (node (ref "JP63") (pin "3") (pinfunction "3_3") (pintype "passive"))
    )
    (net (code "501") (name "unconnected-(JP63-Pad4)") (class "Default")
      (node (ref "JP63") (pin "4") (pinfunction "4_4") (pintype "passive"))
    )
    (net (code "502") (name "unconnected-(JP63-Pad5)") (class "Default")
      (node (ref "JP63") (pin "5") (pinfunction "5_5") (pintype "passive"))
    )
    (net (code "503") (name "unconnected-(JP63-Pad6)") (class "Default")
      (node (ref "JP63") (pin "6") (pinfunction "6_6") (pintype "passive"))
    )
    (net (code "504") (name "unconnected-(JP63-Pad7)") (class "Default")
      (node (ref "JP63") (pin "7") (pinfunction "7_7") (pintype "passive"))
    )
    (net (code "505") (name "unconnected-(JP63-Pad8)") (class "Default")
      (node (ref "JP63") (pin "8") (pinfunction "8_8") (pintype "passive"))
    )
    (net (code "506") (name "unconnected-(JP63-Pad9)") (class "Default")
      (node (ref "JP63") (pin "9") (pinfunction "9_9") (pintype "passive"))
    )
    (net (code "507") (name "unconnected-(JP63-Pad10)") (class "Default")
      (node (ref "JP63") (pin "10") (pinfunction "10_10") (pintype "passive"))
    )
    (net (code "508") (name "unconnected-(JP63-Pad11)") (class "Default")
      (node (ref "JP63") (pin "11") (pinfunction "11_11") (pintype "passive"))
    )
    (net (code "509") (name "unconnected-(JP63-Pad12)") (class "Default")
      (node (ref "JP63") (pin "12") (pinfunction "12_12") (pintype "passive"))
    )
    (net (code "510") (name "unconnected-(JP63-Pad13)") (class "Default")
      (node (ref "JP63") (pin "13") (pinfunction "13_13") (pintype "passive"))
    )
    (net (code "511") (name "unconnected-(JP63-Pad14)") (class "Default")
      (node (ref "JP63") (pin "14") (pinfunction "14_14") (pintype "passive"))
    )
    (net (code "512") (name "unconnected-(JP63-Pad15)") (class "Default")
      (node (ref "JP63") (pin "15") (pinfunction "15_15") (pintype "passive"))
    )
    (net (code "513") (name "unconnected-(JP63-Pad16)") (class "Default")
      (node (ref "JP63") (pin "16") (pinfunction "16_16") (pintype "passive"))
    )
    (net (code "514") (name "unconnected-(JP64-Pad2)") (class "Default")
      (node (ref "JP64") (pin "2") (pinfunction "2_2") (pintype "passive"))
    )
    (net (code "515") (name "unconnected-(JP64-Pad3)") (class "Default")
      (node (ref "JP64") (pin "3") (pinfunction "3_3") (pintype "passive"))
    )
    (net (code "516") (name "unconnected-(JP64-Pad4)") (class "Default")
      (node (ref "JP64") (pin "4") (pinfunction "4_4") (pintype "passive"))
    )
    (net (code "517") (name "unconnected-(JP64-Pad5)") (class "Default")
      (node (ref "JP64") (pin "5") (pinfunction "5_5") (pintype "passive"))
    )
    (net (code "518") (name "unconnected-(JP64-Pad6)") (class "Default")
      (node (ref "JP64") (pin "6") (pinfunction "6_6") (pintype "passive"))
    )
    (net (code "519") (name "unconnected-(JP64-Pad7)") (class "Default")
      (node (ref "JP64") (pin "7") (pinfunction "7_7") (pintype "passive"))
    )
    (net (code "520") (name "unconnected-(JP64-Pad8)") (class "Default")
      (node (ref "JP64") (pin "8") (pinfunction "8_8") (pintype "passive"))
    )
    (net (code "521") (name "unconnected-(JP64-Pad9)") (class "Default")
      (node (ref "JP64") (pin "9") (pinfunction "9_9") (pintype "passive"))
    )
    (net (code "522") (name "unconnected-(JP64-Pad10)") (class "Default")
      (node (ref "JP64") (pin "10") (pinfunction "10_10") (pintype "passive"))
    )
    (net (code "523") (name "unconnected-(JP64-Pad11)") (class "Default")
      (node (ref "JP64") (pin "11") (pinfunction "11_11") (pintype "passive"))
    )
    (net (code "524") (name "unconnected-(JP64-Pad12)") (class "Default")
      (node (ref "JP64") (pin "12") (pinfunction "12_12") (pintype "passive"))
    )
    (net (code "525") (name "unconnected-(JP64-Pad13)") (class "Default")
      (node (ref "JP64") (pin "13") (pinfunction "13_13") (pintype "passive"))
    )
    (net (code "526") (name "unconnected-(JP64-Pad14)") (class "Default")
      (node (ref "JP64") (pin "14") (pinfunction "14_14") (pintype "passive"))
    )
    (net (code "527") (name "unconnected-(JP64-Pad15)") (class "Default")
      (node (ref "JP64") (pin "15") (pinfunction "15_15") (pintype "passive"))
    )
    (net (code "528") (name "unconnected-(JP64-Pad16)") (class "Default")
      (node (ref "JP64") (pin "16") (pinfunction "16_16") (pintype "passive"))
    )
    (net (code "529") (name "unconnected-(JP65-Pad2)") (class "Default")
      (node (ref "JP65") (pin "2") (pinfunction "2_2") (pintype "passive"))
    )
    (net (code "530") (name "unconnected-(JP65-Pad3)") (class "Default")
      (node (ref "JP65") (pin "3") (pinfunction "3_3") (pintype "passive"))
    )
    (net (code "531") (name "unconnected-(JP65-Pad4)") (class "Default")
      (node (ref "JP65") (pin "4") (pinfunction "4_4") (pintype "passive"))
    )
    (net (code "532") (name "unconnected-(JP65-Pad5)") (class "Default")
      (node (ref "JP65") (pin "5") (pinfunction "5_5") (pintype "passive"))
    )
    (net (code "533") (name "unconnected-(JP65-Pad6)") (class "Default")
      (node (ref "JP65") (pin "6") (pinfunction "6_6") (pintype "passive"))
    )
    (net (code "534") (name "unconnected-(JP65-Pad7)") (class "Default")
      (node (ref "JP65") (pin "7") (pinfunction "7_7") (pintype "passive"))
    )
    (net (code "535") (name "unconnected-(JP65-Pad8)") (class "Default")
      (node (ref "JP65") (pin "8") (pinfunction "8_8") (pintype "passive"))
    )
    (net (code "536") (name "unconnected-(JP65-Pad9)") (class "Default")
      (node (ref "JP65") (pin "9") (pinfunction "9_9") (pintype "passive"))
    )
    (net (code "537") (name "unconnected-(JP65-Pad10)") (class "Default")
      (node (ref "JP65") (pin "10") (pinfunction "10_10") (pintype "passive"))
    )
    (net (code "538") (name "unconnected-(JP65-Pad11)") (class "Default")
      (node (ref "JP65") (pin "11") (pinfunction "11_11") (pintype "passive"))
    )
    (net (code "539") (name "unconnected-(JP65-Pad12)") (class "Default")
      (node (ref "JP65") (pin "12") (pinfunction "12_12") (pintype "passive"))
    )
    (net (code "540") (name "unconnected-(JP65-Pad13)") (class "Default")
      (node (ref "JP65") (pin "13") (pinfunction "13_13") (pintype "passive"))
    )
    (net (code "541") (name "unconnected-(JP65-Pad14)") (class "Default")
      (node (ref "JP65") (pin "14") (pinfunction "14_14") (pintype "passive"))
    )
    (net (code "542") (name "unconnected-(JP65-Pad15)") (class "Default")
      (node (ref "JP65") (pin "15") (pinfunction "15_15") (pintype "passive"))
    )
    (net (code "543") (name "unconnected-(JP65-Pad16)") (class "Default")
      (node (ref "JP65") (pin "16") (pinfunction "16_16") (pintype "passive"))
    )
    (net (code "544") (name "unconnected-(JP66-Pad2)") (class "Default")
      (node (ref "JP66") (pin "2") (pinfunction "2_2") (pintype "passive"))
    )
    (net (code "545") (name "unconnected-(JP66-Pad3)") (class "Default")
      (node (ref "JP66") (pin "3") (pinfunction "3_3") (pintype "passive"))
    )
    (net (code "546") (name "unconnected-(JP66-Pad4)") (class "Default")
      (node (ref "JP66") (pin "4") (pinfunction "4_4") (pintype "passive"))
    )
    (net (code "547") (name "unconnected-(JP66-Pad5)") (class "Default")
      (node (ref "JP66") (pin "5") (pinfunction "5_5") (pintype "passive"))
    )
    (net (code "548") (name "unconnected-(JP66-Pad6)") (class "Default")
      (node (ref "JP66") (pin "6") (pinfunction "6_6") (pintype "passive"))
    )
    (net (code "549") (name "unconnected-(JP66-Pad7)") (class "Default")
      (node (ref "JP66") (pin "7") (pinfunction "7_7") (pintype "passive"))
    )
    (net (code "550") (name "unconnected-(JP66-Pad8)") (class "Default")
      (node (ref "JP66") (pin "8") (pinfunction "8_8") (pintype "passive"))
    )
    (net (code "551") (name "unconnected-(JP66-Pad9)") (class "Default")
      (node (ref "JP66") (pin "9") (pinfunction "9_9") (pintype "passive"))
    )
    (net (code "552") (name "unconnected-(JP66-Pad10)") (class "Default")
      (node (ref "JP66") (pin "10") (pinfunction "10_10") (pintype "passive"))
    )
    (net (code "553") (name "unconnected-(JP66-Pad11)") (class "Default")
      (node (ref "JP66") (pin "11") (pinfunction "11_11") (pintype "passive"))
    )
    (net (code "554") (name "unconnected-(JP66-Pad12)") (class "Default")
      (node (ref "JP66") (pin "12") (pinfunction "12_12") (pintype "passive"))
    )
    (net (code "555") (name "unconnected-(JP66-Pad13)") (class "Default")
      (node (ref "JP66") (pin "13") (pinfunction "13_13") (pintype "passive"))
    )
    (net (code "556") (name "unconnected-(JP66-Pad14)") (class "Default")
      (node (ref "JP66") (pin "14") (pinfunction "14_14") (pintype "passive"))
    )
    (net (code "557") (name "unconnected-(JP66-Pad15)") (class "Default")
      (node (ref "JP66") (pin "15") (pinfunction "15_15") (pintype "passive"))
    )
    (net (code "558") (name "unconnected-(JP66-Pad16)") (class "Default")
      (node (ref "JP66") (pin "16") (pinfunction "16_16") (pintype "passive"))
    )
    (net (code "559") (name "unconnected-(JP67-Pad2)") (class "Default")
      (node (ref "JP67") (pin "2") (pinfunction "2_2") (pintype "passive"))
    )
    (net (code "560") (name "unconnected-(JP67-Pad3)") (class "Default")
      (node (ref "JP67") (pin "3") (pinfunction "3_3") (pintype "passive"))
    )
    (net (code "561") (name "unconnected-(JP67-Pad4)") (class "Default")
      (node (ref "JP67") (pin "4") (pinfunction "4_4") (pintype "passive"))
    )
    (net (code "562") (name "unconnected-(JP67-Pad5)") (class "Default")
      (node (ref "JP67") (pin "5") (pinfunction "5_5") (pintype "passive"))
    )
    (net (code "563") (name "unconnected-(JP67-Pad6)") (class "Default")
      (node (ref "JP67") (pin "6") (pinfunction "6_6") (pintype "passive"))
    )
    (net (code "564") (name "unconnected-(JP67-Pad7)") (class "Default")
      (node (ref "JP67") (pin "7") (pinfunction "7_7") (pintype "passive"))
    )
    (net (code "565") (name "unconnected-(JP67-Pad8)") (class "Default")
      (node (ref "JP67") (pin "8") (pinfunction "8_8") (pintype "passive"))
    )
    (net (code "566") (name "unconnected-(JP67-Pad9)") (class "Default")
      (node (ref "JP67") (pin "9") (pinfunction "9_9") (pintype "passive"))
    )
    (net (code "567") (name "unconnected-(JP67-Pad10)") (class "Default")
      (node (ref "JP67") (pin "10") (pinfunction "10_10") (pintype "passive"))
    )
    (net (code "568") (name "unconnected-(JP67-Pad11)") (class "Default")
      (node (ref "JP67") (pin "11") (pinfunction "11_11") (pintype "passive"))
    )
    (net (code "569") (name "unconnected-(JP67-Pad12)") (class "Default")
      (node (ref "JP67") (pin "12") (pinfunction "12_12") (pintype "passive"))
    )
    (net (code "570") (name "unconnected-(JP67-Pad13)") (class "Default")
      (node (ref "JP67") (pin "13") (pinfunction "13_13") (pintype "passive"))
    )
    (net (code "571") (name "unconnected-(JP67-Pad14)") (class "Default")
      (node (ref "JP67") (pin "14") (pinfunction "14_14") (pintype "passive"))
    )
    (net (code "572") (name "unconnected-(JP67-Pad15)") (class "Default")
      (node (ref "JP67") (pin "15") (pinfunction "15_15") (pintype "passive"))
    )
    (net (code "573") (name "unconnected-(JP67-Pad16)") (class "Default")
      (node (ref "JP67") (pin "16") (pinfunction "16_16") (pintype "passive"))
    )
    (net (code "574") (name "unconnected-(JP68-Pad2)") (class "Default")
      (node (ref "JP68") (pin "2") (pinfunction "2_2") (pintype "passive"))
    )
    (net (code "575") (name "unconnected-(JP68-Pad3)") (class "Default")
      (node (ref "JP68") (pin "3") (pinfunction "3_3") (pintype "passive"))
    )
    (net (code "576") (name "unconnected-(JP68-Pad4)") (class "Default")
      (node (ref "JP68") (pin "4") (pinfunction "4_4") (pintype "passive"))
    )
    (net (code "577") (name "unconnected-(JP68-Pad5)") (class "Default")
      (node (ref "JP68") (pin "5") (pinfunction "5_5") (pintype "passive"))
    )
    (net (code "578") (name "unconnected-(JP68-Pad6)") (class "Default")
      (node (ref "JP68") (pin "6") (pinfunction "6_6") (pintype "passive"))
    )
    (net (code "579") (name "unconnected-(JP68-Pad7)") (class "Default")
      (node (ref "JP68") (pin "7") (pinfunction "7_7") (pintype "passive"))
    )
    (net (code "580") (name "unconnected-(JP68-Pad8)") (class "Default")
      (node (ref "JP68") (pin "8") (pinfunction "8_8") (pintype "passive"))
    )
    (net (code "581") (name "unconnected-(JP68-Pad9)") (class "Default")
      (node (ref "JP68") (pin "9") (pinfunction "9_9") (pintype "passive"))
    )
    (net (code "582") (name "unconnected-(JP68-Pad10)") (class "Default")
      (node (ref "JP68") (pin "10") (pinfunction "10_10") (pintype "passive"))
    )
    (net (code "583") (name "unconnected-(JP68-Pad11)") (class "Default")
      (node (ref "JP68") (pin "11") (pinfunction "11_11") (pintype "passive"))
    )
    (net (code "584") (name "unconnected-(JP68-Pad12)") (class "Default")
      (node (ref "JP68") (pin "12") (pinfunction "12_12") (pintype "passive"))
    )
    (net (code "585") (name "unconnected-(JP68-Pad13)") (class "Default")
      (node (ref "JP68") (pin "13") (pinfunction "13_13") (pintype "passive"))
    )
    (net (code "586") (name "unconnected-(JP68-Pad14)") (class "Default")
      (node (ref "JP68") (pin "14") (pinfunction "14_14") (pintype "passive"))
    )
    (net (code "587") (name "unconnected-(JP68-Pad15)") (class "Default")
      (node (ref "JP68") (pin "15") (pinfunction "15_15") (pintype "passive"))
    )
    (net (code "588") (name "unconnected-(JP68-Pad16)") (class "Default")
      (node (ref "JP68") (pin "16") (pinfunction "16_16") (pintype "passive"))
    )
    (net (code "589") (name "unconnected-(JP69-Pad2)") (class "Default")
      (node (ref "JP69") (pin "2") (pinfunction "2_2") (pintype "passive"))
    )
    (net (code "590") (name "unconnected-(JP69-Pad3)") (class "Default")
      (node (ref "JP69") (pin "3") (pinfunction "3_3") (pintype "passive"))
    )
    (net (code "591") (name "unconnected-(JP69-Pad4)") (class "Default")
      (node (ref "JP69") (pin "4") (pinfunction "4_4") (pintype "passive"))
    )
    (net (code "592") (name "unconnected-(JP69-Pad5)") (class "Default")
      (node (ref "JP69") (pin "5") (pinfunction "5_5") (pintype "passive"))
    )
    (net (code "593") (name "unconnected-(JP69-Pad6)") (class "Default")
      (node (ref "JP69") (pin "6") (pinfunction "6_6") (pintype "passive"))
    )
    (net (code "594") (name "unconnected-(JP69-Pad7)") (class "Default")
      (node (ref "JP69") (pin "7") (pinfunction "7_7") (pintype "passive"))
    )
    (net (code "595") (name "unconnected-(JP69-Pad8)") (class "Default")
      (node (ref "JP69") (pin "8") (pinfunction "8_8") (pintype "passive"))
    )
    (net (code "596") (name "unconnected-(JP69-Pad9)") (class "Default")
      (node (ref "JP69") (pin "9") (pinfunction "9_9") (pintype "passive"))
    )
    (net (code "597") (name "unconnected-(JP69-Pad10)") (class "Default")
      (node (ref "JP69") (pin "10") (pinfunction "10_10") (pintype "passive"))
    )
    (net (code "598") (name "unconnected-(JP69-Pad11)") (class "Default")
      (node (ref "JP69") (pin "11") (pinfunction "11_11") (pintype "passive"))
    )
    (net (code "599") (name "unconnected-(JP69-Pad12)") (class "Default")
      (node (ref "JP69") (pin "12") (pinfunction "12_12") (pintype "passive"))
    )
    (net (code "600") (name "unconnected-(JP69-Pad13)") (class "Default")
      (node (ref "JP69") (pin "13") (pinfunction "13_13") (pintype "passive"))
    )
    (net (code "601") (name "unconnected-(JP69-Pad14)") (class "Default")
      (node (ref "JP69") (pin "14") (pinfunction "14_14") (pintype "passive"))
    )
    (net (code "602") (name "unconnected-(JP69-Pad15)") (class "Default")
      (node (ref "JP69") (pin "15") (pinfunction "15_15") (pintype "passive"))
    )
    (net (code "603") (name "unconnected-(JP69-Pad16)") (class "Default")
      (node (ref "JP69") (pin "16") (pinfunction "16_16") (pintype "passive"))
    )
    (net (code "604") (name "unconnected-(JP70-Pad2)") (class "Default")
      (node (ref "JP70") (pin "2") (pinfunction "2_2") (pintype "passive"))
    )
    (net (code "605") (name "unconnected-(JP70-Pad3)") (class "Default")
      (node (ref "JP70") (pin "3") (pinfunction "3_3") (pintype "passive"))
    )
    (net (code "606") (name "unconnected-(JP70-Pad4)") (class "Default")
      (node (ref "JP70") (pin "4") (pinfunction "4_4") (pintype "passive"))
    )
    (net (code "607") (name "unconnected-(JP70-Pad5)") (class "Default")
      (node (ref "JP70") (pin "5") (pinfunction "5_5") (pintype "passive"))
    )
    (net (code "608") (name "unconnected-(JP70-Pad6)") (class "Default")
      (node (ref "JP70") (pin "6") (pinfunction "6_6") (pintype "passive"))
    )
    (net (code "609") (name "unconnected-(JP70-Pad7)") (class "Default")
      (node (ref "JP70") (pin "7") (pinfunction "7_7") (pintype "passive"))
    )
    (net (code "610") (name "unconnected-(JP70-Pad8)") (class "Default")
      (node (ref "JP70") (pin "8") (pinfunction "8_8") (pintype "passive"))
    )
    (net (code "611") (name "unconnected-(JP70-Pad9)") (class "Default")
      (node (ref "JP70") (pin "9") (pinfunction "9_9") (pintype "passive"))
    )
    (net (code "612") (name "unconnected-(JP70-Pad10)") (class "Default")
      (node (ref "JP70") (pin "10") (pinfunction "10_10") (pintype "passive"))
    )
    (net (code "613") (name "unconnected-(JP70-Pad11)") (class "Default")
      (node (ref "JP70") (pin "11") (pinfunction "11_11") (pintype "passive"))
    )
    (net (code "614") (name "unconnected-(JP70-Pad12)") (class "Default")
      (node (ref "JP70") (pin "12") (pinfunction "12_12") (pintype "passive"))
    )
    (net (code "615") (name "unconnected-(JP70-Pad13)") (class "Default")
      (node (ref "JP70") (pin "13") (pinfunction "13_13") (pintype "passive"))
    )
    (net (code "616") (name "unconnected-(JP70-Pad14)") (class "Default")
      (node (ref "JP70") (pin "14") (pinfunction "14_14") (pintype "passive"))
    )
    (net (code "617") (name "unconnected-(JP70-Pad15)") (class "Default")
      (node (ref "JP70") (pin "15") (pinfunction "15_15") (pintype "passive"))
    )
    (net (code "618") (name "unconnected-(JP70-Pad16)") (class "Default")
      (node (ref "JP70") (pin "16") (pinfunction "16_16") (pintype "passive"))
    )
  )
)
